# STALO_2.net
KiCad netlist of a schematic drawn in Altium Designer
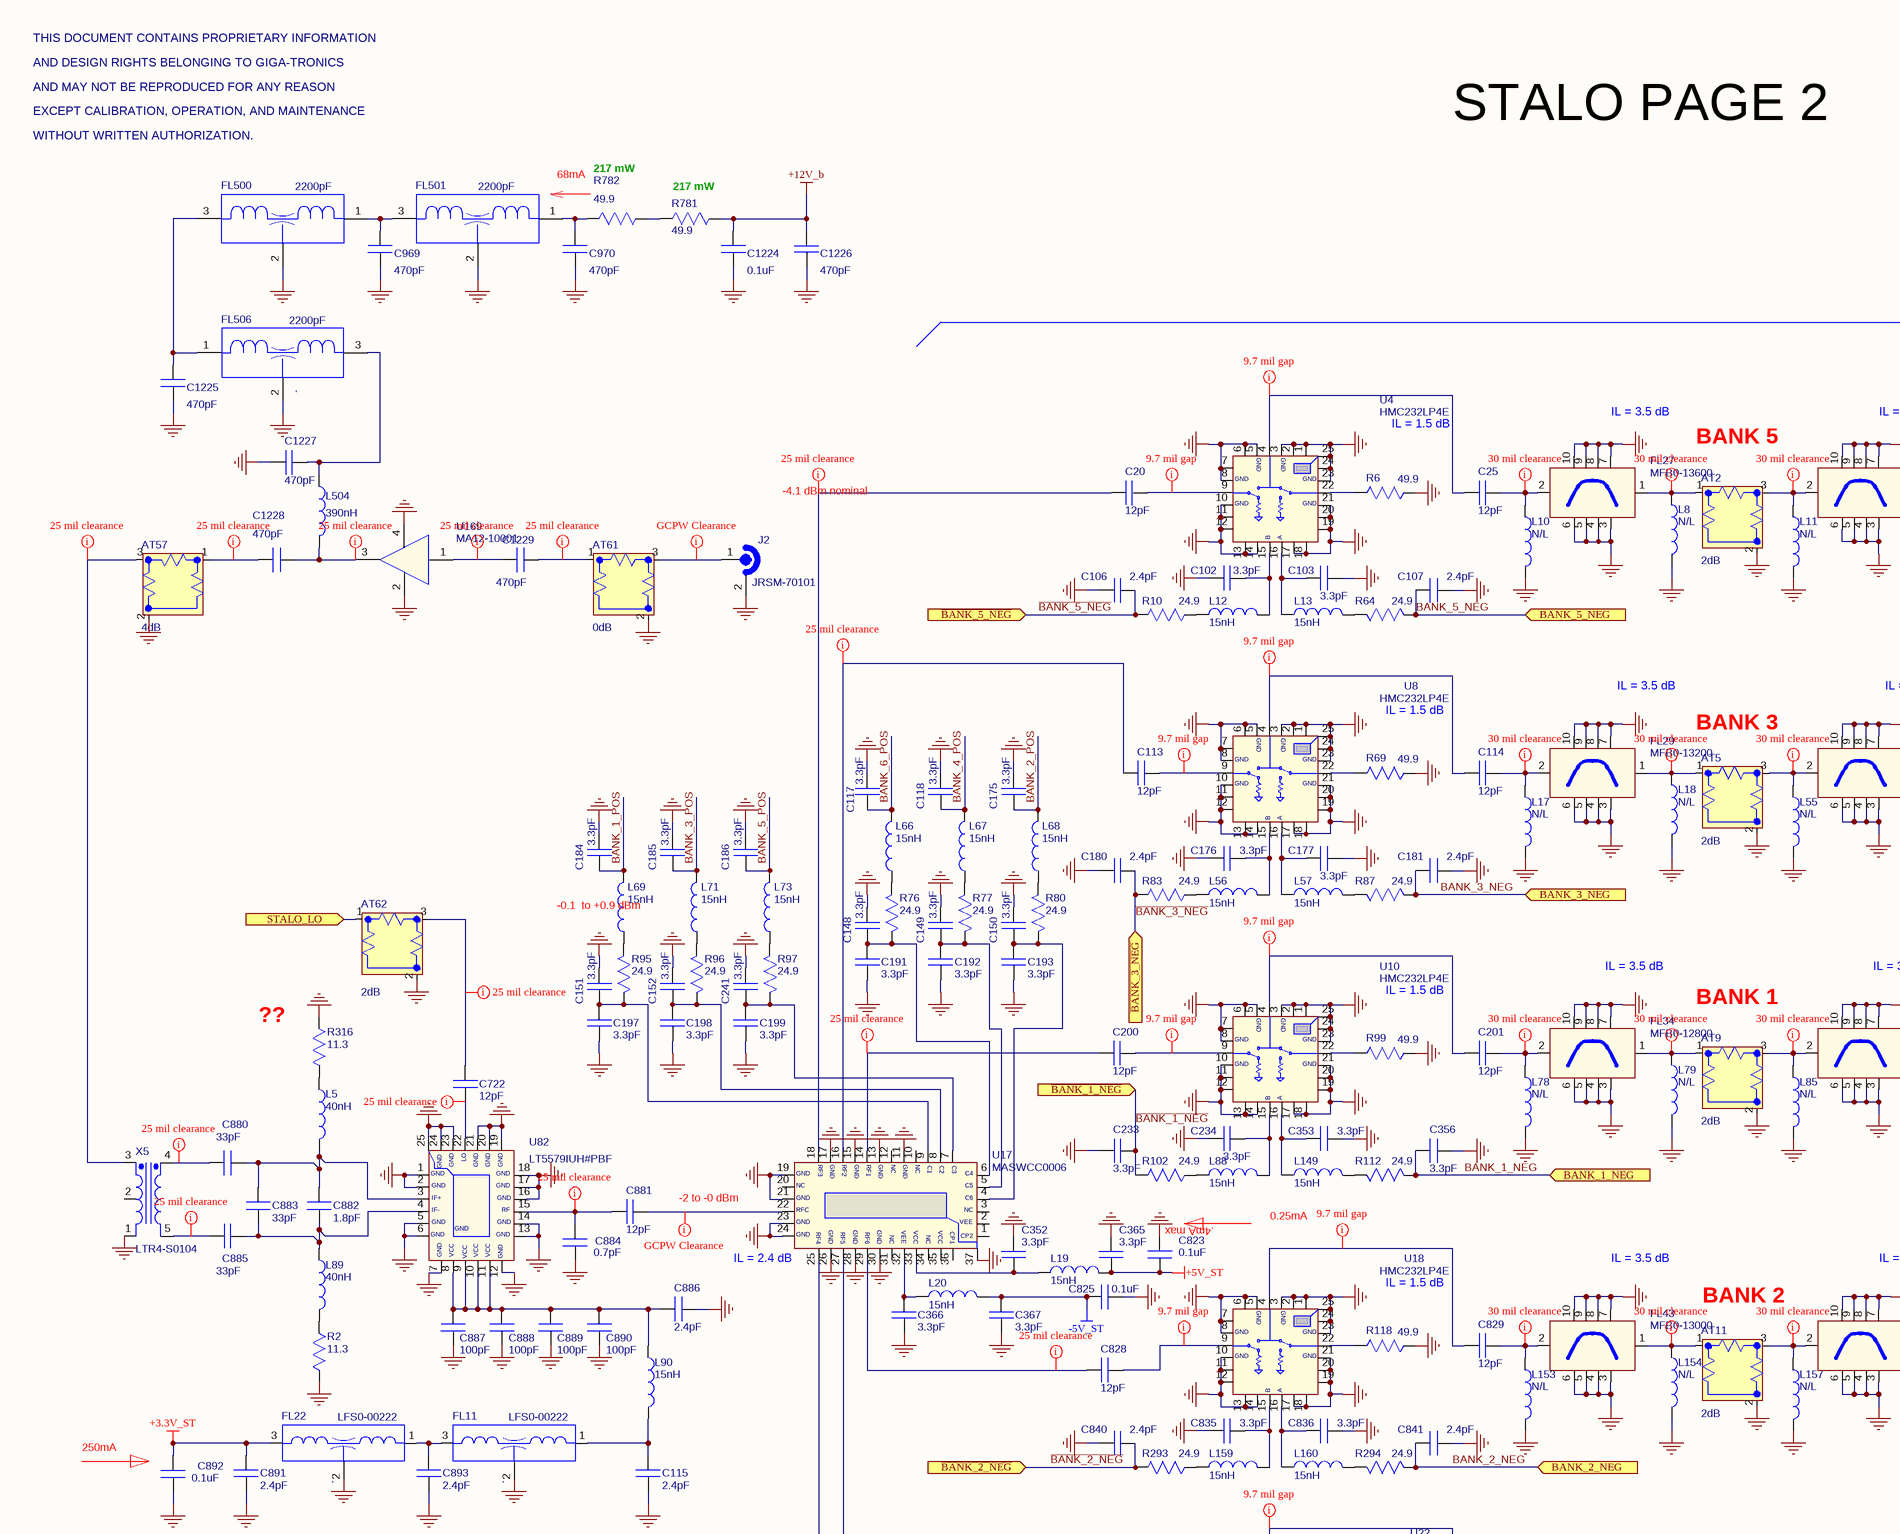
[diagram p0: STALO_2.SchDoc, top left]
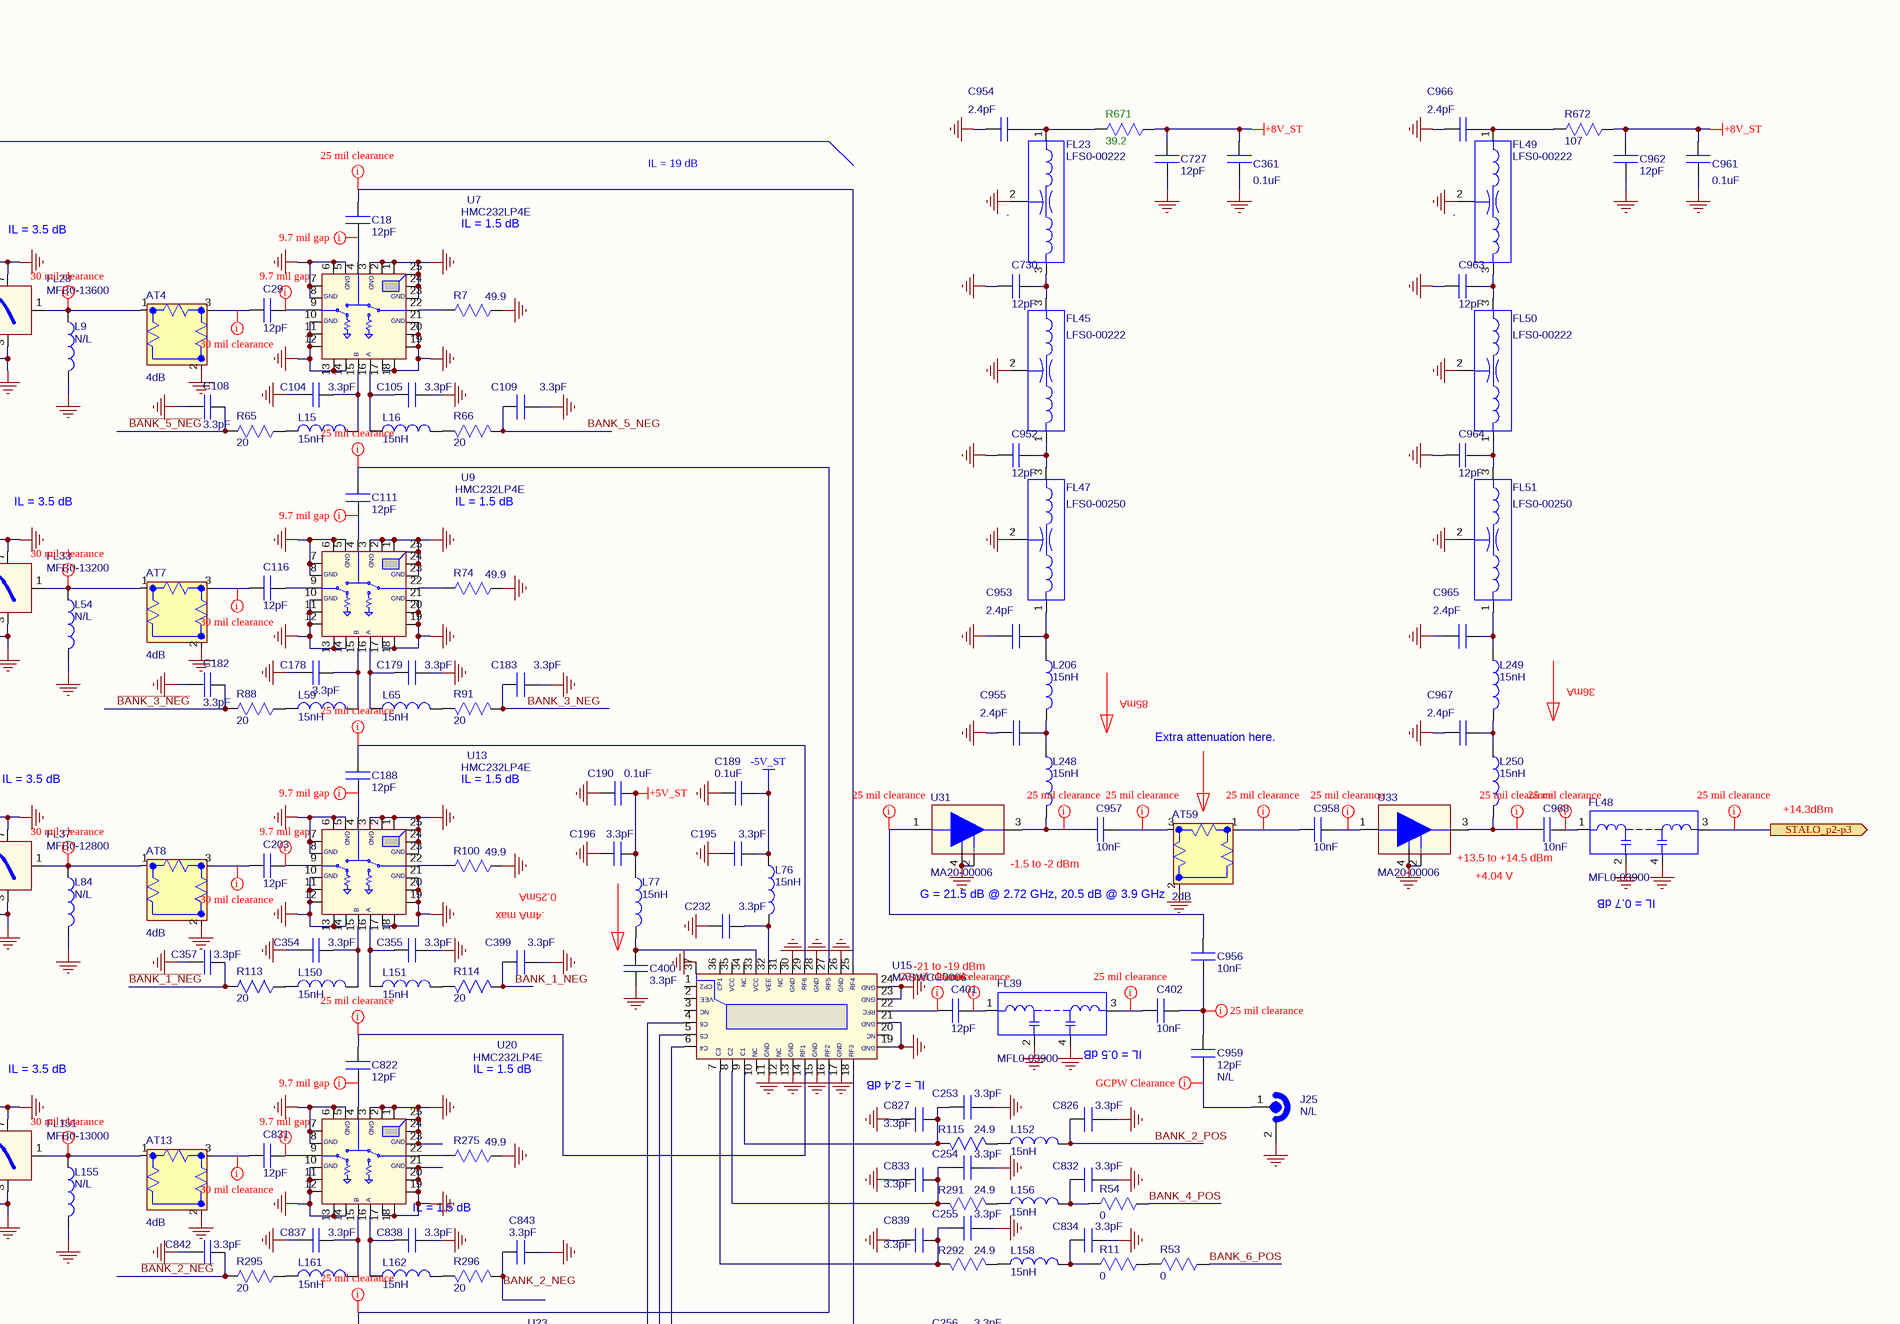
[diagram p1: STALO_2.SchDoc, top right]
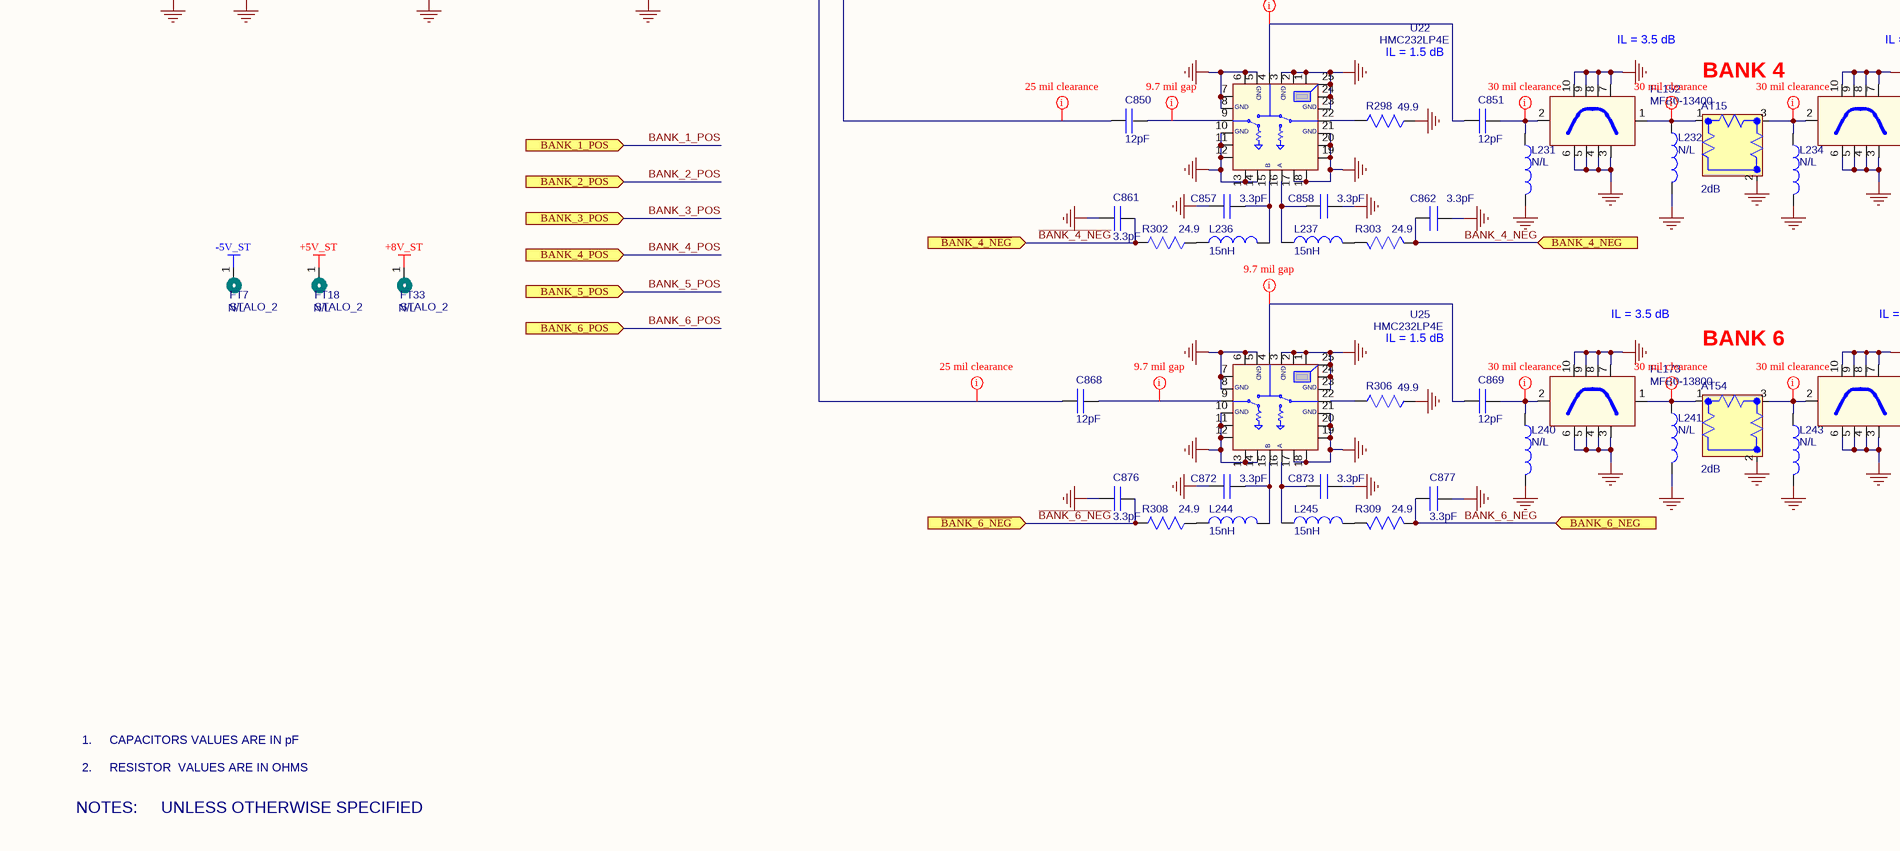
[diagram p2: STALO_2.SchDoc, bottom left]
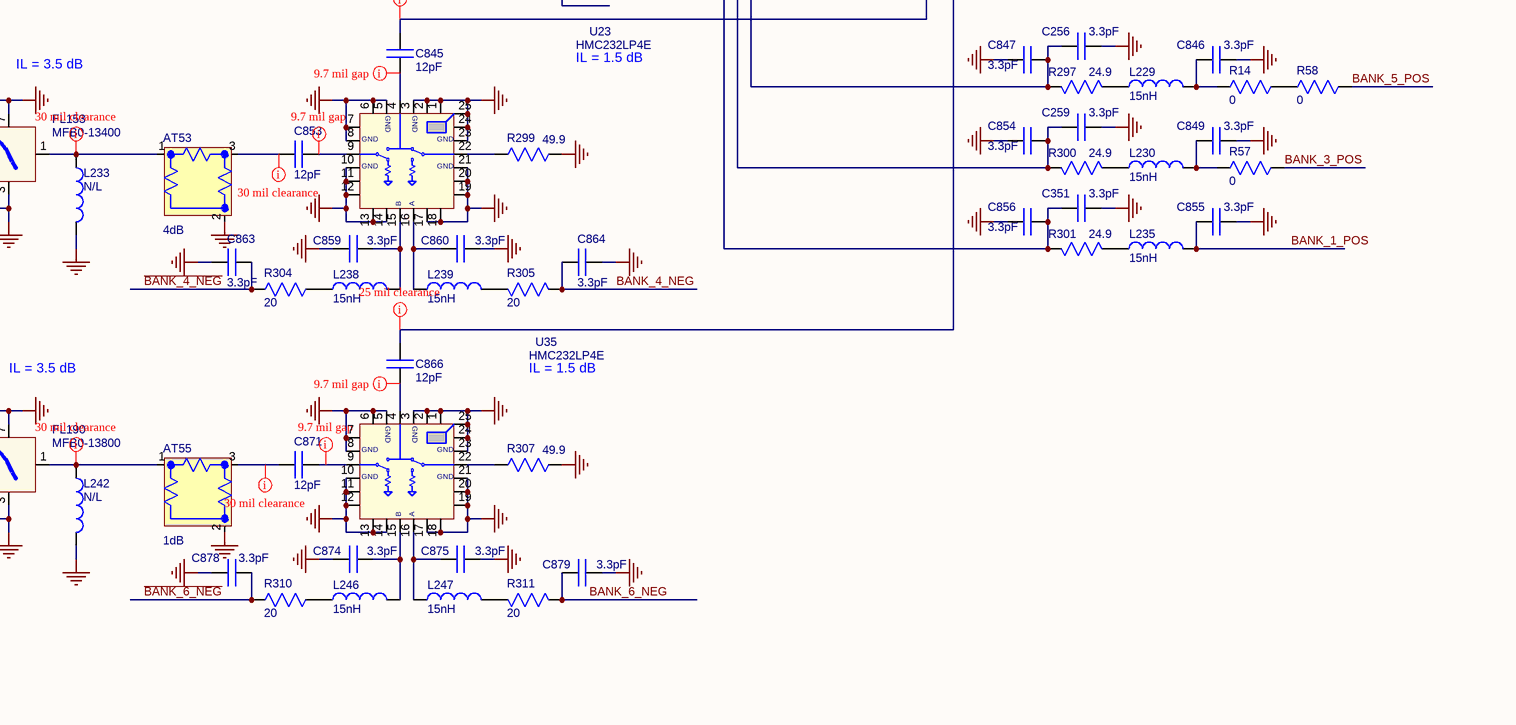
[diagram p3: STALO_2.SchDoc, bottom right]

(export (version "E")
  (design (tool "Eeschema 10.0.6"))
  (components
    (comp (ref "AT2")
      (value "2dB")
      (footprint "ATTN-IMS-0805")
      (description "PAD;CHIP;2dB;+/-.3dB;.08 x .05;50 OHM;FACE DOWN")
      (fields (field (name "APPROVED") "CL"))
      (libsource (lib "Giga-tronics") (part "MPFC-A1002"))
    )
    (comp (ref "AT4")
      (value "4dB")
      (footprint "ATTN-IMS-0805")
      (description "PAD;CHIP;4dB;+/-.3dB;.08 x .05;50 OHM;FACE DOWN")
      (fields (field (name "APPROVED") "CL"))
      (libsource (lib "Giga-tronics") (part "MPFC-A1004"))
    )
    (comp (ref "AT5")
      (value "2dB")
      (footprint "ATTN-IMS-0805")
      (description "PAD;CHIP;2dB;+/-.3dB;.08 x .05;50 OHM;FACE DOWN")
      (fields (field (name "APPROVED") "CL"))
      (libsource (lib "Giga-tronics") (part "MPFC-A1002"))
    )
    (comp (ref "AT7")
      (value "4dB")
      (footprint "ATTN-IMS-0805")
      (description "PAD;CHIP;4dB;+/-.3dB;.08 x .05;50 OHM;FACE DOWN")
      (fields (field (name "APPROVED") "CL"))
      (libsource (lib "Giga-tronics") (part "MPFC-A1004"))
    )
    (comp (ref "AT8")
      (value "4dB")
      (footprint "ATTN-IMS-0805")
      (description "PAD;CHIP;4dB;+/-.3dB;.08 x .05;50 OHM;FACE DOWN")
      (fields (field (name "APPROVED") "CL"))
      (libsource (lib "Giga-tronics") (part "MPFC-A1004"))
    )
    (comp (ref "AT9")
      (value "2dB")
      (footprint "ATTN-IMS-0805")
      (description "PAD;CHIP;2dB;+/-.3dB;.08 x .05;50 OHM;FACE DOWN")
      (fields (field (name "APPROVED") "CL"))
      (libsource (lib "Giga-tronics") (part "MPFC-A1002"))
    )
    (comp (ref "AT11")
      (value "2dB")
      (footprint "ATTN-IMS-0805")
      (description "PAD;CHIP;2dB;+/-.3dB;.08 x .05;50 OHM;FACE DOWN")
      (fields (field (name "APPROVED") "CL"))
      (libsource (lib "Giga-tronics") (part "MPFC-A1002"))
    )
    (comp (ref "AT13")
      (value "4dB")
      (footprint "ATTN-IMS-0805")
      (description "PAD;CHIP;4dB;+/-.3dB;.08 x .05;50 OHM;FACE DOWN")
      (fields (field (name "APPROVED") "CL"))
      (libsource (lib "Giga-tronics") (part "MPFC-A1004"))
    )
    (comp (ref "AT15")
      (value "2dB")
      (footprint "ATTN-IMS-0805")
      (description "PAD;CHIP;2dB;+/-.3dB;.08 x .05;50 OHM;FACE DOWN")
      (fields (field (name "APPROVED") "CL"))
      (libsource (lib "Giga-tronics") (part "MPFC-A1002"))
    )
    (comp (ref "AT53")
      (value "4dB")
      (footprint "ATTN-IMS-0805")
      (description "PAD;CHIP;4dB;+/-.3dB;.08 x .05;50 OHM;FACE DOWN")
      (fields (field (name "APPROVED") "CL"))
      (libsource (lib "Giga-tronics") (part "MPFC-A1004"))
    )
    (comp (ref "AT54")
      (value "2dB")
      (footprint "ATTN-IMS-0805")
      (description "PAD;CHIP;2dB;+/-.3dB;.08 x .05;50 OHM;FACE DOWN")
      (fields (field (name "APPROVED") "CL"))
      (libsource (lib "Giga-tronics") (part "MPFC-A1002"))
    )
    (comp (ref "AT55")
      (value "1dB")
      (footprint "ATTN-IMS-0805")
      (description "PAD;CHIP;1dB;+/-.3dB;.08 x .05;50 OHM;FACE DOWN")
      (fields (field (name "APPROVED") "CL"))
      (libsource (lib "Giga-tronics") (part "MPFC-A1001"))
    )
    (comp (ref "AT57")
      (value "4dB")
      (footprint "ATTN-IMS-0805")
      (description "PAD;CHIP;4dB;+/-.3dB;.08 x .05;50 OHM;FACE DOWN")
      (fields (field (name "APPROVED") "CL"))
      (libsource (lib "") (part "MPFC-A1004_1"))
    )
    (comp (ref "AT59")
      (value "2dB")
      (footprint "ATTN-IMS-0805")
      (description "PAD;CHIP;2dB;+/-.3dB;.08 x .05;50 OHM;FACE DOWN")
      (fields (field (name "APPROVED") "CL"))
      (libsource (lib "") (part "MPFC-A1002_1"))
    )
    (comp (ref "AT61")
      (value "0dB")
      (footprint "ATTN-IMS-0805")
      (description "PAD;CHIP;0dB;+/-.3dB;.08 x .05;50 OHM;FACE DOWN")
      (fields (field (name "APPROVED") "CL"))
      (libsource (lib "Giga-tronics") (part "MPFC-A1000"))
    )
    (comp (ref "AT62")
      (value "2dB")
      (footprint "ATTN-IMS-0805")
      (description "PAD;CHIP;2dB;+/-.3dB;.08 x .05;50 OHM;FACE DOWN")
      (fields (field (name "APPROVED") "CL"))
      (libsource (lib "Giga-tronics") (part "MPFC-A1002"))
    )
    (comp (ref "C18")
      (value "12pF")
      (footprint "CAP-0402-N")
      (description "12 PF;5%;COG;>50V;CHIP;0402")
      (fields (field (name "APPROVED") "CL"))
      (libsource (lib "Giga-tronics") (part "CK40-00120"))
    )
    (comp (ref "C20")
      (value "12pF")
      (footprint "CAP-0402-N")
      (description "12 PF;5%;COG;>50V;CHIP;0402")
      (fields (field (name "APPROVED") "CL"))
      (libsource (lib "Giga-tronics") (part "CK40-00120"))
    )
    (comp (ref "C25")
      (value "12pF")
      (footprint "CAP-0402-N")
      (description "12 PF;5%;COG;>50V;CHIP;0402")
      (fields (field (name "APPROVED") "CL"))
      (libsource (lib "Giga-tronics") (part "CK40-00120"))
    )
    (comp (ref "C29")
      (value "12pF")
      (footprint "CAP-0402-N")
      (description "12 PF;5%;COG;>50V;CHIP;0402")
      (fields (field (name "APPROVED") "CL"))
      (libsource (lib "Giga-tronics") (part "CK40-00120"))
    )
    (comp (ref "C102")
      (value "3.3pF")
      (footprint "CAP-0201-N")
      (description "3.3pF;5%;COG;50V;CHIP;0201")
      (fields (field (name "APPROVED") "CL"))
      (libsource (lib "Giga-tronics") (part "CK35-00033"))
    )
    (comp (ref "C103")
      (value "3.3pF")
      (footprint "CAP-0201-N")
      (description "3.3pF;5%;COG;50V;CHIP;0201")
      (fields (field (name "APPROVED") "CL"))
      (libsource (lib "Giga-tronics") (part "CK35-00033"))
    )
    (comp (ref "C104")
      (value "3.3pF")
      (footprint "CAP-0201-N")
      (description "3.3pF;5%;COG;50V;CHIP;0201")
      (fields (field (name "APPROVED") "CL"))
      (libsource (lib "Giga-tronics") (part "CK35-00033"))
    )
    (comp (ref "C105")
      (value "3.3pF")
      (footprint "CAP-0201-N")
      (description "3.3pF;5%;COG;50V;CHIP;0201")
      (fields (field (name "APPROVED") "CL"))
      (libsource (lib "Giga-tronics") (part "CK35-00033"))
    )
    (comp (ref "C106")
      (value "2.4pF")
      (footprint "CAP-0402-RF")
      (description "2.4 PF;200V;.05PF;HIGH Q;SMT;CERAMIC;0402")
      (fields (field (name "APPROVED") "CL"))
      (libsource (lib "Giga-tronics") (part "CK41-00024"))
    )
    (comp (ref "C107")
      (value "2.4pF")
      (footprint "CAP-0402-RF")
      (description "2.4 PF;200V;.05PF;HIGH Q;SMT;CERAMIC;0402")
      (fields (field (name "APPROVED") "CL"))
      (libsource (lib "Giga-tronics") (part "CK41-00024"))
    )
    (comp (ref "C108")
      (value "3.3pF")
      (footprint "CAP-0201-N")
      (description "3.3pF;5%;COG;50V;CHIP;0201")
      (fields (field (name "APPROVED") "CL"))
      (libsource (lib "Giga-tronics") (part "CK35-00033"))
    )
    (comp (ref "C109")
      (value "3.3pF")
      (footprint "CAP-0201-N")
      (description "3.3pF;5%;COG;50V;CHIP;0201")
      (fields (field (name "APPROVED") "CL"))
      (libsource (lib "Giga-tronics") (part "CK35-00033"))
    )
    (comp (ref "C111")
      (value "12pF")
      (footprint "CAP-0402-N")
      (description "12 PF;5%;COG;>50V;CHIP;0402")
      (fields (field (name "APPROVED") "CL"))
      (libsource (lib "Giga-tronics") (part "CK40-00120"))
    )
    (comp (ref "C113")
      (value "12pF")
      (footprint "CAP-0402-N")
      (description "12 PF;5%;COG;>50V;CHIP;0402")
      (fields (field (name "APPROVED") "CL"))
      (libsource (lib "Giga-tronics") (part "CK40-00120"))
    )
    (comp (ref "C114")
      (value "12pF")
      (footprint "CAP-0402-N")
      (description "12 PF;5%;COG;>50V;CHIP;0402")
      (fields (field (name "APPROVED") "CL"))
      (libsource (lib "Giga-tronics") (part "CK40-00120"))
    )
    (comp (ref "C115")
      (value "2.4pF")
      (footprint "CAP-0402-RF")
      (description "2.4 PF;200V;.05PF;HIGH Q;SMT;CERAMIC;0402")
      (fields (field (name "APPROVED") "CL"))
      (libsource (lib "Giga-tronics") (part "CK41-00024"))
    )
    (comp (ref "C116")
      (value "12pF")
      (footprint "CAP-0402-N")
      (description "12 PF;5%;COG;>50V;CHIP;0402")
      (fields (field (name "APPROVED") "CL"))
      (libsource (lib "Giga-tronics") (part "CK40-00120"))
    )
    (comp (ref "C117")
      (value "3.3pF")
      (footprint "CAP-0201-N")
      (description "3.3pF;5%;COG;50V;CHIP;0201")
      (fields (field (name "APPROVED") "CL"))
      (libsource (lib "Giga-tronics") (part "CK35-00033"))
    )
    (comp (ref "C118")
      (value "3.3pF")
      (footprint "CAP-0201-N")
      (description "3.3pF;5%;COG;50V;CHIP;0201")
      (fields (field (name "APPROVED") "CL"))
      (libsource (lib "Giga-tronics") (part "CK35-00033"))
    )
    (comp (ref "C148")
      (value "3.3pF")
      (footprint "CAP-0201-N")
      (description "3.3pF;5%;COG;50V;CHIP;0201")
      (fields (field (name "APPROVED") "CL"))
      (libsource (lib "Giga-tronics") (part "CK35-00033"))
    )
    (comp (ref "C149")
      (value "3.3pF")
      (footprint "CAP-0201-N")
      (description "3.3pF;5%;COG;50V;CHIP;0201")
      (fields (field (name "APPROVED") "CL"))
      (libsource (lib "Giga-tronics") (part "CK35-00033"))
    )
    (comp (ref "C150")
      (value "3.3pF")
      (footprint "CAP-0201-N")
      (description "3.3pF;5%;COG;50V;CHIP;0201")
      (fields (field (name "APPROVED") "CL"))
      (libsource (lib "Giga-tronics") (part "CK35-00033"))
    )
    (comp (ref "C151")
      (value "3.3pF")
      (footprint "CAP-0201-N")
      (description "3.3pF;5%;COG;50V;CHIP;0201")
      (fields (field (name "APPROVED") "CL"))
      (libsource (lib "Giga-tronics") (part "CK35-00033"))
    )
    (comp (ref "C152")
      (value "3.3pF")
      (footprint "CAP-0201-N")
      (description "3.3pF;5%;COG;50V;CHIP;0201")
      (fields (field (name "APPROVED") "CL"))
      (libsource (lib "Giga-tronics") (part "CK35-00033"))
    )
    (comp (ref "C175")
      (value "3.3pF")
      (footprint "CAP-0201-N")
      (description "3.3pF;5%;COG;50V;CHIP;0201")
      (fields (field (name "APPROVED") "CL"))
      (libsource (lib "Giga-tronics") (part "CK35-00033"))
    )
    (comp (ref "C176")
      (value "3.3pF")
      (footprint "CAP-0201-N")
      (description "3.3pF;5%;COG;50V;CHIP;0201")
      (fields (field (name "APPROVED") "CL"))
      (libsource (lib "Giga-tronics") (part "CK35-00033"))
    )
    (comp (ref "C177")
      (value "3.3pF")
      (footprint "CAP-0201-N")
      (description "3.3pF;5%;COG;50V;CHIP;0201")
      (fields (field (name "APPROVED") "CL"))
      (libsource (lib "Giga-tronics") (part "CK35-00033"))
    )
    (comp (ref "C178")
      (value "3.3pF")
      (footprint "CAP-0201-N")
      (description "3.3pF;5%;COG;50V;CHIP;0201")
      (fields (field (name "APPROVED") "CL"))
      (libsource (lib "Giga-tronics") (part "CK35-00033"))
    )
    (comp (ref "C179")
      (value "3.3pF")
      (footprint "CAP-0201-N")
      (description "3.3pF;5%;COG;50V;CHIP;0201")
      (fields (field (name "APPROVED") "CL"))
      (libsource (lib "Giga-tronics") (part "CK35-00033"))
    )
    (comp (ref "C180")
      (value "2.4pF")
      (footprint "CAP-0402-RF")
      (description "2.4 PF;200V;.05PF;HIGH Q;SMT;CERAMIC;0402")
      (fields (field (name "APPROVED") "CL"))
      (libsource (lib "Giga-tronics") (part "CK41-00024"))
    )
    (comp (ref "C181")
      (value "2.4pF")
      (footprint "CAP-0402-RF")
      (description "2.4 PF;200V;.05PF;HIGH Q;SMT;CERAMIC;0402")
      (fields (field (name "APPROVED") "CL"))
      (libsource (lib "Giga-tronics") (part "CK41-00024"))
    )
    (comp (ref "C182")
      (value "3.3pF")
      (footprint "CAP-0201-N")
      (description "3.3pF;5%;COG;50V;CHIP;0201")
      (fields (field (name "APPROVED") "CL"))
      (libsource (lib "Giga-tronics") (part "CK35-00033"))
    )
    (comp (ref "C183")
      (value "3.3pF")
      (footprint "CAP-0201-N")
      (description "3.3pF;5%;COG;50V;CHIP;0201")
      (fields (field (name "APPROVED") "CL"))
      (libsource (lib "Giga-tronics") (part "CK35-00033"))
    )
    (comp (ref "C184")
      (value "3.3pF")
      (footprint "CAP-0201-N")
      (description "3.3pF;5%;COG;50V;CHIP;0201")
      (fields (field (name "APPROVED") "CL"))
      (libsource (lib "Giga-tronics") (part "CK35-00033"))
    )
    (comp (ref "C185")
      (value "3.3pF")
      (footprint "CAP-0201-N")
      (description "3.3pF;5%;COG;50V;CHIP;0201")
      (fields (field (name "APPROVED") "CL"))
      (libsource (lib "Giga-tronics") (part "CK35-00033"))
    )
    (comp (ref "C186")
      (value "3.3pF")
      (footprint "CAP-0201-N")
      (description "3.3pF;5%;COG;50V;CHIP;0201")
      (fields (field (name "APPROVED") "CL"))
      (libsource (lib "Giga-tronics") (part "CK35-00033"))
    )
    (comp (ref "C188")
      (value "12pF")
      (footprint "CAP-0402-N")
      (description "12 PF;5%;COG;>50V;CHIP;0402")
      (fields (field (name "APPROVED") "CL"))
      (libsource (lib "Giga-tronics") (part "CK40-00120"))
    )
    (comp (ref "C189")
      (value "0.1uF")
      (footprint "CAP-0402-N")
      (description ".1 UF,10%;X7R;16V,CHIP;0402")
      (fields (field (name "APPROVED") "CL"))
      (libsource (lib "Giga-tronics") (part "CK40-04100"))
    )
    (comp (ref "C190")
      (value "0.1uF")
      (footprint "CAP-0402-N")
      (description ".1 UF,10%;X7R;16V,CHIP;0402")
      (fields (field (name "APPROVED") "CL"))
      (libsource (lib "Giga-tronics") (part "CK40-04100"))
    )
    (comp (ref "C191")
      (value "3.3pF")
      (footprint "CAP-0201-N")
      (description "3.3pF;5%;COG;50V;CHIP;0201")
      (fields (field (name "APPROVED") "CL"))
      (libsource (lib "Giga-tronics") (part "CK35-00033"))
    )
    (comp (ref "C192")
      (value "3.3pF")
      (footprint "CAP-0201-N")
      (description "3.3pF;5%;COG;50V;CHIP;0201")
      (fields (field (name "APPROVED") "CL"))
      (libsource (lib "Giga-tronics") (part "CK35-00033"))
    )
    (comp (ref "C193")
      (value "3.3pF")
      (footprint "CAP-0201-N")
      (description "3.3pF;5%;COG;50V;CHIP;0201")
      (fields (field (name "APPROVED") "CL"))
      (libsource (lib "Giga-tronics") (part "CK35-00033"))
    )
    (comp (ref "C195")
      (value "3.3pF")
      (footprint "CAP-0201-N")
      (description "3.3pF;5%;COG;50V;CHIP;0201")
      (fields (field (name "APPROVED") "CL"))
      (libsource (lib "Giga-tronics") (part "CK35-00033"))
    )
    (comp (ref "C196")
      (value "3.3pF")
      (footprint "CAP-0201-N")
      (description "3.3pF;5%;COG;50V;CHIP;0201")
      (fields (field (name "APPROVED") "CL"))
      (libsource (lib "Giga-tronics") (part "CK35-00033"))
    )
    (comp (ref "C197")
      (value "3.3pF")
      (footprint "CAP-0201-N")
      (description "3.3pF;5%;COG;50V;CHIP;0201")
      (fields (field (name "APPROVED") "CL"))
      (libsource (lib "Giga-tronics") (part "CK35-00033"))
    )
    (comp (ref "C198")
      (value "3.3pF")
      (footprint "CAP-0201-N")
      (description "3.3pF;5%;COG;50V;CHIP;0201")
      (fields (field (name "APPROVED") "CL"))
      (libsource (lib "Giga-tronics") (part "CK35-00033"))
    )
    (comp (ref "C199")
      (value "3.3pF")
      (footprint "CAP-0201-N")
      (description "3.3pF;5%;COG;50V;CHIP;0201")
      (fields (field (name "APPROVED") "CL"))
      (libsource (lib "Giga-tronics") (part "CK35-00033"))
    )
    (comp (ref "C200")
      (value "12pF")
      (footprint "CAP-0402-N")
      (description "12 PF;5%;COG;>50V;CHIP;0402")
      (fields (field (name "APPROVED") "CL"))
      (libsource (lib "Giga-tronics") (part "CK40-00120"))
    )
    (comp (ref "C201")
      (value "12pF")
      (footprint "CAP-0402-N")
      (description "12 PF;5%;COG;>50V;CHIP;0402")
      (fields (field (name "APPROVED") "CL"))
      (libsource (lib "Giga-tronics") (part "CK40-00120"))
    )
    (comp (ref "C203")
      (value "12pF")
      (footprint "CAP-0402-N")
      (description "12 PF;5%;COG;>50V;CHIP;0402")
      (fields (field (name "APPROVED") "CL"))
      (libsource (lib "Giga-tronics") (part "CK40-00120"))
    )
    (comp (ref "C232")
      (value "3.3pF")
      (footprint "CAP-0201-N")
      (description "3.3pF;5%;COG;50V;CHIP;0201")
      (fields (field (name "APPROVED") "CL"))
      (libsource (lib "Giga-tronics") (part "CK35-00033"))
    )
    (comp (ref "C233")
      (value "3.3pF")
      (footprint "CAP-0201-N")
      (description "3.3pF;5%;COG;50V;CHIP;0201")
      (fields (field (name "APPROVED") "CL"))
      (libsource (lib "Giga-tronics") (part "CK35-00033"))
    )
    (comp (ref "C234")
      (value "3.3pF")
      (footprint "CAP-0201-N")
      (description "3.3pF;5%;COG;50V;CHIP;0201")
      (fields (field (name "APPROVED") "CL"))
      (libsource (lib "Giga-tronics") (part "CK35-00033"))
    )
    (comp (ref "C241")
      (value "3.3pF")
      (footprint "CAP-0201-N")
      (description "3.3pF;5%;COG;50V;CHIP;0201")
      (fields (field (name "APPROVED") "CL"))
      (libsource (lib "Giga-tronics") (part "CK35-00033"))
    )
    (comp (ref "C253")
      (value "3.3pF")
      (footprint "CAP-0201-N")
      (description "3.3pF;5%;COG;50V;CHIP;0201")
      (fields (field (name "APPROVED") "CL"))
      (libsource (lib "Giga-tronics") (part "CK35-00033"))
    )
    (comp (ref "C254")
      (value "3.3pF")
      (footprint "CAP-0201-N")
      (description "3.3pF;5%;COG;50V;CHIP;0201")
      (fields (field (name "APPROVED") "CL"))
      (libsource (lib "Giga-tronics") (part "CK35-00033"))
    )
    (comp (ref "C255")
      (value "3.3pF")
      (footprint "CAP-0201-N")
      (description "3.3pF;5%;COG;50V;CHIP;0201")
      (fields (field (name "APPROVED") "CL"))
      (libsource (lib "Giga-tronics") (part "CK35-00033"))
    )
    (comp (ref "C256")
      (value "3.3pF")
      (footprint "CAP-0201-N")
      (description "3.3pF;5%;COG;50V;CHIP;0201")
      (fields (field (name "APPROVED") "CL"))
      (libsource (lib "Giga-tronics") (part "CK35-00033"))
    )
    (comp (ref "C259")
      (value "3.3pF")
      (footprint "CAP-0201-N")
      (description "3.3pF;5%;COG;50V;CHIP;0201")
      (fields (field (name "APPROVED") "CL"))
      (libsource (lib "Giga-tronics") (part "CK35-00033"))
    )
    (comp (ref "C351")
      (value "3.3pF")
      (footprint "CAP-0201-N")
      (description "3.3pF;5%;COG;50V;CHIP;0201")
      (fields (field (name "APPROVED") "CL"))
      (libsource (lib "Giga-tronics") (part "CK35-00033"))
    )
    (comp (ref "C352")
      (value "3.3pF")
      (footprint "CAP-0201-N")
      (description "3.3pF;5%;COG;50V;CHIP;0201")
      (fields (field (name "APPROVED") "CL"))
      (libsource (lib "Giga-tronics") (part "CK35-00033"))
    )
    (comp (ref "C353")
      (value "3.3pF")
      (footprint "CAP-0201-N")
      (description "3.3pF;5%;COG;50V;CHIP;0201")
      (fields (field (name "APPROVED") "CL"))
      (libsource (lib "Giga-tronics") (part "CK35-00033"))
    )
    (comp (ref "C354")
      (value "3.3pF")
      (footprint "CAP-0201-N")
      (description "3.3pF;5%;COG;50V;CHIP;0201")
      (fields (field (name "APPROVED") "CL"))
      (libsource (lib "Giga-tronics") (part "CK35-00033"))
    )
    (comp (ref "C355")
      (value "3.3pF")
      (footprint "CAP-0201-N")
      (description "3.3pF;5%;COG;50V;CHIP;0201")
      (fields (field (name "APPROVED") "CL"))
      (libsource (lib "Giga-tronics") (part "CK35-00033"))
    )
    (comp (ref "C356")
      (value "3.3pF")
      (footprint "CAP-0201-N")
      (description "3.3pF;5%;COG;50V;CHIP;0201")
      (fields (field (name "APPROVED") "CL"))
      (libsource (lib "Giga-tronics") (part "CK35-00033"))
    )
    (comp (ref "C357")
      (value "3.3pF")
      (footprint "CAP-0201-N")
      (description "3.3pF;5%;COG;50V;CHIP;0201")
      (fields (field (name "APPROVED") "CL"))
      (libsource (lib "Giga-tronics") (part "CK35-00033"))
    )
    (comp (ref "C361")
      (value "0.1uF")
      (footprint "CAP-0603-H035-N")
      (description ".1UF;10%;X7R;16V;CHIP;0603")
      (fields (field (name "APPROVED") "CL"))
      (libsource (lib "Giga-tronics") (part "CK45-04100"))
    )
    (comp (ref "C365")
      (value "3.3pF")
      (footprint "CAP-0201-N")
      (description "3.3pF;5%;COG;50V;CHIP;0201")
      (fields (field (name "APPROVED") "CL"))
      (libsource (lib "Giga-tronics") (part "CK35-00033"))
    )
    (comp (ref "C366")
      (value "3.3pF")
      (footprint "CAP-0201-N")
      (description "3.3pF;5%;COG;50V;CHIP;0201")
      (fields (field (name "APPROVED") "CL"))
      (libsource (lib "Giga-tronics") (part "CK35-00033"))
    )
    (comp (ref "C367")
      (value "3.3pF")
      (footprint "CAP-0201-N")
      (description "3.3pF;5%;COG;50V;CHIP;0201")
      (fields (field (name "APPROVED") "CL"))
      (libsource (lib "Giga-tronics") (part "CK35-00033"))
    )
    (comp (ref "C399")
      (value "3.3pF")
      (footprint "CAP-0201-N")
      (description "3.3pF;5%;COG;50V;CHIP;0201")
      (fields (field (name "APPROVED") "CL"))
      (libsource (lib "Giga-tronics") (part "CK35-00033"))
    )
    (comp (ref "C400")
      (value "3.3pF")
      (footprint "CAP-0201-N")
      (description "3.3pF;5%;COG;50V;CHIP;0201")
      (fields (field (name "APPROVED") "CL"))
      (libsource (lib "Giga-tronics") (part "CK35-00033"))
    )
    (comp (ref "C401")
      (value "12pF")
      (footprint "CAP-0402-N")
      (description "12 PF;5%;COG;>50V;CHIP;0402")
      (fields (field (name "APPROVED") "CL"))
      (libsource (lib "Giga-tronics") (part "CK40-00120"))
    )
    (comp (ref "C402")
      (value "10nF")
      (footprint "CAP-0402-N")
      (description "10nF;10%;X7R;16 WVDC;CHIP;0402")
      (fields (field (name "APPROVED") "CL"))
      (libsource (lib "Giga-tronics") (part "TCC3-03100"))
    )
    (comp (ref "C722")
      (value "12pF")
      (footprint "CAP-0402-N")
      (description "12 PF;5%;COG;>50V;CHIP;0402")
      (fields (field (name "APPROVED") "CL"))
      (libsource (lib "Giga-tronics") (part "CK40-00120"))
    )
    (comp (ref "C727")
      (value "12pF")
      (footprint "CAP-0402-N")
      (description "12 PF;5%;COG;>50V;CHIP;0402")
      (fields (field (name "APPROVED") "CL"))
      (libsource (lib "Giga-tronics") (part "CK40-00120"))
    )
    (comp (ref "C730")
      (value "12pF")
      (footprint "CAP-0402-N")
      (description "12 PF;5%;COG;>50V;CHIP;0402")
      (fields (field (name "APPROVED") "CL"))
      (libsource (lib "Giga-tronics") (part "CK40-00120"))
    )
    (comp (ref "C822")
      (value "12pF")
      (footprint "CAP-0402-N")
      (description "12 PF;5%;COG;>50V;CHIP;0402")
      (fields (field (name "APPROVED") "CL"))
      (libsource (lib "Giga-tronics") (part "CK40-00120"))
    )
    (comp (ref "C823")
      (value "0.1uF")
      (footprint "CAP-0402-N")
      (description ".1 UF,10%;X7R;16V,CHIP;0402")
      (fields (field (name "APPROVED") "CL"))
      (libsource (lib "Giga-tronics") (part "CK40-04100"))
    )
    (comp (ref "C825")
      (value "0.1uF")
      (footprint "CAP-0402-N")
      (description ".1 UF,10%;X7R;16V,CHIP;0402")
      (fields (field (name "APPROVED") "CL"))
      (libsource (lib "Giga-tronics") (part "CK40-04100"))
    )
    (comp (ref "C826")
      (value "3.3pF")
      (footprint "CAP-0201-N")
      (description "3.3pF;5%;COG;50V;CHIP;0201")
      (fields (field (name "APPROVED") "CL"))
      (libsource (lib "Giga-tronics") (part "CK35-00033"))
    )
    (comp (ref "C827")
      (value "3.3pF")
      (footprint "CAP-0201-N")
      (description "3.3pF;5%;COG;50V;CHIP;0201")
      (fields (field (name "APPROVED") "CL"))
      (libsource (lib "Giga-tronics") (part "CK35-00033"))
    )
    (comp (ref "C828")
      (value "12pF")
      (footprint "CAP-0402-N")
      (description "12 PF;5%;COG;>50V;CHIP;0402")
      (fields (field (name "APPROVED") "CL"))
      (libsource (lib "Giga-tronics") (part "CK40-00120"))
    )
    (comp (ref "C829")
      (value "12pF")
      (footprint "CAP-0402-N")
      (description "12 PF;5%;COG;>50V;CHIP;0402")
      (fields (field (name "APPROVED") "CL"))
      (libsource (lib "Giga-tronics") (part "CK40-00120"))
    )
    (comp (ref "C831")
      (value "12pF")
      (footprint "CAP-0402-N")
      (description "12 PF;5%;COG;>50V;CHIP;0402")
      (fields (field (name "APPROVED") "CL"))
      (libsource (lib "Giga-tronics") (part "CK40-00120"))
    )
    (comp (ref "C832")
      (value "3.3pF")
      (footprint "CAP-0201-N")
      (description "3.3pF;5%;COG;50V;CHIP;0201")
      (fields (field (name "APPROVED") "CL"))
      (libsource (lib "Giga-tronics") (part "CK35-00033"))
    )
    (comp (ref "C833")
      (value "3.3pF")
      (footprint "CAP-0201-N")
      (description "3.3pF;5%;COG;50V;CHIP;0201")
      (fields (field (name "APPROVED") "CL"))
      (libsource (lib "Giga-tronics") (part "CK35-00033"))
    )
    (comp (ref "C834")
      (value "3.3pF")
      (footprint "CAP-0201-N")
      (description "3.3pF;5%;COG;50V;CHIP;0201")
      (fields (field (name "APPROVED") "CL"))
      (libsource (lib "Giga-tronics") (part "CK35-00033"))
    )
    (comp (ref "C835")
      (value "3.3pF")
      (footprint "CAP-0201-N")
      (description "3.3pF;5%;COG;50V;CHIP;0201")
      (fields (field (name "APPROVED") "CL"))
      (libsource (lib "Giga-tronics") (part "CK35-00033"))
    )
    (comp (ref "C836")
      (value "3.3pF")
      (footprint "CAP-0201-N")
      (description "3.3pF;5%;COG;50V;CHIP;0201")
      (fields (field (name "APPROVED") "CL"))
      (libsource (lib "Giga-tronics") (part "CK35-00033"))
    )
    (comp (ref "C837")
      (value "3.3pF")
      (footprint "CAP-0201-N")
      (description "3.3pF;5%;COG;50V;CHIP;0201")
      (fields (field (name "APPROVED") "CL"))
      (libsource (lib "Giga-tronics") (part "CK35-00033"))
    )
    (comp (ref "C838")
      (value "3.3pF")
      (footprint "CAP-0201-N")
      (description "3.3pF;5%;COG;50V;CHIP;0201")
      (fields (field (name "APPROVED") "CL"))
      (libsource (lib "Giga-tronics") (part "CK35-00033"))
    )
    (comp (ref "C839")
      (value "3.3pF")
      (footprint "CAP-0201-N")
      (description "3.3pF;5%;COG;50V;CHIP;0201")
      (fields (field (name "APPROVED") "CL"))
      (libsource (lib "Giga-tronics") (part "CK35-00033"))
    )
    (comp (ref "C840")
      (value "2.4pF")
      (footprint "CAP-0402-RF")
      (description "2.4 PF;200V;.05PF;HIGH Q;SMT;CERAMIC;0402")
      (fields (field (name "APPROVED") "CL"))
      (libsource (lib "Giga-tronics") (part "CK41-00024"))
    )
    (comp (ref "C841")
      (value "2.4pF")
      (footprint "CAP-0402-RF")
      (description "2.4 PF;200V;.05PF;HIGH Q;SMT;CERAMIC;0402")
      (fields (field (name "APPROVED") "CL"))
      (libsource (lib "Giga-tronics") (part "CK41-00024"))
    )
    (comp (ref "C842")
      (value "3.3pF")
      (footprint "CAP-0201-N")
      (description "3.3pF;5%;COG;50V;CHIP;0201")
      (fields (field (name "APPROVED") "CL"))
      (libsource (lib "Giga-tronics") (part "CK35-00033"))
    )
    (comp (ref "C843")
      (value "3.3pF")
      (footprint "CAP-0201-N")
      (description "3.3pF;5%;COG;50V;CHIP;0201")
      (fields (field (name "APPROVED") "CL"))
      (libsource (lib "Giga-tronics") (part "CK35-00033"))
    )
    (comp (ref "C845")
      (value "12pF")
      (footprint "CAP-0402-N")
      (description "12 PF;5%;COG;>50V;CHIP;0402")
      (fields (field (name "APPROVED") "CL"))
      (libsource (lib "Giga-tronics") (part "CK40-00120"))
    )
    (comp (ref "C846")
      (value "3.3pF")
      (footprint "CAP-0201-N")
      (description "3.3pF;5%;COG;50V;CHIP;0201")
      (fields (field (name "APPROVED") "CL"))
      (libsource (lib "Giga-tronics") (part "CK35-00033"))
    )
    (comp (ref "C847")
      (value "3.3pF")
      (footprint "CAP-0201-N")
      (description "3.3pF;5%;COG;50V;CHIP;0201")
      (fields (field (name "APPROVED") "CL"))
      (libsource (lib "Giga-tronics") (part "CK35-00033"))
    )
    (comp (ref "C849")
      (value "3.3pF")
      (footprint "CAP-0201-N")
      (description "3.3pF;5%;COG;50V;CHIP;0201")
      (fields (field (name "APPROVED") "CL"))
      (libsource (lib "Giga-tronics") (part "CK35-00033"))
    )
    (comp (ref "C850")
      (value "12pF")
      (footprint "CAP-0402-N")
      (description "12 PF;5%;COG;>50V;CHIP;0402")
      (fields (field (name "APPROVED") "CL"))
      (libsource (lib "Giga-tronics") (part "CK40-00120"))
    )
    (comp (ref "C851")
      (value "12pF")
      (footprint "CAP-0402-N")
      (description "12 PF;5%;COG;>50V;CHIP;0402")
      (fields (field (name "APPROVED") "CL"))
      (libsource (lib "Giga-tronics") (part "CK40-00120"))
    )
    (comp (ref "C853")
      (value "12pF")
      (footprint "CAP-0402-N")
      (description "12 PF;5%;COG;>50V;CHIP;0402")
      (fields (field (name "APPROVED") "CL"))
      (libsource (lib "Giga-tronics") (part "CK40-00120"))
    )
    (comp (ref "C854")
      (value "3.3pF")
      (footprint "CAP-0201-N")
      (description "3.3pF;5%;COG;50V;CHIP;0201")
      (fields (field (name "APPROVED") "CL"))
      (libsource (lib "Giga-tronics") (part "CK35-00033"))
    )
    (comp (ref "C855")
      (value "3.3pF")
      (footprint "CAP-0201-N")
      (description "3.3pF;5%;COG;50V;CHIP;0201")
      (fields (field (name "APPROVED") "CL"))
      (libsource (lib "Giga-tronics") (part "CK35-00033"))
    )
    (comp (ref "C856")
      (value "3.3pF")
      (footprint "CAP-0201-N")
      (description "3.3pF;5%;COG;50V;CHIP;0201")
      (fields (field (name "APPROVED") "CL"))
      (libsource (lib "Giga-tronics") (part "CK35-00033"))
    )
    (comp (ref "C857")
      (value "3.3pF")
      (footprint "CAP-0201-N")
      (description "3.3pF;5%;COG;50V;CHIP;0201")
      (fields (field (name "APPROVED") "CL"))
      (libsource (lib "Giga-tronics") (part "CK35-00033"))
    )
    (comp (ref "C858")
      (value "3.3pF")
      (footprint "CAP-0201-N")
      (description "3.3pF;5%;COG;50V;CHIP;0201")
      (fields (field (name "APPROVED") "CL"))
      (libsource (lib "Giga-tronics") (part "CK35-00033"))
    )
    (comp (ref "C859")
      (value "3.3pF")
      (footprint "CAP-0201-N")
      (description "3.3pF;5%;COG;50V;CHIP;0201")
      (fields (field (name "APPROVED") "CL"))
      (libsource (lib "Giga-tronics") (part "CK35-00033"))
    )
    (comp (ref "C860")
      (value "3.3pF")
      (footprint "CAP-0201-N")
      (description "3.3pF;5%;COG;50V;CHIP;0201")
      (fields (field (name "APPROVED") "CL"))
      (libsource (lib "Giga-tronics") (part "CK35-00033"))
    )
    (comp (ref "C861")
      (value "3.3pF")
      (footprint "CAP-0201-N")
      (description "3.3pF;5%;COG;50V;CHIP;0201")
      (fields (field (name "APPROVED") "CL"))
      (libsource (lib "Giga-tronics") (part "CK35-00033"))
    )
    (comp (ref "C862")
      (value "3.3pF")
      (footprint "CAP-0201-N")
      (description "3.3pF;5%;COG;50V;CHIP;0201")
      (fields (field (name "APPROVED") "CL"))
      (libsource (lib "Giga-tronics") (part "CK35-00033"))
    )
    (comp (ref "C863")
      (value "3.3pF")
      (footprint "CAP-0201-N")
      (description "3.3pF;5%;COG;50V;CHIP;0201")
      (fields (field (name "APPROVED") "CL"))
      (libsource (lib "Giga-tronics") (part "CK35-00033"))
    )
    (comp (ref "C864")
      (value "3.3pF")
      (footprint "CAP-0201-N")
      (description "3.3pF;5%;COG;50V;CHIP;0201")
      (fields (field (name "APPROVED") "CL"))
      (libsource (lib "Giga-tronics") (part "CK35-00033"))
    )
    (comp (ref "C866")
      (value "12pF")
      (footprint "CAP-0402-N")
      (description "12 PF;5%;COG;>50V;CHIP;0402")
      (fields (field (name "APPROVED") "CL"))
      (libsource (lib "Giga-tronics") (part "CK40-00120"))
    )
    (comp (ref "C868")
      (value "12pF")
      (footprint "CAP-0402-N")
      (description "12 PF;5%;COG;>50V;CHIP;0402")
      (fields (field (name "APPROVED") "CL"))
      (libsource (lib "Giga-tronics") (part "CK40-00120"))
    )
    (comp (ref "C869")
      (value "12pF")
      (footprint "CAP-0402-N")
      (description "12 PF;5%;COG;>50V;CHIP;0402")
      (fields (field (name "APPROVED") "CL"))
      (libsource (lib "Giga-tronics") (part "CK40-00120"))
    )
    (comp (ref "C871")
      (value "12pF")
      (footprint "CAP-0402-N")
      (description "12 PF;5%;COG;>50V;CHIP;0402")
      (fields (field (name "APPROVED") "CL"))
      (libsource (lib "Giga-tronics") (part "CK40-00120"))
    )
    (comp (ref "C872")
      (value "3.3pF")
      (footprint "CAP-0201-N")
      (description "3.3pF;5%;COG;50V;CHIP;0201")
      (fields (field (name "APPROVED") "CL"))
      (libsource (lib "Giga-tronics") (part "CK35-00033"))
    )
    (comp (ref "C873")
      (value "3.3pF")
      (footprint "CAP-0201-N")
      (description "3.3pF;5%;COG;50V;CHIP;0201")
      (fields (field (name "APPROVED") "CL"))
      (libsource (lib "Giga-tronics") (part "CK35-00033"))
    )
    (comp (ref "C874")
      (value "3.3pF")
      (footprint "CAP-0201-N")
      (description "3.3pF;5%;COG;50V;CHIP;0201")
      (fields (field (name "APPROVED") "CL"))
      (libsource (lib "Giga-tronics") (part "CK35-00033"))
    )
    (comp (ref "C875")
      (value "3.3pF")
      (footprint "CAP-0201-N")
      (description "3.3pF;5%;COG;50V;CHIP;0201")
      (fields (field (name "APPROVED") "CL"))
      (libsource (lib "Giga-tronics") (part "CK35-00033"))
    )
    (comp (ref "C876")
      (value "3.3pF")
      (footprint "CAP-0201-N")
      (description "3.3pF;5%;COG;50V;CHIP;0201")
      (fields (field (name "APPROVED") "CL"))
      (libsource (lib "Giga-tronics") (part "CK35-00033"))
    )
    (comp (ref "C877")
      (value "3.3pF")
      (footprint "CAP-0201-N")
      (description "3.3pF;5%;COG;50V;CHIP;0201")
      (fields (field (name "APPROVED") "CL"))
      (libsource (lib "Giga-tronics") (part "CK35-00033"))
    )
    (comp (ref "C878")
      (value "3.3pF")
      (footprint "CAP-0201-N")
      (description "3.3pF;5%;COG;50V;CHIP;0201")
      (fields (field (name "APPROVED") "CL"))
      (libsource (lib "Giga-tronics") (part "CK35-00033"))
    )
    (comp (ref "C879")
      (value "3.3pF")
      (footprint "CAP-0201-N")
      (description "3.3pF;5%;COG;50V;CHIP;0201")
      (fields (field (name "APPROVED") "CL"))
      (libsource (lib "Giga-tronics") (part "CK35-00033"))
    )
    (comp (ref "C880")
      (value "33pF")
      (footprint "CAP-0402-N")
      (description "33 PF;5%;COG;>50V;CHIP;0402")
      (fields (field (name "APPROVED") "CL"))
      (libsource (lib "Giga-tronics") (part "CK40-00330"))
    )
    (comp (ref "C881")
      (value "12pF")
      (footprint "CAP-0402-N")
      (description "12 PF;5%;COG;>50V;CHIP;0402")
      (fields (field (name "APPROVED") "CL"))
      (libsource (lib "Giga-tronics") (part "CK40-00120"))
    )
    (comp (ref "C882")
      (value "1.8pF")
      (footprint "CAP-0402-RF")
      (description "1.8 PF;200V;.05PF;HIGH Q;SMT;CERAMIC;0402")
      (fields (field (name "APPROVED") "CL"))
      (libsource (lib "Giga-tronics") (part "CK41-00018"))
    )
    (comp (ref "C883")
      (value "33pF")
      (footprint "CAP-0402-N")
      (description "33 PF;5%;COG;>50V;CHIP;0402")
      (fields (field (name "APPROVED") "CL"))
      (libsource (lib "Giga-tronics") (part "CK40-00330"))
    )
    (comp (ref "C884")
      (value "0.7pF")
      (footprint "CAP-0402-RF")
      (description ".7 PF;200V;.05PF;HIGH Q;SMT;CERAMIC;0402")
      (fields (field (name "APPROVED") "CL"))
      (libsource (lib "Giga-tronics") (part "CK41-00007"))
    )
    (comp (ref "C885")
      (value "33pF")
      (footprint "CAP-0402-N")
      (description "33 PF;5%;COG;>50V;CHIP;0402")
      (fields (field (name "APPROVED") "CL"))
      (libsource (lib "Giga-tronics") (part "CK40-00330"))
    )
    (comp (ref "C886")
      (value "2.4pF")
      (footprint "CAP-0402-RF")
      (description "2.4 PF;200V;.05PF;HIGH Q;SMT;CERAMIC;0402")
      (fields (field (name "APPROVED") "CL"))
      (libsource (lib "Giga-tronics") (part "CK41-00024"))
    )
    (comp (ref "C887")
      (value "100pF")
      (footprint "CAP-0402-N")
      (description "100 PF;5%;COG;>50V;CHIP;0402")
      (fields (field (name "APPROVED") "CL"))
      (libsource (lib "Giga-tronics") (part "CK40-01100"))
    )
    (comp (ref "C888")
      (value "100pF")
      (footprint "CAP-0402-N")
      (description "100 PF;5%;COG;>50V;CHIP;0402")
      (fields (field (name "APPROVED") "CL"))
      (libsource (lib "Giga-tronics") (part "CK40-01100"))
    )
    (comp (ref "C889")
      (value "100pF")
      (footprint "CAP-0402-N")
      (description "100 PF;5%;COG;>50V;CHIP;0402")
      (fields (field (name "APPROVED") "CL"))
      (libsource (lib "Giga-tronics") (part "CK40-01100"))
    )
    (comp (ref "C890")
      (value "100pF")
      (footprint "CAP-0402-N")
      (description "100 PF;5%;COG;>50V;CHIP;0402")
      (fields (field (name "APPROVED") "CL"))
      (libsource (lib "Giga-tronics") (part "CK40-01100"))
    )
    (comp (ref "C891")
      (value "2.4pF")
      (footprint "CAP-0402-RF")
      (description "2.4 PF;200V;.05PF;HIGH Q;SMT;CERAMIC;0402")
      (fields (field (name "APPROVED") "CL"))
      (libsource (lib "Giga-tronics") (part "CK41-00024"))
    )
    (comp (ref "C892")
      (value "0.1uF")
      (footprint "CAP-0402-N")
      (description ".1 UF,10%;X7R;16V,CHIP;0402")
      (fields (field (name "APPROVED") "CL"))
      (libsource (lib "Giga-tronics") (part "CK40-04100"))
    )
    (comp (ref "C893")
      (value "2.4pF")
      (footprint "CAP-0402-RF")
      (description "2.4 PF;200V;.05PF;HIGH Q;SMT;CERAMIC;0402")
      (fields (field (name "APPROVED") "CL"))
      (libsource (lib "Giga-tronics") (part "CK41-00024"))
    )
    (comp (ref "C952")
      (value "12pF")
      (footprint "CAP-0402-N")
      (description "12 PF;5%;COG;>50V;CHIP;0402")
      (fields (field (name "APPROVED") "CL"))
      (libsource (lib "Giga-tronics") (part "CK40-00120"))
    )
    (comp (ref "C953")
      (value "2.4pF")
      (footprint "CAP-0402-RF")
      (description "2.4 PF;200V;.05PF;HIGH Q;SMT;CERAMIC;0402")
      (fields (field (name "APPROVED") "CL"))
      (libsource (lib "Giga-tronics") (part "CK41-00024"))
    )
    (comp (ref "C954")
      (value "2.4pF")
      (footprint "CAP-0402-RF")
      (description "2.4 PF;200V;.05PF;HIGH Q;SMT;CERAMIC;0402")
      (fields (field (name "APPROVED") "CL"))
      (libsource (lib "Giga-tronics") (part "CK41-00024"))
    )
    (comp (ref "C955")
      (value "2.4pF")
      (footprint "CAP-0402-RF")
      (description "2.4 PF;200V;.05PF;HIGH Q;SMT;CERAMIC;0402")
      (fields (field (name "APPROVED") "CL"))
      (libsource (lib "Giga-tronics") (part "CK41-00024"))
    )
    (comp (ref "C956")
      (value "10nF")
      (footprint "CAP-0402-N")
      (description "10nF;10%;X7R;16 WVDC;CHIP;0402")
      (fields (field (name "APPROVED") "CL"))
      (libsource (lib "Giga-tronics") (part "TCC3-03100"))
    )
    (comp (ref "C957")
      (value "10nF")
      (footprint "CAP-0402-N")
      (description "10nF;10%;X7R;16 WVDC;CHIP;0402")
      (fields (field (name "APPROVED") "CL"))
      (libsource (lib "Giga-tronics") (part "TCC3-03100"))
    )
    (comp (ref "C958")
      (value "10nF")
      (footprint "CAP-0402-N")
      (description "10nF;10%;X7R;16 WVDC;CHIP;0402")
      (fields (field (name "APPROVED") "CL"))
      (libsource (lib "Giga-tronics") (part "TCC3-03100"))
    )
    (comp (ref "C959")
      (value "12pF")
      (footprint "CAP-0402-N")
      (description "12 PF;5%;COG;>50V;CHIP;0402")
      (fields (field (name "NOLOAD") "N/L") (field (name "APPROVED") "CL"))
      (libsource (lib "Giga-tronics") (part "CK40-00120"))
    )
    (comp (ref "C961")
      (value "0.1uF")
      (footprint "CAP-0603-H035-N")
      (description ".1UF;10%;X7R;16V;CHIP;0603")
      (fields (field (name "APPROVED") "CL"))
      (libsource (lib "Giga-tronics") (part "CK45-04100"))
    )
    (comp (ref "C962")
      (value "12pF")
      (footprint "CAP-0402-N")
      (description "12 PF;5%;COG;>50V;CHIP;0402")
      (fields (field (name "APPROVED") "CL"))
      (libsource (lib "Giga-tronics") (part "CK40-00120"))
    )
    (comp (ref "C963")
      (value "12pF")
      (footprint "CAP-0402-N")
      (description "12 PF;5%;COG;>50V;CHIP;0402")
      (fields (field (name "APPROVED") "CL"))
      (libsource (lib "Giga-tronics") (part "CK40-00120"))
    )
    (comp (ref "C964")
      (value "12pF")
      (footprint "CAP-0402-N")
      (description "12 PF;5%;COG;>50V;CHIP;0402")
      (fields (field (name "APPROVED") "CL"))
      (libsource (lib "Giga-tronics") (part "CK40-00120"))
    )
    (comp (ref "C965")
      (value "2.4pF")
      (footprint "CAP-0402-RF")
      (description "2.4 PF;200V;.05PF;HIGH Q;SMT;CERAMIC;0402")
      (fields (field (name "APPROVED") "CL"))
      (libsource (lib "Giga-tronics") (part "CK41-00024"))
    )
    (comp (ref "C966")
      (value "2.4pF")
      (footprint "CAP-0402-RF")
      (description "2.4 PF;200V;.05PF;HIGH Q;SMT;CERAMIC;0402")
      (fields (field (name "APPROVED") "CL"))
      (libsource (lib "Giga-tronics") (part "CK41-00024"))
    )
    (comp (ref "C967")
      (value "2.4pF")
      (footprint "CAP-0402-RF")
      (description "2.4 PF;200V;.05PF;HIGH Q;SMT;CERAMIC;0402")
      (fields (field (name "APPROVED") "CL"))
      (libsource (lib "Giga-tronics") (part "CK41-00024"))
    )
    (comp (ref "C968")
      (value "10nF")
      (footprint "CAP-0402-N")
      (description "10nF;10%;X7R;16 WVDC;CHIP;0402")
      (fields (field (name "APPROVED") "CL"))
      (libsource (lib "Giga-tronics") (part "TCC3-03100"))
    )
    (comp (ref "C969")
      (value "470pF")
      (footprint "CAP-0402-N")
      (description "470 PF;5%;COG;>50V;CHIP;0402")
      (fields (field (name "APPROVED") "CL"))
      (libsource (lib "Giga-tronics") (part "CK40-01470"))
    )
    (comp (ref "C970")
      (value "470pF")
      (footprint "CAP-0402-N")
      (description "470 PF;5%;COG;>50V;CHIP;0402")
      (fields (field (name "APPROVED") "CL"))
      (libsource (lib "Giga-tronics") (part "CK40-01470"))
    )
    (comp (ref "C1224")
      (value "0.1uF")
      (footprint "CAP-0603-H035-N")
      (description ".1UF;10%;X7R;16V;CHIP;0603")
      (fields (field (name "APPROVED") "CL"))
      (libsource (lib "Giga-tronics") (part "CK45-04100"))
    )
    (comp (ref "C1225")
      (value "470pF")
      (footprint "CAP-0402-N")
      (description "470 PF;5%;COG;>50V;CHIP;0402")
      (fields (field (name "APPROVED") "CL"))
      (libsource (lib "Giga-tronics") (part "CK40-01470"))
    )
    (comp (ref "C1226")
      (value "470pF")
      (footprint "CAP-0402-N")
      (description "470 PF;5%;COG;>50V;CHIP;0402")
      (fields (field (name "APPROVED") "CL"))
      (libsource (lib "Giga-tronics") (part "CK40-01470"))
    )
    (comp (ref "C1227")
      (value "470pF")
      (footprint "CAP-0402-N")
      (description "470 PF;5%;COG;>50V;CHIP;0402")
      (fields (field (name "APPROVED") "CL"))
      (libsource (lib "Giga-tronics") (part "CK40-01470"))
    )
    (comp (ref "C1228")
      (value "470pF")
      (footprint "CAP-0402-N")
      (description "470 PF;5%;COG;>50V;CHIP;0402")
      (fields (field (name "APPROVED") "CL"))
      (libsource (lib "Giga-tronics") (part "CK40-01470"))
    )
    (comp (ref "C1229")
      (value "470pF")
      (footprint "CAP-0402-N")
      (description "470 PF;5%;COG;>50V;CHIP;0402")
      (fields (field (name "APPROVED") "CL"))
      (libsource (lib "Giga-tronics") (part "CK40-01470"))
    )
    (comp (ref "FL11")
      (value "Filter EMI 2200PF,1206")
      (footprint "FIL-NFE31P-1206-4P")
      (fields (field (name "G_PN") "LFS0-00222") (field (name "APPROVED") "CL"))
      (libsource (lib "Giga-tronics") (part "LFS0-00222"))
    )
    (comp (ref "FL22")
      (value "Filter EMI 2200PF,1206")
      (footprint "FIL-NFE31P-1206-4P")
      (fields (field (name "G_PN") "LFS0-00222") (field (name "APPROVED") "CL"))
      (libsource (lib "Giga-tronics") (part "LFS0-00222"))
    )
    (comp (ref "FL23")
      (value "Filter EMI 2200PF,1206")
      (footprint "FIL-NFE31P-1206-4P")
      (fields (field (name "G_PN") "LFS0-00222") (field (name "APPROVED") "CL"))
      (libsource (lib "") (part "LFS0-00222_3"))
    )
    (comp (ref "FL27")
      (value "FILTER;CER;BANDPASS;3600MHZ;200MHZ BW;6-SEC;SMT")
      (footprint "S11H_IMC")
      (fields (field (name "G_PN") "MFB0-13600") (field (name "APPROVED") "CL"))
      (libsource (lib "Giga-tronics") (part "MFB0-13600"))
    )
    (comp (ref "FL28")
      (value "FILTER;CER;BANDPASS;3600MHZ;200MHZ BW;6-SEC;SMT")
      (footprint "S11H_IMC")
      (fields (field (name "G_PN") "MFB0-13600") (field (name "APPROVED") "CL"))
      (libsource (lib "Giga-tronics") (part "MFB0-13600"))
    )
    (comp (ref "FL29")
      (value "FILTER;CER;BANDPASS;3200MHZ;200MHZ BW;6-SEC;SMT")
      (footprint "S11H_IMC")
      (fields (field (name "G_PN") "MFB0-13200") (field (name "APPROVED") "CL"))
      (libsource (lib "Giga-tronics") (part "MFB0-13200"))
    )
    (comp (ref "FL33")
      (value "FILTER;CER;BANDPASS;3200MHZ;200MHZ BW;6-SEC;SMT")
      (footprint "S11H_IMC")
      (fields (field (name "G_PN") "MFB0-13200") (field (name "APPROVED") "CL"))
      (libsource (lib "Giga-tronics") (part "MFB0-13200"))
    )
    (comp (ref "FL34")
      (value "FILTER;CER;BANDPASS;2800MHZ;200MHZ BW;6-SEC;SMT")
      (footprint "S11H_IMC")
      (fields (field (name "G_PN") "MFB0-12800") (field (name "APPROVED") "CL"))
      (libsource (lib "Giga-tronics") (part "MFB0-12800"))
    )
    (comp (ref "FL37")
      (value "FILTER;CER;BANDPASS;2800MHZ;200MHZ BW;6-SEC;SMT")
      (footprint "S11H_IMC")
      (fields (field (name "G_PN") "MFB0-12800") (field (name "APPROVED") "CL"))
      (libsource (lib "Giga-tronics") (part "MFB0-12800"))
    )
    (comp (ref "FL39")
      (value "FILTER;LOW PASS;3900MHz;7SEC;FV1206")
      (footprint "FV1206")
      (fields (field (name "G_PN") "MFL0-03900") (field (name "APPROVED") "NM"))
      (libsource (lib "Giga-tronics") (part "MFL0-03900"))
    )
    (comp (ref "FL43")
      (value "FILTER;CER;BANDPASS;2800MHZ;200MHZ BW;6-SEC;SMT")
      (footprint "S11H_IMC")
      (fields (field (name "G_PN") "MFB0-13000") (field (name "APPROVED") "CL"))
      (libsource (lib "Giga-tronics") (part "MFB0-13000"))
    )
    (comp (ref "FL45")
      (value "Filter EMI 2200PF,1206")
      (footprint "FIL-NFE31P-1206-4P")
      (fields (field (name "G_PN") "LFS0-00222") (field (name "APPROVED") "CL"))
      (libsource (lib "Giga-tronics") (part "LFS0-00222"))
    )
    (comp (ref "FL47")
      (value "F/T FILTER;CHIP;2.5 DCR150MA;16V;T LC;25PF;200MHz;0603")
      (footprint "FIL-NFL18ST")
      (fields (field (name "G_PN") "LFS0-00250") (field (name "APPROVED") "NM"))
      (libsource (lib "Giga-tronics") (part "LFS0-00250"))
    )
    (comp (ref "FL48")
      (value "FILTER;LOW PASS;3900MHz;7SEC;FV1206")
      (footprint "FV1206")
      (fields (field (name "G_PN") "MFL0-03900") (field (name "APPROVED") "NM"))
      (libsource (lib "Giga-tronics") (part "MFL0-03900"))
    )
    (comp (ref "FL49")
      (value "Filter EMI 2200PF,1206")
      (footprint "FIL-NFE31P-1206-4P")
      (fields (field (name "G_PN") "LFS0-00222") (field (name "APPROVED") "CL"))
      (libsource (lib "") (part "LFS0-00222_3"))
    )
    (comp (ref "FL50")
      (value "Filter EMI 2200PF,1206")
      (footprint "FIL-NFE31P-1206-4P")
      (fields (field (name "G_PN") "LFS0-00222") (field (name "APPROVED") "CL"))
      (libsource (lib "Giga-tronics") (part "LFS0-00222"))
    )
    (comp (ref "FL51")
      (value "F/T FILTER;CHIP;2.5 DCR150MA;16V;T LC;25PF;200MHz;0603")
      (footprint "FIL-NFL18ST")
      (fields (field (name "G_PN") "LFS0-00250") (field (name "APPROVED") "NM"))
      (libsource (lib "Giga-tronics") (part "LFS0-00250"))
    )
    (comp (ref "FL151")
      (value "FILTER;CER;BANDPASS;2800MHZ;200MHZ BW;6-SEC;SMT")
      (footprint "S11H_IMC")
      (fields (field (name "G_PN") "MFB0-13000") (field (name "APPROVED") "CL"))
      (libsource (lib "Giga-tronics") (part "MFB0-13000"))
    )
    (comp (ref "FL152")
      (value "FILTER;CER;BANDPASS;3400MHZ;200MHZ BW;6-SEC;SMT")
      (footprint "S11H_IMC")
      (fields (field (name "G_PN") "MFB0-13400") (field (name "APPROVED") "CL"))
      (libsource (lib "Giga-tronics") (part "MFB0-13400"))
    )
    (comp (ref "FL153")
      (value "FILTER;CER;BANDPASS;3400MHZ;200MHZ BW;6-SEC;SMT")
      (footprint "S11H_IMC")
      (fields (field (name "G_PN") "MFB0-13400") (field (name "APPROVED") "CL"))
      (libsource (lib "Giga-tronics") (part "MFB0-13400"))
    )
    (comp (ref "FL173")
      (value "FILTER;CER;BANDPASS;3800MHZ;200MHZ BW;6-SEC;SMT")
      (footprint "S11H_IMC")
      (fields (field (name "G_PN") "MFB0-13800") (field (name "APPROVED") "CL"))
      (libsource (lib "Giga-tronics") (part "MFB0-13800"))
    )
    (comp (ref "FL190")
      (value "FILTER;CER;BANDPASS;3800MHZ;200MHZ BW;6-SEC;SMT")
      (footprint "S11H_IMC")
      (fields (field (name "G_PN") "MFB0-13800") (field (name "APPROVED") "CL"))
      (libsource (lib "Giga-tronics") (part "MFB0-13800"))
    )
    (comp (ref "FL500")
      (value "2200pF")
      (footprint "FIL-NFE31P-1206-4P")
      (description "Filter EMI 2200PF,1206")
      (fields (field (name "APPROVED") "CL"))
      (libsource (lib "") (part "LFS0-00222_1"))
    )
    (comp (ref "FL501")
      (value "2200pF")
      (footprint "FIL-NFE31P-1206-4P")
      (description "Filter EMI 2200PF,1206")
      (fields (field (name "APPROVED") "CL"))
      (libsource (lib "") (part "LFS0-00222_1"))
    )
    (comp (ref "FL506")
      (value "2200pF")
      (footprint "FIL-NFE31P-1206-4P")
      (description "Filter EMI 2200PF,1206")
      (fields (field (name "APPROVED") "CL"))
      (libsource (lib "") (part "LFS0-00222_2"))
    )
    (comp (ref "FT7")
      (value "STALO_2")
      (footprint "FromToNode_ML2")
      (fields (field (name "NOLOAD") "N/L") (field (name "APPROVED") "*"))
      (libsource (lib "Giga-tronics") (part "FromToNode"))
    )
    (comp (ref "FT18")
      (value "STALO_2")
      (footprint "FromToNode_ML2")
      (fields (field (name "NOLOAD") "N/L") (field (name "APPROVED") "*"))
      (libsource (lib "Giga-tronics") (part "FromToNode"))
    )
    (comp (ref "FT33")
      (value "STALO_2")
      (footprint "FromToNode_ML2")
      (fields (field (name "NOLOAD") "N/L") (field (name "APPROVED") "*"))
      (libsource (lib "Giga-tronics") (part "FromToNode"))
    )
    (comp (ref "J2")
      (value ".")
      (footprint "JRSM-70101")
      (description "SMPM FD MALE,STRAIGHT SMT, R/A COPLANAR, 4 PIN THRU-HOLE")
      (fields (field (name "G_PN") "JRSM-70101") (field (name "APPROVED") "CL"))
      (libsource (lib "Giga-tronics") (part "JRSM-70101"))
    )
    (comp (ref "J25")
      (value "SMPM;SB;MALE;STRAIGHT;SMT;.152X.152X.150;PCB;R/A CONTACT")
      (footprint "JRSM-40101")
      (fields (field (name "NOLOAD") "N/L") (field (name "APPROVED") "CL"))
      (libsource (lib "Giga-tronics") (part "JRSM-40101"))
    )
    (comp (ref "L5")
      (value "40nH")
      (footprint "IND-0402CS")
      (description "INDUCTOR,40 NH SM 0402 PKG")
      (fields (field (name "APPROVED") "CL"))
      (libsource (lib "Giga-tronics") (part "13000220-400"))
    )
    (comp (ref "L8")
      (value "INDUCTOR;3.9NH;2%;9.5GHZ SRF;98Q @1.7GHZ;.045 DCR;1.7A;0402")
      (footprint "IND-0402HP")
      (fields (field (name "NOLOAD") "N/L") (field (name "APPROVED") "CL"))
      (libsource (lib "Giga-tronics") (part "LSA6-02390"))
    )
    (comp (ref "L9")
      (value "INDUCTOR;3.9NH;2%;9.5GHZ SRF;98Q @1.7GHZ;.045 DCR;1.7A;0402")
      (footprint "IND-0402HP")
      (fields (field (name "NOLOAD") "N/L") (field (name "APPROVED") "CL"))
      (libsource (lib "Giga-tronics") (part "LSA6-02390"))
    )
    (comp (ref "L10")
      (value "INDUCTOR;3.9NH;2%;9.5GHZ SRF;98Q @1.7GHZ;.045 DCR;1.7A;0402")
      (footprint "IND-0402HP")
      (fields (field (name "NOLOAD") "N/L") (field (name "APPROVED") "CL"))
      (libsource (lib "Giga-tronics") (part "LSA6-02390"))
    )
    (comp (ref "L11")
      (value "INDUCTOR;3.9NH;2%;9.5GHZ SRF;98Q @1.7GHZ;.045 DCR;1.7A;0402")
      (footprint "IND-0402HP")
      (fields (field (name "NOLOAD") "N/L") (field (name "APPROVED") "CL"))
      (libsource (lib "Giga-tronics") (part "LSA6-02390"))
    )
    (comp (ref "L12")
      (value "15nH")
      (footprint "IND-0402HP")
      (description "INDUCTOR;15NH;2%;3.9GHZ SRF;85Q @1.7GHZ;.078 DCR;1.1A;0402")
      (fields (field (name "APPROVED") "CL"))
      (libsource (lib "") (part "LSA6-03150_1"))
    )
    (comp (ref "L13")
      (value "15nH")
      (footprint "IND-0402HP")
      (description "INDUCTOR;15NH;2%;3.9GHZ SRF;85Q @1.7GHZ;.078 DCR;1.1A;0402")
      (fields (field (name "APPROVED") "CL"))
      (libsource (lib "Giga-tronics") (part "LSA6-03150"))
    )
    (comp (ref "L15")
      (value "15nH")
      (footprint "IND-0402HP")
      (description "INDUCTOR;15NH;2%;3.9GHZ SRF;85Q @1.7GHZ;.078 DCR;1.1A;0402")
      (fields (field (name "APPROVED") "CL"))
      (libsource (lib "") (part "LSA6-03150_1"))
    )
    (comp (ref "L16")
      (value "15nH")
      (footprint "IND-0402HP")
      (description "INDUCTOR;15NH;2%;3.9GHZ SRF;85Q @1.7GHZ;.078 DCR;1.1A;0402")
      (fields (field (name "APPROVED") "CL"))
      (libsource (lib "Giga-tronics") (part "LSA6-03150"))
    )
    (comp (ref "L17")
      (value "INDUCTOR;3.9NH;2%;9.5GHZ SRF;98Q @1.7GHZ;.045 DCR;1.7A;0402")
      (footprint "IND-0402HP")
      (fields (field (name "NOLOAD") "N/L") (field (name "APPROVED") "CL"))
      (libsource (lib "Giga-tronics") (part "LSA6-02390"))
    )
    (comp (ref "L18")
      (value "INDUCTOR;3.9NH;2%;9.5GHZ SRF;98Q @1.7GHZ;.045 DCR;1.7A;0402")
      (footprint "IND-0402HP")
      (fields (field (name "NOLOAD") "N/L") (field (name "APPROVED") "CL"))
      (libsource (lib "Giga-tronics") (part "LSA6-02390"))
    )
    (comp (ref "L19")
      (value "15nH")
      (footprint "IND-0402HP")
      (description "INDUCTOR;15NH;2%;3.9GHZ SRF;85Q @1.7GHZ;.078 DCR;1.1A;0402")
      (fields (field (name "APPROVED") "CL"))
      (libsource (lib "Giga-tronics") (part "LSA6-03150"))
    )
    (comp (ref "L20")
      (value "15nH")
      (footprint "IND-0402HP")
      (description "INDUCTOR;15NH;2%;3.9GHZ SRF;85Q @1.7GHZ;.078 DCR;1.1A;0402")
      (fields (field (name "APPROVED") "CL"))
      (libsource (lib "Giga-tronics") (part "LSA6-03150"))
    )
    (comp (ref "L54")
      (value "INDUCTOR;3.9NH;2%;9.5GHZ SRF;98Q @1.7GHZ;.045 DCR;1.7A;0402")
      (footprint "IND-0402HP")
      (fields (field (name "NOLOAD") "N/L") (field (name "APPROVED") "CL"))
      (libsource (lib "Giga-tronics") (part "LSA6-02390"))
    )
    (comp (ref "L55")
      (value "INDUCTOR;3.9NH;2%;9.5GHZ SRF;98Q @1.7GHZ;.045 DCR;1.7A;0402")
      (footprint "IND-0402HP")
      (fields (field (name "NOLOAD") "N/L") (field (name "APPROVED") "CL"))
      (libsource (lib "Giga-tronics") (part "LSA6-02390"))
    )
    (comp (ref "L56")
      (value "15nH")
      (footprint "IND-0402HP")
      (description "INDUCTOR;15NH;2%;3.9GHZ SRF;85Q @1.7GHZ;.078 DCR;1.1A;0402")
      (fields (field (name "APPROVED") "CL"))
      (libsource (lib "") (part "LSA6-03150_1"))
    )
    (comp (ref "L57")
      (value "15nH")
      (footprint "IND-0402HP")
      (description "INDUCTOR;15NH;2%;3.9GHZ SRF;85Q @1.7GHZ;.078 DCR;1.1A;0402")
      (fields (field (name "APPROVED") "CL"))
      (libsource (lib "Giga-tronics") (part "LSA6-03150"))
    )
    (comp (ref "L59")
      (value "15nH")
      (footprint "IND-0402HP")
      (description "INDUCTOR;15NH;2%;3.9GHZ SRF;85Q @1.7GHZ;.078 DCR;1.1A;0402")
      (fields (field (name "APPROVED") "CL"))
      (libsource (lib "") (part "LSA6-03150_1"))
    )
    (comp (ref "L65")
      (value "15nH")
      (footprint "IND-0402HP")
      (description "INDUCTOR;15NH;2%;3.9GHZ SRF;85Q @1.7GHZ;.078 DCR;1.1A;0402")
      (fields (field (name "APPROVED") "CL"))
      (libsource (lib "Giga-tronics") (part "LSA6-03150"))
    )
    (comp (ref "L66")
      (value "15nH")
      (footprint "IND-0402HP")
      (description "INDUCTOR;15NH;2%;3.9GHZ SRF;85Q @1.7GHZ;.078 DCR;1.1A;0402")
      (fields (field (name "APPROVED") "CL"))
      (libsource (lib "Giga-tronics") (part "LSA6-03150"))
    )
    (comp (ref "L67")
      (value "15nH")
      (footprint "IND-0402HP")
      (description "INDUCTOR;15NH;2%;3.9GHZ SRF;85Q @1.7GHZ;.078 DCR;1.1A;0402")
      (fields (field (name "APPROVED") "CL"))
      (libsource (lib "Giga-tronics") (part "LSA6-03150"))
    )
    (comp (ref "L68")
      (value "15nH")
      (footprint "IND-0402HP")
      (description "INDUCTOR;15NH;2%;3.9GHZ SRF;85Q @1.7GHZ;.078 DCR;1.1A;0402")
      (fields (field (name "APPROVED") "CL"))
      (libsource (lib "Giga-tronics") (part "LSA6-03150"))
    )
    (comp (ref "L69")
      (value "15nH")
      (footprint "IND-0402HP")
      (description "INDUCTOR;15NH;2%;3.9GHZ SRF;85Q @1.7GHZ;.078 DCR;1.1A;0402")
      (fields (field (name "APPROVED") "CL"))
      (libsource (lib "Giga-tronics") (part "LSA6-03150"))
    )
    (comp (ref "L71")
      (value "15nH")
      (footprint "IND-0402HP")
      (description "INDUCTOR;15NH;2%;3.9GHZ SRF;85Q @1.7GHZ;.078 DCR;1.1A;0402")
      (fields (field (name "APPROVED") "CL"))
      (libsource (lib "Giga-tronics") (part "LSA6-03150"))
    )
    (comp (ref "L73")
      (value "15nH")
      (footprint "IND-0402HP")
      (description "INDUCTOR;15NH;2%;3.9GHZ SRF;85Q @1.7GHZ;.078 DCR;1.1A;0402")
      (fields (field (name "APPROVED") "CL"))
      (libsource (lib "Giga-tronics") (part "LSA6-03150"))
    )
    (comp (ref "L76")
      (value "15nH")
      (footprint "IND-0402HP")
      (description "INDUCTOR;15NH;2%;3.9GHZ SRF;85Q @1.7GHZ;.078 DCR;1.1A;0402")
      (fields (field (name "APPROVED") "CL"))
      (libsource (lib "Giga-tronics") (part "LSA6-03150"))
    )
    (comp (ref "L77")
      (value "15nH")
      (footprint "IND-0402HP")
      (description "INDUCTOR;15NH;2%;3.9GHZ SRF;85Q @1.7GHZ;.078 DCR;1.1A;0402")
      (fields (field (name "APPROVED") "CL"))
      (libsource (lib "Giga-tronics") (part "LSA6-03150"))
    )
    (comp (ref "L78")
      (value "INDUCTOR;3.9NH;2%;9.5GHZ SRF;98Q @1.7GHZ;.045 DCR;1.7A;0402")
      (footprint "IND-0402HP")
      (fields (field (name "NOLOAD") "N/L") (field (name "APPROVED") "CL"))
      (libsource (lib "Giga-tronics") (part "LSA6-02390"))
    )
    (comp (ref "L79")
      (value "INDUCTOR;3.9NH;2%;9.5GHZ SRF;98Q @1.7GHZ;.045 DCR;1.7A;0402")
      (footprint "IND-0402HP")
      (fields (field (name "NOLOAD") "N/L") (field (name "APPROVED") "CL"))
      (libsource (lib "Giga-tronics") (part "LSA6-02390"))
    )
    (comp (ref "L84")
      (value "INDUCTOR;3.9NH;2%;9.5GHZ SRF;98Q @1.7GHZ;.045 DCR;1.7A;0402")
      (footprint "IND-0402HP")
      (fields (field (name "NOLOAD") "N/L") (field (name "APPROVED") "CL"))
      (libsource (lib "Giga-tronics") (part "LSA6-02390"))
    )
    (comp (ref "L85")
      (value "INDUCTOR;3.9NH;2%;9.5GHZ SRF;98Q @1.7GHZ;.045 DCR;1.7A;0402")
      (footprint "IND-0402HP")
      (fields (field (name "NOLOAD") "N/L") (field (name "APPROVED") "CL"))
      (libsource (lib "Giga-tronics") (part "LSA6-02390"))
    )
    (comp (ref "L88")
      (value "15nH")
      (footprint "IND-0402HP")
      (description "INDUCTOR;15NH;2%;3.9GHZ SRF;85Q @1.7GHZ;.078 DCR;1.1A;0402")
      (fields (field (name "APPROVED") "CL"))
      (libsource (lib "") (part "LSA6-03150_1"))
    )
    (comp (ref "L89")
      (value "40nH")
      (footprint "IND-0402CS")
      (description "INDUCTOR,40 NH SM 0402 PKG")
      (fields (field (name "APPROVED") "CL"))
      (libsource (lib "Giga-tronics") (part "13000220-400"))
    )
    (comp (ref "L90")
      (value "15nH")
      (footprint "IND-0402HP")
      (description "INDUCTOR;15NH;2%;3.9GHZ SRF;85Q @1.7GHZ;.078 DCR;1.1A;0402")
      (fields (field (name "APPROVED") "CL"))
      (libsource (lib "") (part "LSA6-03150_1"))
    )
    (comp (ref "L149")
      (value "15nH")
      (footprint "IND-0402HP")
      (description "INDUCTOR;15NH;2%;3.9GHZ SRF;85Q @1.7GHZ;.078 DCR;1.1A;0402")
      (fields (field (name "APPROVED") "CL"))
      (libsource (lib "Giga-tronics") (part "LSA6-03150"))
    )
    (comp (ref "L150")
      (value "15nH")
      (footprint "IND-0402HP")
      (description "INDUCTOR;15NH;2%;3.9GHZ SRF;85Q @1.7GHZ;.078 DCR;1.1A;0402")
      (fields (field (name "APPROVED") "CL"))
      (libsource (lib "") (part "LSA6-03150_1"))
    )
    (comp (ref "L151")
      (value "15nH")
      (footprint "IND-0402HP")
      (description "INDUCTOR;15NH;2%;3.9GHZ SRF;85Q @1.7GHZ;.078 DCR;1.1A;0402")
      (fields (field (name "APPROVED") "CL"))
      (libsource (lib "Giga-tronics") (part "LSA6-03150"))
    )
    (comp (ref "L152")
      (value "15nH")
      (footprint "IND-0402HP")
      (description "INDUCTOR;15NH;2%;3.9GHZ SRF;85Q @1.7GHZ;.078 DCR;1.1A;0402")
      (fields (field (name "APPROVED") "CL"))
      (libsource (lib "Giga-tronics") (part "LSA6-03150"))
    )
    (comp (ref "L153")
      (value "INDUCTOR;3.9NH;2%;9.5GHZ SRF;98Q @1.7GHZ;.045 DCR;1.7A;0402")
      (footprint "IND-0402HP")
      (fields (field (name "NOLOAD") "N/L") (field (name "APPROVED") "CL"))
      (libsource (lib "Giga-tronics") (part "LSA6-02390"))
    )
    (comp (ref "L154")
      (value "INDUCTOR;3.9NH;2%;9.5GHZ SRF;98Q @1.7GHZ;.045 DCR;1.7A;0402")
      (footprint "IND-0402HP")
      (fields (field (name "NOLOAD") "N/L") (field (name "APPROVED") "CL"))
      (libsource (lib "Giga-tronics") (part "LSA6-02390"))
    )
    (comp (ref "L155")
      (value "INDUCTOR;3.9NH;2%;9.5GHZ SRF;98Q @1.7GHZ;.045 DCR;1.7A;0402")
      (footprint "IND-0402HP")
      (fields (field (name "NOLOAD") "N/L") (field (name "APPROVED") "CL"))
      (libsource (lib "Giga-tronics") (part "LSA6-02390"))
    )
    (comp (ref "L156")
      (value "15nH")
      (footprint "IND-0402HP")
      (description "INDUCTOR;15NH;2%;3.9GHZ SRF;85Q @1.7GHZ;.078 DCR;1.1A;0402")
      (fields (field (name "APPROVED") "CL"))
      (libsource (lib "Giga-tronics") (part "LSA6-03150"))
    )
    (comp (ref "L157")
      (value "INDUCTOR;3.9NH;2%;9.5GHZ SRF;98Q @1.7GHZ;.045 DCR;1.7A;0402")
      (footprint "IND-0402HP")
      (fields (field (name "NOLOAD") "N/L") (field (name "APPROVED") "CL"))
      (libsource (lib "Giga-tronics") (part "LSA6-02390"))
    )
    (comp (ref "L158")
      (value "15nH")
      (footprint "IND-0402HP")
      (description "INDUCTOR;15NH;2%;3.9GHZ SRF;85Q @1.7GHZ;.078 DCR;1.1A;0402")
      (fields (field (name "APPROVED") "CL"))
      (libsource (lib "Giga-tronics") (part "LSA6-03150"))
    )
    (comp (ref "L159")
      (value "15nH")
      (footprint "IND-0402HP")
      (description "INDUCTOR;15NH;2%;3.9GHZ SRF;85Q @1.7GHZ;.078 DCR;1.1A;0402")
      (fields (field (name "APPROVED") "CL"))
      (libsource (lib "") (part "LSA6-03150_1"))
    )
    (comp (ref "L160")
      (value "15nH")
      (footprint "IND-0402HP")
      (description "INDUCTOR;15NH;2%;3.9GHZ SRF;85Q @1.7GHZ;.078 DCR;1.1A;0402")
      (fields (field (name "APPROVED") "CL"))
      (libsource (lib "Giga-tronics") (part "LSA6-03150"))
    )
    (comp (ref "L161")
      (value "15nH")
      (footprint "IND-0402HP")
      (description "INDUCTOR;15NH;2%;3.9GHZ SRF;85Q @1.7GHZ;.078 DCR;1.1A;0402")
      (fields (field (name "APPROVED") "CL"))
      (libsource (lib "") (part "LSA6-03150_1"))
    )
    (comp (ref "L162")
      (value "15nH")
      (footprint "IND-0402HP")
      (description "INDUCTOR;15NH;2%;3.9GHZ SRF;85Q @1.7GHZ;.078 DCR;1.1A;0402")
      (fields (field (name "APPROVED") "CL"))
      (libsource (lib "Giga-tronics") (part "LSA6-03150"))
    )
    (comp (ref "L206")
      (value "15nH")
      (footprint "IND-0402HP")
      (description "INDUCTOR;15NH;2%;3.9GHZ SRF;85Q @1.7GHZ;.078 DCR;1.1A;0402")
      (fields (field (name "APPROVED") "CL"))
      (libsource (lib "") (part "LSA6-03150_1"))
    )
    (comp (ref "L229")
      (value "15nH")
      (footprint "IND-0402HP")
      (description "INDUCTOR;15NH;2%;3.9GHZ SRF;85Q @1.7GHZ;.078 DCR;1.1A;0402")
      (fields (field (name "APPROVED") "CL"))
      (libsource (lib "Giga-tronics") (part "LSA6-03150"))
    )
    (comp (ref "L230")
      (value "15nH")
      (footprint "IND-0402HP")
      (description "INDUCTOR;15NH;2%;3.9GHZ SRF;85Q @1.7GHZ;.078 DCR;1.1A;0402")
      (fields (field (name "APPROVED") "CL"))
      (libsource (lib "Giga-tronics") (part "LSA6-03150"))
    )
    (comp (ref "L231")
      (value "INDUCTOR;3.9NH;2%;9.5GHZ SRF;98Q @1.7GHZ;.045 DCR;1.7A;0402")
      (footprint "IND-0402HP")
      (fields (field (name "NOLOAD") "N/L") (field (name "APPROVED") "CL"))
      (libsource (lib "Giga-tronics") (part "LSA6-02390"))
    )
    (comp (ref "L232")
      (value "INDUCTOR;3.9NH;2%;9.5GHZ SRF;98Q @1.7GHZ;.045 DCR;1.7A;0402")
      (footprint "IND-0402HP")
      (fields (field (name "NOLOAD") "N/L") (field (name "APPROVED") "CL"))
      (libsource (lib "Giga-tronics") (part "LSA6-02390"))
    )
    (comp (ref "L233")
      (value "INDUCTOR;3.9NH;2%;9.5GHZ SRF;98Q @1.7GHZ;.045 DCR;1.7A;0402")
      (footprint "IND-0402HP")
      (fields (field (name "NOLOAD") "N/L") (field (name "APPROVED") "CL"))
      (libsource (lib "Giga-tronics") (part "LSA6-02390"))
    )
    (comp (ref "L234")
      (value "INDUCTOR;3.9NH;2%;9.5GHZ SRF;98Q @1.7GHZ;.045 DCR;1.7A;0402")
      (footprint "IND-0402HP")
      (fields (field (name "NOLOAD") "N/L") (field (name "APPROVED") "CL"))
      (libsource (lib "Giga-tronics") (part "LSA6-02390"))
    )
    (comp (ref "L235")
      (value "15nH")
      (footprint "IND-0402HP")
      (description "INDUCTOR;15NH;2%;3.9GHZ SRF;85Q @1.7GHZ;.078 DCR;1.1A;0402")
      (fields (field (name "APPROVED") "CL"))
      (libsource (lib "Giga-tronics") (part "LSA6-03150"))
    )
    (comp (ref "L236")
      (value "15nH")
      (footprint "IND-0402HP")
      (description "INDUCTOR;15NH;2%;3.9GHZ SRF;85Q @1.7GHZ;.078 DCR;1.1A;0402")
      (fields (field (name "APPROVED") "CL"))
      (libsource (lib "") (part "LSA6-03150_1"))
    )
    (comp (ref "L237")
      (value "15nH")
      (footprint "IND-0402HP")
      (description "INDUCTOR;15NH;2%;3.9GHZ SRF;85Q @1.7GHZ;.078 DCR;1.1A;0402")
      (fields (field (name "APPROVED") "CL"))
      (libsource (lib "Giga-tronics") (part "LSA6-03150"))
    )
    (comp (ref "L238")
      (value "15nH")
      (footprint "IND-0402HP")
      (description "INDUCTOR;15NH;2%;3.9GHZ SRF;85Q @1.7GHZ;.078 DCR;1.1A;0402")
      (fields (field (name "APPROVED") "CL"))
      (libsource (lib "") (part "LSA6-03150_1"))
    )
    (comp (ref "L239")
      (value "15nH")
      (footprint "IND-0402HP")
      (description "INDUCTOR;15NH;2%;3.9GHZ SRF;85Q @1.7GHZ;.078 DCR;1.1A;0402")
      (fields (field (name "APPROVED") "CL"))
      (libsource (lib "Giga-tronics") (part "LSA6-03150"))
    )
    (comp (ref "L240")
      (value "INDUCTOR;3.9NH;2%;9.5GHZ SRF;98Q @1.7GHZ;.045 DCR;1.7A;0402")
      (footprint "IND-0402HP")
      (fields (field (name "NOLOAD") "N/L") (field (name "APPROVED") "CL"))
      (libsource (lib "Giga-tronics") (part "LSA6-02390"))
    )
    (comp (ref "L241")
      (value "INDUCTOR;3.9NH;2%;9.5GHZ SRF;98Q @1.7GHZ;.045 DCR;1.7A;0402")
      (footprint "IND-0402HP")
      (fields (field (name "NOLOAD") "N/L") (field (name "APPROVED") "CL"))
      (libsource (lib "Giga-tronics") (part "LSA6-02390"))
    )
    (comp (ref "L242")
      (value "INDUCTOR;3.9NH;2%;9.5GHZ SRF;98Q @1.7GHZ;.045 DCR;1.7A;0402")
      (footprint "IND-0402HP")
      (fields (field (name "NOLOAD") "N/L") (field (name "APPROVED") "CL"))
      (libsource (lib "Giga-tronics") (part "LSA6-02390"))
    )
    (comp (ref "L243")
      (value "INDUCTOR;3.9NH;2%;9.5GHZ SRF;98Q @1.7GHZ;.045 DCR;1.7A;0402")
      (footprint "IND-0402HP")
      (fields (field (name "NOLOAD") "N/L") (field (name "APPROVED") "CL"))
      (libsource (lib "Giga-tronics") (part "LSA6-02390"))
    )
    (comp (ref "L244")
      (value "15nH")
      (footprint "IND-0402HP")
      (description "INDUCTOR;15NH;2%;3.9GHZ SRF;85Q @1.7GHZ;.078 DCR;1.1A;0402")
      (fields (field (name "APPROVED") "CL"))
      (libsource (lib "") (part "LSA6-03150_1"))
    )
    (comp (ref "L245")
      (value "15nH")
      (footprint "IND-0402HP")
      (description "INDUCTOR;15NH;2%;3.9GHZ SRF;85Q @1.7GHZ;.078 DCR;1.1A;0402")
      (fields (field (name "APPROVED") "CL"))
      (libsource (lib "Giga-tronics") (part "LSA6-03150"))
    )
    (comp (ref "L246")
      (value "15nH")
      (footprint "IND-0402HP")
      (description "INDUCTOR;15NH;2%;3.9GHZ SRF;85Q @1.7GHZ;.078 DCR;1.1A;0402")
      (fields (field (name "APPROVED") "CL"))
      (libsource (lib "") (part "LSA6-03150_1"))
    )
    (comp (ref "L247")
      (value "15nH")
      (footprint "IND-0402HP")
      (description "INDUCTOR;15NH;2%;3.9GHZ SRF;85Q @1.7GHZ;.078 DCR;1.1A;0402")
      (fields (field (name "APPROVED") "CL"))
      (libsource (lib "Giga-tronics") (part "LSA6-03150"))
    )
    (comp (ref "L248")
      (value "15nH")
      (footprint "IND-0402HP")
      (description "INDUCTOR;15NH;2%;3.9GHZ SRF;85Q @1.7GHZ;.078 DCR;1.1A;0402")
      (fields (field (name "APPROVED") "CL"))
      (libsource (lib "") (part "LSA6-03150_1"))
    )
    (comp (ref "L249")
      (value "15nH")
      (footprint "IND-0402HP")
      (description "INDUCTOR;15NH;2%;3.9GHZ SRF;85Q @1.7GHZ;.078 DCR;1.1A;0402")
      (fields (field (name "APPROVED") "CL"))
      (libsource (lib "") (part "LSA6-03150_1"))
    )
    (comp (ref "L250")
      (value "15nH")
      (footprint "IND-0402HP")
      (description "INDUCTOR;15NH;2%;3.9GHZ SRF;85Q @1.7GHZ;.078 DCR;1.1A;0402")
      (fields (field (name "APPROVED") "CL"))
      (libsource (lib "") (part "LSA6-03150_1"))
    )
    (comp (ref "L504")
      (value "390nH")
      (footprint "IND-0603CS")
      (description "INDUCTOR;390NH;5%;.78GHZ SRF;25Q;4.35 DCR;100MA;WIREWOUND;0603")
      (fields (field (name "APPROVED") "CL"))
      (libsource (lib "Giga-tronics") (part "LSA3-04390"))
    )
    (comp (ref "R2")
      (value "11.3")
      (footprint "RES-0603-N")
      (description "11.3 OHM 1% FILM SMT")
      (fields (field (name "APPROVED") "CL"))
      (libsource (lib "Giga-tronics") (part "RK40-00113"))
    )
    (comp (ref "R6")
      (value "49.9")
      (footprint "RES-0402-N")
      (description "49.9 OHMS;.06W;1%;200PPM;FILM;CHIP;0402")
      (fields (field (name "APPROVED") "CL"))
      (libsource (lib "Giga-tronics") (part "RK35-00499"))
    )
    (comp (ref "R7")
      (value "49.9")
      (footprint "RES-0402-N")
      (description "49.9 OHMS;.06W;1%;200PPM;FILM;CHIP;0402")
      (fields (field (name "APPROVED") "CL"))
      (libsource (lib "Giga-tronics") (part "RK35-00499"))
    )
    (comp (ref "R10")
      (value "24.9")
      (footprint "RES-0402-N")
      (description "24.9 OHMS;.06W;1%;200PPM;FILM;CHIP;0402")
      (fields (field (name "APPROVED") "CL"))
      (libsource (lib "Giga-tronics") (part "RK35-00249"))
    )
    (comp (ref "R11")
      (value "0")
      (footprint "RES-0603-N")
      (description "JUMPER;.05 OHMS MAX;1A MAX;0603")
      (fields (field (name "APPROVED") "CL"))
      (libsource (lib "Giga-tronics") (part "RK40-00000"))
    )
    (comp (ref "R14")
      (value "0")
      (footprint "RES-0603-N")
      (description "JUMPER;.05 OHMS MAX;1A MAX;0603")
      (fields (field (name "APPROVED") "CL"))
      (libsource (lib "Giga-tronics") (part "RK40-00000"))
    )
    (comp (ref "R53")
      (value "0")
      (footprint "RES-0603-N")
      (description "JUMPER;.05 OHMS MAX;1A MAX;0603")
      (fields (field (name "APPROVED") "CL"))
      (libsource (lib "Giga-tronics") (part "RK40-00000"))
    )
    (comp (ref "R54")
      (value "0")
      (footprint "RES-0603-N")
      (description "JUMPER;.05 OHMS MAX;1A MAX;0603")
      (fields (field (name "APPROVED") "CL"))
      (libsource (lib "Giga-tronics") (part "RK40-00000"))
    )
    (comp (ref "R57")
      (value "0")
      (footprint "RES-0603-N")
      (description "JUMPER;.05 OHMS MAX;1A MAX;0603")
      (fields (field (name "APPROVED") "CL"))
      (libsource (lib "Giga-tronics") (part "RK40-00000"))
    )
    (comp (ref "R58")
      (value "0")
      (footprint "RES-0603-N")
      (description "JUMPER;.05 OHMS MAX;1A MAX;0603")
      (fields (field (name "APPROVED") "CL"))
      (libsource (lib "Giga-tronics") (part "RK40-00000"))
    )
    (comp (ref "R64")
      (value "24.9")
      (footprint "RES-0402-N")
      (description "24.9 OHMS;.06W;1%;200PPM;FILM;CHIP;0402")
      (fields (field (name "APPROVED") "CL"))
      (libsource (lib "Giga-tronics") (part "RK35-00249"))
    )
    (comp (ref "R65")
      (value "20")
      (footprint "RES-0201-N")
      (description "20 OHMS;.05W;1%;200PPM;FILM CHIP;0201")
      (fields (field (name "APPROVED") "CL"))
      (libsource (lib "Giga-tronics") (part "RK30-00200"))
    )
    (comp (ref "R66")
      (value "20")
      (footprint "RES-0201-N")
      (description "20 OHMS;.05W;1%;200PPM;FILM CHIP;0201")
      (fields (field (name "APPROVED") "CL"))
      (libsource (lib "Giga-tronics") (part "RK30-00200"))
    )
    (comp (ref "R69")
      (value "49.9")
      (footprint "RES-0402-N")
      (description "49.9 OHMS;.06W;1%;200PPM;FILM;CHIP;0402")
      (fields (field (name "APPROVED") "CL"))
      (libsource (lib "Giga-tronics") (part "RK35-00499"))
    )
    (comp (ref "R74")
      (value "49.9")
      (footprint "RES-0402-N")
      (description "49.9 OHMS;.06W;1%;200PPM;FILM;CHIP;0402")
      (fields (field (name "APPROVED") "CL"))
      (libsource (lib "Giga-tronics") (part "RK35-00499"))
    )
    (comp (ref "R76")
      (value "24.9")
      (footprint "RES-0402-N")
      (description "24.9 OHMS;.06W;1%;200PPM;FILM;CHIP;0402")
      (fields (field (name "APPROVED") "CL"))
      (libsource (lib "Giga-tronics") (part "RK35-00249"))
    )
    (comp (ref "R77")
      (value "24.9")
      (footprint "RES-0402-N")
      (description "24.9 OHMS;.06W;1%;200PPM;FILM;CHIP;0402")
      (fields (field (name "APPROVED") "CL"))
      (libsource (lib "Giga-tronics") (part "RK35-00249"))
    )
    (comp (ref "R80")
      (value "24.9")
      (footprint "RES-0402-N")
      (description "24.9 OHMS;.06W;1%;200PPM;FILM;CHIP;0402")
      (fields (field (name "APPROVED") "CL"))
      (libsource (lib "Giga-tronics") (part "RK35-00249"))
    )
    (comp (ref "R83")
      (value "24.9")
      (footprint "RES-0402-N")
      (description "24.9 OHMS;.06W;1%;200PPM;FILM;CHIP;0402")
      (fields (field (name "APPROVED") "CL"))
      (libsource (lib "Giga-tronics") (part "RK35-00249"))
    )
    (comp (ref "R87")
      (value "24.9")
      (footprint "RES-0402-N")
      (description "24.9 OHMS;.06W;1%;200PPM;FILM;CHIP;0402")
      (fields (field (name "APPROVED") "CL"))
      (libsource (lib "Giga-tronics") (part "RK35-00249"))
    )
    (comp (ref "R88")
      (value "20")
      (footprint "RES-0201-N")
      (description "20 OHMS;.05W;1%;200PPM;FILM CHIP;0201")
      (fields (field (name "APPROVED") "CL"))
      (libsource (lib "Giga-tronics") (part "RK30-00200"))
    )
    (comp (ref "R91")
      (value "20")
      (footprint "RES-0201-N")
      (description "20 OHMS;.05W;1%;200PPM;FILM CHIP;0201")
      (fields (field (name "APPROVED") "CL"))
      (libsource (lib "Giga-tronics") (part "RK30-00200"))
    )
    (comp (ref "R95")
      (value "24.9")
      (footprint "RES-0402-N")
      (description "24.9 OHMS;.06W;1%;200PPM;FILM;CHIP;0402")
      (fields (field (name "APPROVED") "CL"))
      (libsource (lib "Giga-tronics") (part "RK35-00249"))
    )
    (comp (ref "R96")
      (value "24.9")
      (footprint "RES-0402-N")
      (description "24.9 OHMS;.06W;1%;200PPM;FILM;CHIP;0402")
      (fields (field (name "APPROVED") "CL"))
      (libsource (lib "Giga-tronics") (part "RK35-00249"))
    )
    (comp (ref "R97")
      (value "24.9")
      (footprint "RES-0402-N")
      (description "24.9 OHMS;.06W;1%;200PPM;FILM;CHIP;0402")
      (fields (field (name "APPROVED") "CL"))
      (libsource (lib "Giga-tronics") (part "RK35-00249"))
    )
    (comp (ref "R99")
      (value "49.9")
      (footprint "RES-0402-N")
      (description "49.9 OHMS;.06W;1%;200PPM;FILM;CHIP;0402")
      (fields (field (name "APPROVED") "CL"))
      (libsource (lib "Giga-tronics") (part "RK35-00499"))
    )
    (comp (ref "R100")
      (value "49.9")
      (footprint "RES-0402-N")
      (description "49.9 OHMS;.06W;1%;200PPM;FILM;CHIP;0402")
      (fields (field (name "APPROVED") "CL"))
      (libsource (lib "Giga-tronics") (part "RK35-00499"))
    )
    (comp (ref "R102")
      (value "24.9")
      (footprint "RES-0402-N")
      (description "24.9 OHMS;.06W;1%;200PPM;FILM;CHIP;0402")
      (fields (field (name "APPROVED") "CL"))
      (libsource (lib "Giga-tronics") (part "RK35-00249"))
    )
    (comp (ref "R112")
      (value "24.9")
      (footprint "RES-0402-N")
      (description "24.9 OHMS;.06W;1%;200PPM;FILM;CHIP;0402")
      (fields (field (name "APPROVED") "CL"))
      (libsource (lib "Giga-tronics") (part "RK35-00249"))
    )
    (comp (ref "R113")
      (value "20")
      (footprint "RES-0201-N")
      (description "20 OHMS;.05W;1%;200PPM;FILM CHIP;0201")
      (fields (field (name "APPROVED") "CL"))
      (libsource (lib "Giga-tronics") (part "RK30-00200"))
    )
    (comp (ref "R114")
      (value "20")
      (footprint "RES-0201-N")
      (description "20 OHMS;.05W;1%;200PPM;FILM CHIP;0201")
      (fields (field (name "APPROVED") "CL"))
      (libsource (lib "Giga-tronics") (part "RK30-00200"))
    )
    (comp (ref "R115")
      (value "24.9")
      (footprint "RES-0402-N")
      (description "24.9 OHMS;.06W;1%;200PPM;FILM;CHIP;0402")
      (fields (field (name "APPROVED") "CL"))
      (libsource (lib "Giga-tronics") (part "RK35-00249"))
    )
    (comp (ref "R118")
      (value "49.9")
      (footprint "RES-0402-N")
      (description "49.9 OHMS;.06W;1%;200PPM;FILM;CHIP;0402")
      (fields (field (name "APPROVED") "CL"))
      (libsource (lib "Giga-tronics") (part "RK35-00499"))
    )
    (comp (ref "R275")
      (value "49.9")
      (footprint "RES-0402-N")
      (description "49.9 OHMS;.06W;1%;200PPM;FILM;CHIP;0402")
      (fields (field (name "APPROVED") "CL"))
      (libsource (lib "Giga-tronics") (part "RK35-00499"))
    )
    (comp (ref "R291")
      (value "24.9")
      (footprint "RES-0402-N")
      (description "24.9 OHMS;.06W;1%;200PPM;FILM;CHIP;0402")
      (fields (field (name "APPROVED") "CL"))
      (libsource (lib "Giga-tronics") (part "RK35-00249"))
    )
    (comp (ref "R292")
      (value "24.9")
      (footprint "RES-0402-N")
      (description "24.9 OHMS;.06W;1%;200PPM;FILM;CHIP;0402")
      (fields (field (name "APPROVED") "CL"))
      (libsource (lib "Giga-tronics") (part "RK35-00249"))
    )
    (comp (ref "R293")
      (value "24.9")
      (footprint "RES-0402-N")
      (description "24.9 OHMS;.06W;1%;200PPM;FILM;CHIP;0402")
      (fields (field (name "APPROVED") "CL"))
      (libsource (lib "Giga-tronics") (part "RK35-00249"))
    )
    (comp (ref "R294")
      (value "24.9")
      (footprint "RES-0402-N")
      (description "24.9 OHMS;.06W;1%;200PPM;FILM;CHIP;0402")
      (fields (field (name "APPROVED") "CL"))
      (libsource (lib "Giga-tronics") (part "RK35-00249"))
    )
    (comp (ref "R295")
      (value "20")
      (footprint "RES-0201-N")
      (description "20 OHMS;.05W;1%;200PPM;FILM CHIP;0201")
      (fields (field (name "APPROVED") "CL"))
      (libsource (lib "Giga-tronics") (part "RK30-00200"))
    )
    (comp (ref "R296")
      (value "20")
      (footprint "RES-0201-N")
      (description "20 OHMS;.05W;1%;200PPM;FILM CHIP;0201")
      (fields (field (name "APPROVED") "CL"))
      (libsource (lib "Giga-tronics") (part "RK30-00200"))
    )
    (comp (ref "R297")
      (value "24.9")
      (footprint "RES-0402-N")
      (description "24.9 OHMS;.06W;1%;200PPM;FILM;CHIP;0402")
      (fields (field (name "APPROVED") "CL"))
      (libsource (lib "Giga-tronics") (part "RK35-00249"))
    )
    (comp (ref "R298")
      (value "49.9")
      (footprint "RES-0402-N")
      (description "49.9 OHMS;.06W;1%;200PPM;FILM;CHIP;0402")
      (fields (field (name "APPROVED") "CL"))
      (libsource (lib "Giga-tronics") (part "RK35-00499"))
    )
    (comp (ref "R299")
      (value "49.9")
      (footprint "RES-0402-N")
      (description "49.9 OHMS;.06W;1%;200PPM;FILM;CHIP;0402")
      (fields (field (name "APPROVED") "CL"))
      (libsource (lib "Giga-tronics") (part "RK35-00499"))
    )
    (comp (ref "R300")
      (value "24.9")
      (footprint "RES-0402-N")
      (description "24.9 OHMS;.06W;1%;200PPM;FILM;CHIP;0402")
      (fields (field (name "APPROVED") "CL"))
      (libsource (lib "Giga-tronics") (part "RK35-00249"))
    )
    (comp (ref "R301")
      (value "24.9")
      (footprint "RES-0402-N")
      (description "24.9 OHMS;.06W;1%;200PPM;FILM;CHIP;0402")
      (fields (field (name "APPROVED") "CL"))
      (libsource (lib "Giga-tronics") (part "RK35-00249"))
    )
    (comp (ref "R302")
      (value "24.9")
      (footprint "RES-0402-N")
      (description "24.9 OHMS;.06W;1%;200PPM;FILM;CHIP;0402")
      (fields (field (name "APPROVED") "CL"))
      (libsource (lib "Giga-tronics") (part "RK35-00249"))
    )
    (comp (ref "R303")
      (value "24.9")
      (footprint "RES-0402-N")
      (description "24.9 OHMS;.06W;1%;200PPM;FILM;CHIP;0402")
      (fields (field (name "APPROVED") "CL"))
      (libsource (lib "Giga-tronics") (part "RK35-00249"))
    )
    (comp (ref "R304")
      (value "20")
      (footprint "RES-0201-N")
      (description "20 OHMS;.05W;1%;200PPM;FILM CHIP;0201")
      (fields (field (name "APPROVED") "CL"))
      (libsource (lib "Giga-tronics") (part "RK30-00200"))
    )
    (comp (ref "R305")
      (value "20")
      (footprint "RES-0201-N")
      (description "20 OHMS;.05W;1%;200PPM;FILM CHIP;0201")
      (fields (field (name "APPROVED") "CL"))
      (libsource (lib "Giga-tronics") (part "RK30-00200"))
    )
    (comp (ref "R306")
      (value "49.9")
      (footprint "RES-0402-N")
      (description "49.9 OHMS;.06W;1%;200PPM;FILM;CHIP;0402")
      (fields (field (name "APPROVED") "CL"))
      (libsource (lib "Giga-tronics") (part "RK35-00499"))
    )
    (comp (ref "R307")
      (value "49.9")
      (footprint "RES-0402-N")
      (description "49.9 OHMS;.06W;1%;200PPM;FILM;CHIP;0402")
      (fields (field (name "APPROVED") "CL"))
      (libsource (lib "Giga-tronics") (part "RK35-00499"))
    )
    (comp (ref "R308")
      (value "24.9")
      (footprint "RES-0402-N")
      (description "24.9 OHMS;.06W;1%;200PPM;FILM;CHIP;0402")
      (fields (field (name "APPROVED") "CL"))
      (libsource (lib "Giga-tronics") (part "RK35-00249"))
    )
    (comp (ref "R309")
      (value "24.9")
      (footprint "RES-0402-N")
      (description "24.9 OHMS;.06W;1%;200PPM;FILM;CHIP;0402")
      (fields (field (name "APPROVED") "CL"))
      (libsource (lib "Giga-tronics") (part "RK35-00249"))
    )
    (comp (ref "R310")
      (value "20")
      (footprint "RES-0201-N")
      (description "20 OHMS;.05W;1%;200PPM;FILM CHIP;0201")
      (fields (field (name "APPROVED") "CL"))
      (libsource (lib "Giga-tronics") (part "RK30-00200"))
    )
    (comp (ref "R311")
      (value "20")
      (footprint "RES-0201-N")
      (description "20 OHMS;.05W;1%;200PPM;FILM CHIP;0201")
      (fields (field (name "APPROVED") "CL"))
      (libsource (lib "Giga-tronics") (part "RK30-00200"))
    )
    (comp (ref "R316")
      (value "11.3")
      (footprint "RES-0603-N")
      (description "11.3 OHM 1% FILM SMT")
      (fields (field (name "APPROVED") "CL"))
      (libsource (lib "Giga-tronics") (part "RK40-00113"))
    )
    (comp (ref "R671")
      (value "39.2")
      (footprint "RES-2010-N")
      (description "39.2 OHM;.75W;1%;100PPM;FILM CHIP;2010")
      (fields (field (name "APPROVED") "CL"))
      (libsource (lib "Giga-tronics") (part "RK65-00392"))
    )
    (comp (ref "R672")
      (value "107")
      (footprint "RES-2010-N")
      (description "107 OHMS;0.75W;1%;100PPM;THICK FILM;CHIP;2010;RoHS")
      (fields (field (name "APPROVED") "CL"))
      (libsource (lib "Giga-tronics") (part "RK65-01107"))
    )
    (comp (ref "R781")
      (value "49.9")
      (footprint "RES-2010-N")
      (description "49.9 OHMS;.5W;1%;100PPM;THICK FILM;CHIP;2010;RoHS")
      (fields (field (name "APPROVED") "CL"))
      (libsource (lib "Giga-tronics") (part "RK65-00499"))
    )
    (comp (ref "R782")
      (value "49.9")
      (footprint "RES-2010-N")
      (description "49.9 OHMS;.5W;1%;100PPM;THICK FILM;CHIP;2010;RoHS")
      (fields (field (name "APPROVED") "CL"))
      (libsource (lib "Giga-tronics") (part "RK65-00499"))
    )
    (comp (ref "U4")
      (value "MMIC SPDT;NON-REFLECTIVE;SWITCH;DC -12 GHz;RoHS")
      (footprint "QFN-24_HITTITE")
      (fields (field (name "M_PN") "HMC232LP4E") (field (name "APPROVED") "CL"))
      (libsource (lib "Giga-tronics") (part "MRSS-12012"))
    )
    (comp (ref "U7")
      (value "MMIC SPDT;NON-REFLECTIVE;SWITCH;DC -12 GHz;RoHS")
      (footprint "QFN-24_HITTITE")
      (fields (field (name "M_PN") "HMC232LP4E") (field (name "APPROVED") "CL"))
      (libsource (lib "Giga-tronics") (part "MRSS-12012"))
    )
    (comp (ref "U8")
      (value "MMIC SPDT;NON-REFLECTIVE;SWITCH;DC -12 GHz;RoHS")
      (footprint "QFN-24_HITTITE")
      (fields (field (name "M_PN") "HMC232LP4E") (field (name "APPROVED") "CL"))
      (libsource (lib "Giga-tronics") (part "MRSS-12012"))
    )
    (comp (ref "U9")
      (value "MMIC SPDT;NON-REFLECTIVE;SWITCH;DC -12 GHz;RoHS")
      (footprint "QFN-24_HITTITE")
      (fields (field (name "M_PN") "HMC232LP4E") (field (name "APPROVED") "CL"))
      (libsource (lib "Giga-tronics") (part "MRSS-12012"))
    )
    (comp (ref "U10")
      (value "MMIC SPDT;NON-REFLECTIVE;SWITCH;DC -12 GHz;RoHS")
      (footprint "QFN-24_HITTITE")
      (fields (field (name "M_PN") "HMC232LP4E") (field (name "APPROVED") "CL"))
      (libsource (lib "Giga-tronics") (part "MRSS-12012"))
    )
    (comp (ref "U13")
      (value "MMIC SPDT;NON-REFLECTIVE;SWITCH;DC -12 GHz;RoHS")
      (footprint "QFN-24_HITTITE")
      (fields (field (name "M_PN") "HMC232LP4E") (field (name "APPROVED") "CL"))
      (libsource (lib "Giga-tronics") (part "MRSS-12012"))
    )
    (comp (ref "U15")
      (value "SWITCH;SP6T;DC-4GHZ;25DB ISO;20NS;27DBM P1;PQFN-36")
      (footprint "QFN36_MACOM")
      (fields (field (name "M_PN") "MASWCC0006") (field (name "APPROVED") "CL"))
      (libsource (lib "Giga-tronics") (part "MRSS-16004"))
    )
    (comp (ref "U17")
      (value "SWITCH;SP6T;DC-4GHZ;25DB ISO;20NS;27DBM P1;PQFN-36")
      (footprint "QFN36_MACOM")
      (fields (field (name "M_PN") "MASWCC0006") (field (name "APPROVED") "CL"))
      (libsource (lib "") (part "MRSS-16004_1"))
    )
    (comp (ref "U18")
      (value "MMIC SPDT;NON-REFLECTIVE;SWITCH;DC -12 GHz;RoHS")
      (footprint "QFN-24_HITTITE")
      (fields (field (name "M_PN") "HMC232LP4E") (field (name "APPROVED") "CL"))
      (libsource (lib "Giga-tronics") (part "MRSS-12012"))
    )
    (comp (ref "U20")
      (value "MMIC SPDT;NON-REFLECTIVE;SWITCH;DC -12 GHz;RoHS")
      (footprint "QFN-24_HITTITE")
      (fields (field (name "M_PN") "HMC232LP4E") (field (name "APPROVED") "CL"))
      (libsource (lib "Giga-tronics") (part "MRSS-12012"))
    )
    (comp (ref "U22")
      (value "MMIC SPDT;NON-REFLECTIVE;SWITCH;DC -12 GHz;RoHS")
      (footprint "QFN-24_HITTITE")
      (fields (field (name "M_PN") "HMC232LP4E") (field (name "APPROVED") "CL"))
      (libsource (lib "Giga-tronics") (part "MRSS-12012"))
    )
    (comp (ref "U23")
      (value "MMIC SPDT;NON-REFLECTIVE;SWITCH;DC -12 GHz;RoHS")
      (footprint "QFN-24_HITTITE")
      (fields (field (name "M_PN") "HMC232LP4E") (field (name "APPROVED") "CL"))
      (libsource (lib "Giga-tronics") (part "MRSS-12012"))
    )
    (comp (ref "U25")
      (value "MMIC SPDT;NON-REFLECTIVE;SWITCH;DC -12 GHz;RoHS")
      (footprint "QFN-24_HITTITE")
      (fields (field (name "M_PN") "HMC232LP4E") (field (name "APPROVED") "CL"))
      (libsource (lib "Giga-tronics") (part "MRSS-12012"))
    )
    (comp (ref "U31")
      (value "AMP;0-6GHZ;20DB;+20DBM;5V;100MA;SOT-89")
      (footprint "SOT-89")
      (fields (field (name "G_PN") "MA20-00006") (field (name "APPROVED") "CL"))
      (libsource (lib "Giga-tronics") (part "MA20-00006"))
    )
    (comp (ref "U33")
      (value "AMP;0-6GHZ;20DB;+20DBM;5V;100MA;SOT-89")
      (footprint "SOT-89")
      (fields (field (name "G_PN") "MA20-00006") (field (name "APPROVED") "CL"))
      (libsource (lib "Giga-tronics") (part "MA20-00006"))
    )
    (comp (ref "U35")
      (value "MMIC SPDT;NON-REFLECTIVE;SWITCH;DC -12 GHz;RoHS")
      (footprint "QFN-24_HITTITE")
      (fields (field (name "M_PN") "HMC232LP4E") (field (name "APPROVED") "CL"))
      (libsource (lib "Giga-tronics") (part "MRSS-12012"))
    )
    (comp (ref "U82")
      (value "MIXER;1.5-3.8GHZ;+2DBM;0-1GHZ IF;QFN-24")
      (footprint "QFN-24_LT")
      (fields (field (name "M_PN") "LT5579IUH#PBF") (field (name "APPROVED") "CL"))
      (libsource (lib "Giga-tronics") (part "MMDC-00204"))
    )
    (comp (ref "U169")
      (value "AMP;50-1000MHZ;12DB;+18DBM;5.5V;60MA;4.4DB NF;RRR137 PKG")
      (footprint "RRR137")
      (fields (field (name "G_PN") "MA12-10001") (field (name "APPROVED") "CL"))
      (libsource (lib "Giga-tronics") (part "MA12-10001"))
    )
    (comp (ref "X5")
      (value "XFORMER;1:4Z CT;2-800MHZ; .25W;240MA;.15\"x.15\"")
      (footprint "SM-22_Macomtech")
      (fields (field (name "G_PN") "LTR4-S0104") (field (name "APPROVED") "CL"))
      (libsource (lib "Giga-tronics") (part "LTR4-S0104"))
    )
  )
  (nets
    (net (code "1") (name "+3.3V_ST") (class "Default")
      (node (ref "C891") (pin "1") (pintype "passive"))
      (node (ref "C892") (pin "2") (pintype "passive"))
      (node (ref "FL22") (pin "3") (pinfunction "OUT_3") (pintype "passive"))
    )
    (net (code "2") (name "+5V_ST") (class "Default")
      (node (ref "C190") (pin "1") (pintype "passive"))
      (node (ref "C196") (pin "2") (pintype "passive"))
      (node (ref "C365") (pin "1") (pintype "passive"))
      (node (ref "C823") (pin "1") (pintype "passive"))
      (node (ref "FT18") (pin "1") (pinfunction "1_1") (pintype "passive"))
      (node (ref "L19") (pin "1") (pinfunction "1_1") (pintype "passive"))
      (node (ref "L77") (pin "2") (pinfunction "2_2") (pintype "passive"))
    )
    (net (code "3") (name "+8V_ST") (class "Default")
      (node (ref "C361") (pin "1") (pintype "passive"))
      (node (ref "C727") (pin "1") (pintype "passive"))
      (node (ref "C961") (pin "1") (pintype "passive"))
      (node (ref "C962") (pin "1") (pintype "passive"))
      (node (ref "FT33") (pin "1") (pinfunction "1_1") (pintype "passive"))
      (node (ref "R671") (pin "2") (pintype "passive"))
      (node (ref "R672") (pin "2") (pintype "passive"))
    )
    (net (code "4") (name "+12V_b") (class "Default")
      (node (ref "C1224") (pin "1") (pintype "passive"))
      (node (ref "C1226") (pin "1") (pintype "passive"))
      (node (ref "R781") (pin "1") (pintype "passive"))
    )
    (net (code "5") (name "-5V_ST") (class "Default")
      (node (ref "C189") (pin "1") (pintype "passive"))
      (node (ref "C195") (pin "2") (pintype "passive"))
      (node (ref "C367") (pin "1") (pintype "passive"))
      (node (ref "C825") (pin "1") (pintype "passive"))
      (node (ref "FT7") (pin "1") (pinfunction "1_1") (pintype "passive"))
      (node (ref "L20") (pin "1") (pinfunction "1_1") (pintype "passive"))
      (node (ref "L76") (pin "2") (pinfunction "2_2") (pintype "passive"))
    )
    (net (code "6") (name "/BANK_1_NEG") (class "Default")
      (node (ref "C356") (pin "1") (pintype "passive"))
      (node (ref "C399") (pin "1") (pintype "passive"))
      (node (ref "R112") (pin "1") (pintype "passive"))
      (node (ref "R114") (pin "1") (pintype "passive"))
    )
    (net (code "7") (name "/BANK_1_POS") (class "Default")
      (node (ref "C184") (pin "1") (pintype "passive"))
      (node (ref "C855") (pin "1") (pintype "passive"))
      (node (ref "L235") (pin "1") (pinfunction "1_1") (pintype "passive"))
      (node (ref "L69") (pin "1") (pinfunction "1_1") (pintype "passive"))
    )
    (net (code "8") (name "/BANK_2_NEG") (class "Default")
      (node (ref "C841") (pin "1") (pintype "passive"))
      (node (ref "C843") (pin "1") (pintype "passive"))
      (node (ref "R294") (pin "1") (pintype "passive"))
      (node (ref "R296") (pin "1") (pintype "passive"))
    )
    (net (code "9") (name "/BANK_2_POS") (class "Default")
      (node (ref "C175") (pin "1") (pintype "passive"))
      (node (ref "C826") (pin "1") (pintype "passive"))
      (node (ref "L152") (pin "1") (pinfunction "1_1") (pintype "passive"))
      (node (ref "L68") (pin "1") (pinfunction "1_1") (pintype "passive"))
    )
    (net (code "10") (name "/BANK_3_NEG") (class "Default")
      (node (ref "C181") (pin "1") (pintype "passive"))
      (node (ref "C183") (pin "1") (pintype "passive"))
      (node (ref "R87") (pin "1") (pintype "passive"))
      (node (ref "R91") (pin "1") (pintype "passive"))
    )
    (net (code "11") (name "/BANK_3_POS") (class "Default")
      (node (ref "C185") (pin "1") (pintype "passive"))
      (node (ref "L71") (pin "1") (pinfunction "1_1") (pintype "passive"))
      (node (ref "R57") (pin "1") (pintype "passive"))
    )
    (net (code "12") (name "/BANK_4_NEG") (class "Default")
      (node (ref "C862") (pin "1") (pintype "passive"))
      (node (ref "C864") (pin "1") (pintype "passive"))
      (node (ref "R303") (pin "1") (pintype "passive"))
      (node (ref "R305") (pin "1") (pintype "passive"))
    )
    (net (code "13") (name "/BANK_4_POS") (class "Default")
      (node (ref "C118") (pin "1") (pintype "passive"))
      (node (ref "L67") (pin "1") (pinfunction "1_1") (pintype "passive"))
      (node (ref "R54") (pin "1") (pintype "passive"))
    )
    (net (code "14") (name "/BANK_5_NEG") (class "Default")
      (node (ref "C107") (pin "1") (pintype "passive"))
      (node (ref "C109") (pin "1") (pintype "passive"))
      (node (ref "R64") (pin "1") (pintype "passive"))
      (node (ref "R66") (pin "1") (pintype "passive"))
    )
    (net (code "15") (name "/BANK_5_POS") (class "Default")
      (node (ref "C186") (pin "1") (pintype "passive"))
      (node (ref "L73") (pin "1") (pinfunction "1_1") (pintype "passive"))
      (node (ref "R58") (pin "1") (pintype "passive"))
    )
    (net (code "16") (name "/BANK_6_NEG") (class "Default")
      (node (ref "C877") (pin "1") (pintype "passive"))
      (node (ref "C879") (pin "1") (pintype "passive"))
      (node (ref "R309") (pin "1") (pintype "passive"))
      (node (ref "R311") (pin "1") (pintype "passive"))
    )
    (net (code "17") (name "/BANK_6_POS") (class "Default")
      (node (ref "C117") (pin "1") (pintype "passive"))
      (node (ref "L66") (pin "1") (pinfunction "1_1") (pintype "passive"))
      (node (ref "R53") (pin "1") (pintype "passive"))
    )
    (net (code "18") (name "/STALO_LO") (class "Default")
      (node (ref "AT62") (pin "1") (pinfunction "IN/OUT_1") (pintype "passive"))
    )
    (net (code "19") (name "/STALO_p2-p3") (class "Default")
      (node (ref "FL48") (pin "3") (pinfunction "GND_3") (pintype "passive"))
    )
    (net (code "20") (name "/~{BANK_1_NEG}") (class "Default")
      (node (ref "C233") (pin "1") (pintype "passive"))
      (node (ref "C357") (pin "1") (pintype "passive"))
      (node (ref "R102") (pin "1") (pintype "passive"))
      (node (ref "R113") (pin "1") (pintype "passive"))
    )
    (net (code "21") (name "/~{BANK_2_NEG}") (class "Default")
      (node (ref "C840") (pin "1") (pintype "passive"))
      (node (ref "C842") (pin "1") (pintype "passive"))
      (node (ref "R293") (pin "1") (pintype "passive"))
      (node (ref "R295") (pin "1") (pintype "passive"))
    )
    (net (code "22") (name "/~{BANK_3_NEG}") (class "Default")
      (node (ref "C180") (pin "1") (pintype "passive"))
      (node (ref "C182") (pin "1") (pintype "passive"))
      (node (ref "R83") (pin "1") (pintype "passive"))
      (node (ref "R88") (pin "1") (pintype "passive"))
    )
    (net (code "23") (name "/~{BANK_4_NEG}") (class "Default")
      (node (ref "C861") (pin "1") (pintype "passive"))
      (node (ref "C863") (pin "1") (pintype "passive"))
      (node (ref "R302") (pin "1") (pintype "passive"))
      (node (ref "R304") (pin "1") (pintype "passive"))
    )
    (net (code "24") (name "/~{BANK_5_NEG}") (class "Default")
      (node (ref "C106") (pin "1") (pintype "passive"))
      (node (ref "C108") (pin "1") (pintype "passive"))
      (node (ref "R10") (pin "1") (pintype "passive"))
      (node (ref "R65") (pin "1") (pintype "passive"))
    )
    (net (code "25") (name "/~{BANK_6_NEG}") (class "Default")
      (node (ref "C876") (pin "1") (pintype "passive"))
      (node (ref "C878") (pin "1") (pintype "passive"))
      (node (ref "R308") (pin "1") (pintype "passive"))
      (node (ref "R310") (pin "1") (pintype "passive"))
    )
    (net (code "26") (name "GND") (class "Default")
      (node (ref "AT11") (pin "2") (pinfunction "GND_2") (pintype "power_in"))
      (node (ref "AT13") (pin "2") (pinfunction "GND_2") (pintype "power_in"))
      (node (ref "AT15") (pin "2") (pinfunction "GND_2") (pintype "power_in"))
      (node (ref "AT2") (pin "2") (pinfunction "GND_2") (pintype "power_in"))
      (node (ref "AT4") (pin "2") (pinfunction "GND_2") (pintype "power_in"))
      (node (ref "AT5") (pin "2") (pinfunction "GND_2") (pintype "power_in"))
      (node (ref "AT53") (pin "2") (pinfunction "GND_2") (pintype "power_in"))
      (node (ref "AT54") (pin "2") (pinfunction "GND_2") (pintype "power_in"))
      (node (ref "AT55") (pin "2") (pinfunction "GND_2") (pintype "power_in"))
      (node (ref "AT57") (pin "2") (pinfunction "GND_2") (pintype "power_in"))
      (node (ref "AT59") (pin "2") (pinfunction "GND_2") (pintype "power_in"))
      (node (ref "AT61") (pin "2") (pinfunction "GND_2") (pintype "power_in"))
      (node (ref "AT62") (pin "2") (pinfunction "GND_2") (pintype "power_in"))
      (node (ref "AT7") (pin "2") (pinfunction "GND_2") (pintype "power_in"))
      (node (ref "AT8") (pin "2") (pinfunction "GND_2") (pintype "power_in"))
      (node (ref "AT9") (pin "2") (pinfunction "GND_2") (pintype "power_in"))
      (node (ref "C102") (pin "2") (pintype "passive"))
      (node (ref "C103") (pin "2") (pintype "passive"))
      (node (ref "C104") (pin "2") (pintype "passive"))
      (node (ref "C105") (pin "2") (pintype "passive"))
      (node (ref "C106") (pin "2") (pintype "passive"))
      (node (ref "C107") (pin "2") (pintype "passive"))
      (node (ref "C108") (pin "2") (pintype "passive"))
      (node (ref "C109") (pin "2") (pintype "passive"))
      (node (ref "C115") (pin "2") (pintype "passive"))
      (node (ref "C117") (pin "2") (pintype "passive"))
      (node (ref "C118") (pin "2") (pintype "passive"))
      (node (ref "C1224") (pin "2") (pintype "passive"))
      (node (ref "C1225") (pin "2") (pintype "passive"))
      (node (ref "C1226") (pin "2") (pintype "passive"))
      (node (ref "C1227") (pin "2") (pintype "passive"))
      (node (ref "C148") (pin "2") (pintype "passive"))
      (node (ref "C149") (pin "2") (pintype "passive"))
      (node (ref "C150") (pin "2") (pintype "passive"))
      (node (ref "C151") (pin "2") (pintype "passive"))
      (node (ref "C152") (pin "2") (pintype "passive"))
      (node (ref "C175") (pin "2") (pintype "passive"))
      (node (ref "C176") (pin "2") (pintype "passive"))
      (node (ref "C177") (pin "2") (pintype "passive"))
      (node (ref "C178") (pin "2") (pintype "passive"))
      (node (ref "C179") (pin "2") (pintype "passive"))
      (node (ref "C180") (pin "2") (pintype "passive"))
      (node (ref "C181") (pin "2") (pintype "passive"))
      (node (ref "C182") (pin "2") (pintype "passive"))
      (node (ref "C183") (pin "2") (pintype "passive"))
      (node (ref "C184") (pin "2") (pintype "passive"))
      (node (ref "C185") (pin "2") (pintype "passive"))
      (node (ref "C186") (pin "2") (pintype "passive"))
      (node (ref "C189") (pin "2") (pintype "passive"))
      (node (ref "C190") (pin "2") (pintype "passive"))
      (node (ref "C191") (pin "1") (pintype "passive"))
      (node (ref "C192") (pin "1") (pintype "passive"))
      (node (ref "C193") (pin "1") (pintype "passive"))
      (node (ref "C195") (pin "1") (pintype "passive"))
      (node (ref "C196") (pin "1") (pintype "passive"))
      (node (ref "C197") (pin "1") (pintype "passive"))
      (node (ref "C198") (pin "1") (pintype "passive"))
      (node (ref "C199") (pin "1") (pintype "passive"))
      (node (ref "C232") (pin "1") (pintype "passive"))
      (node (ref "C233") (pin "2") (pintype "passive"))
      (node (ref "C234") (pin "2") (pintype "passive"))
      (node (ref "C241") (pin "2") (pintype "passive"))
      (node (ref "C253") (pin "2") (pintype "passive"))
      (node (ref "C254") (pin "2") (pintype "passive"))
      (node (ref "C255") (pin "2") (pintype "passive"))
      (node (ref "C256") (pin "2") (pintype "passive"))
      (node (ref "C259") (pin "2") (pintype "passive"))
      (node (ref "C351") (pin "2") (pintype "passive"))
      (node (ref "C352") (pin "2") (pintype "passive"))
      (node (ref "C353") (pin "2") (pintype "passive"))
      (node (ref "C354") (pin "2") (pintype "passive"))
      (node (ref "C355") (pin "2") (pintype "passive"))
      (node (ref "C356") (pin "2") (pintype "passive"))
      (node (ref "C357") (pin "2") (pintype "passive"))
      (node (ref "C361") (pin "2") (pintype "passive"))
      (node (ref "C365") (pin "2") (pintype "passive"))
      (node (ref "C366") (pin "2") (pintype "passive"))
      (node (ref "C367") (pin "2") (pintype "passive"))
      (node (ref "C399") (pin "2") (pintype "passive"))
      (node (ref "C400") (pin "1") (pintype "passive"))
      (node (ref "C727") (pin "2") (pintype "passive"))
      (node (ref "C730") (pin "1") (pintype "passive"))
      (node (ref "C823") (pin "2") (pintype "passive"))
      (node (ref "C825") (pin "2") (pintype "passive"))
      (node (ref "C826") (pin "2") (pintype "passive"))
      (node (ref "C827") (pin "1") (pintype "passive"))
      (node (ref "C832") (pin "2") (pintype "passive"))
      (node (ref "C833") (pin "1") (pintype "passive"))
      (node (ref "C834") (pin "2") (pintype "passive"))
      (node (ref "C835") (pin "2") (pintype "passive"))
      (node (ref "C836") (pin "2") (pintype "passive"))
      (node (ref "C837") (pin "2") (pintype "passive"))
      (node (ref "C838") (pin "2") (pintype "passive"))
      (node (ref "C839") (pin "1") (pintype "passive"))
      (node (ref "C840") (pin "2") (pintype "passive"))
      (node (ref "C841") (pin "2") (pintype "passive"))
      (node (ref "C842") (pin "2") (pintype "passive"))
      (node (ref "C843") (pin "2") (pintype "passive"))
      (node (ref "C846") (pin "2") (pintype "passive"))
      (node (ref "C847") (pin "1") (pintype "passive"))
      (node (ref "C849") (pin "2") (pintype "passive"))
      (node (ref "C854") (pin "1") (pintype "passive"))
      (node (ref "C855") (pin "2") (pintype "passive"))
      (node (ref "C856") (pin "1") (pintype "passive"))
      (node (ref "C857") (pin "2") (pintype "passive"))
      (node (ref "C858") (pin "2") (pintype "passive"))
      (node (ref "C859") (pin "2") (pintype "passive"))
      (node (ref "C860") (pin "2") (pintype "passive"))
      (node (ref "C861") (pin "2") (pintype "passive"))
      (node (ref "C862") (pin "2") (pintype "passive"))
      (node (ref "C863") (pin "2") (pintype "passive"))
      (node (ref "C864") (pin "2") (pintype "passive"))
      (node (ref "C872") (pin "2") (pintype "passive"))
      (node (ref "C873") (pin "2") (pintype "passive"))
      (node (ref "C874") (pin "2") (pintype "passive"))
      (node (ref "C875") (pin "2") (pintype "passive"))
      (node (ref "C876") (pin "2") (pintype "passive"))
      (node (ref "C877") (pin "2") (pintype "passive"))
      (node (ref "C878") (pin "2") (pintype "passive"))
      (node (ref "C879") (pin "2") (pintype "passive"))
      (node (ref "C884") (pin "1") (pintype "passive"))
      (node (ref "C886") (pin "2") (pintype "passive"))
      (node (ref "C887") (pin "1") (pintype "passive"))
      (node (ref "C888") (pin "1") (pintype "passive"))
      (node (ref "C889") (pin "1") (pintype "passive"))
      (node (ref "C890") (pin "1") (pintype "passive"))
      (node (ref "C891") (pin "2") (pintype "passive"))
      (node (ref "C892") (pin "1") (pintype "passive"))
      (node (ref "C893") (pin "2") (pintype "passive"))
      (node (ref "C952") (pin "1") (pintype "passive"))
      (node (ref "C953") (pin "1") (pintype "passive"))
      (node (ref "C954") (pin "2") (pintype "passive"))
      (node (ref "C955") (pin "2") (pintype "passive"))
      (node (ref "C961") (pin "2") (pintype "passive"))
      (node (ref "C962") (pin "2") (pintype "passive"))
      (node (ref "C963") (pin "1") (pintype "passive"))
      (node (ref "C964") (pin "1") (pintype "passive"))
      (node (ref "C965") (pin "1") (pintype "passive"))
      (node (ref "C966") (pin "2") (pintype "passive"))
      (node (ref "C967") (pin "2") (pintype "passive"))
      (node (ref "C969") (pin "2") (pintype "passive"))
      (node (ref "C970") (pin "2") (pintype "passive"))
      (node (ref "FL11") (pin "2") (pinfunction "GND_2") (pintype "passive"))
      (node (ref "FL151") (pin "10") (pinfunction "GND_10") (pintype "passive"))
      (node (ref "FL151") (pin "3") (pinfunction "GND_3") (pintype "passive"))
      (node (ref "FL151") (pin "4") (pinfunction "GND_4") (pintype "passive"))
      (node (ref "FL151") (pin "5") (pinfunction "GND_5") (pintype "passive"))
      (node (ref "FL151") (pin "6") (pinfunction "GND_6") (pintype "passive"))
      (node (ref "FL151") (pin "7") (pinfunction "GND_7") (pintype "passive"))
      (node (ref "FL151") (pin "8") (pinfunction "GND_8") (pintype "passive"))
      (node (ref "FL151") (pin "9") (pinfunction "GND_9") (pintype "passive"))
      (node (ref "FL152") (pin "10") (pinfunction "GND_10") (pintype "passive"))
      (node (ref "FL152") (pin "3") (pinfunction "GND_3") (pintype "passive"))
      (node (ref "FL152") (pin "4") (pinfunction "GND_4") (pintype "passive"))
      (node (ref "FL152") (pin "5") (pinfunction "GND_5") (pintype "passive"))
      (node (ref "FL152") (pin "6") (pinfunction "GND_6") (pintype "passive"))
      (node (ref "FL152") (pin "7") (pinfunction "GND_7") (pintype "passive"))
      (node (ref "FL152") (pin "8") (pinfunction "GND_8") (pintype "passive"))
      (node (ref "FL152") (pin "9") (pinfunction "GND_9") (pintype "passive"))
      (node (ref "FL153") (pin "10") (pinfunction "GND_10") (pintype "passive"))
      (node (ref "FL153") (pin "3") (pinfunction "GND_3") (pintype "passive"))
      (node (ref "FL153") (pin "4") (pinfunction "GND_4") (pintype "passive"))
      (node (ref "FL153") (pin "5") (pinfunction "GND_5") (pintype "passive"))
      (node (ref "FL153") (pin "6") (pinfunction "GND_6") (pintype "passive"))
      (node (ref "FL153") (pin "7") (pinfunction "GND_7") (pintype "passive"))
      (node (ref "FL153") (pin "8") (pinfunction "GND_8") (pintype "passive"))
      (node (ref "FL153") (pin "9") (pinfunction "GND_9") (pintype "passive"))
      (node (ref "FL173") (pin "10") (pinfunction "GND_10") (pintype "passive"))
      (node (ref "FL173") (pin "3") (pinfunction "GND_3") (pintype "passive"))
      (node (ref "FL173") (pin "4") (pinfunction "GND_4") (pintype "passive"))
      (node (ref "FL173") (pin "5") (pinfunction "GND_5") (pintype "passive"))
      (node (ref "FL173") (pin "6") (pinfunction "GND_6") (pintype "passive"))
      (node (ref "FL173") (pin "7") (pinfunction "GND_7") (pintype "passive"))
      (node (ref "FL173") (pin "8") (pinfunction "GND_8") (pintype "passive"))
      (node (ref "FL173") (pin "9") (pinfunction "GND_9") (pintype "passive"))
      (node (ref "FL190") (pin "10") (pinfunction "GND_10") (pintype "passive"))
      (node (ref "FL190") (pin "3") (pinfunction "GND_3") (pintype "passive"))
      (node (ref "FL190") (pin "4") (pinfunction "GND_4") (pintype "passive"))
      (node (ref "FL190") (pin "5") (pinfunction "GND_5") (pintype "passive"))
      (node (ref "FL190") (pin "6") (pinfunction "GND_6") (pintype "passive"))
      (node (ref "FL190") (pin "7") (pinfunction "GND_7") (pintype "passive"))
      (node (ref "FL190") (pin "8") (pinfunction "GND_8") (pintype "passive"))
      (node (ref "FL190") (pin "9") (pinfunction "GND_9") (pintype "passive"))
      (node (ref "FL22") (pin "2") (pinfunction "GND_2") (pintype "passive"))
      (node (ref "FL23") (pin "2") (pinfunction "GND_2") (pintype "passive"))
      (node (ref "FL27") (pin "10") (pinfunction "GND_10") (pintype "passive"))
      (node (ref "FL27") (pin "3") (pinfunction "GND_3") (pintype "passive"))
      (node (ref "FL27") (pin "4") (pinfunction "GND_4") (pintype "passive"))
      (node (ref "FL27") (pin "5") (pinfunction "GND_5") (pintype "passive"))
      (node (ref "FL27") (pin "6") (pinfunction "GND_6") (pintype "passive"))
      (node (ref "FL27") (pin "7") (pinfunction "GND_7") (pintype "passive"))
      (node (ref "FL27") (pin "8") (pinfunction "GND_8") (pintype "passive"))
      (node (ref "FL27") (pin "9") (pinfunction "GND_9") (pintype "passive"))
      (node (ref "FL28") (pin "10") (pinfunction "GND_10") (pintype "passive"))
      (node (ref "FL28") (pin "3") (pinfunction "GND_3") (pintype "passive"))
      (node (ref "FL28") (pin "4") (pinfunction "GND_4") (pintype "passive"))
      (node (ref "FL28") (pin "5") (pinfunction "GND_5") (pintype "passive"))
      (node (ref "FL28") (pin "6") (pinfunction "GND_6") (pintype "passive"))
      (node (ref "FL28") (pin "7") (pinfunction "GND_7") (pintype "passive"))
      (node (ref "FL28") (pin "8") (pinfunction "GND_8") (pintype "passive"))
      (node (ref "FL28") (pin "9") (pinfunction "GND_9") (pintype "passive"))
      (node (ref "FL29") (pin "10") (pinfunction "GND_10") (pintype "passive"))
      (node (ref "FL29") (pin "3") (pinfunction "GND_3") (pintype "passive"))
      (node (ref "FL29") (pin "4") (pinfunction "GND_4") (pintype "passive"))
      (node (ref "FL29") (pin "5") (pinfunction "GND_5") (pintype "passive"))
      (node (ref "FL29") (pin "6") (pinfunction "GND_6") (pintype "passive"))
      (node (ref "FL29") (pin "7") (pinfunction "GND_7") (pintype "passive"))
      (node (ref "FL29") (pin "8") (pinfunction "GND_8") (pintype "passive"))
      (node (ref "FL29") (pin "9") (pinfunction "GND_9") (pintype "passive"))
      (node (ref "FL33") (pin "10") (pinfunction "GND_10") (pintype "passive"))
      (node (ref "FL33") (pin "3") (pinfunction "GND_3") (pintype "passive"))
      (node (ref "FL33") (pin "4") (pinfunction "GND_4") (pintype "passive"))
      (node (ref "FL33") (pin "5") (pinfunction "GND_5") (pintype "passive"))
      (node (ref "FL33") (pin "6") (pinfunction "GND_6") (pintype "passive"))
      (node (ref "FL33") (pin "7") (pinfunction "GND_7") (pintype "passive"))
      (node (ref "FL33") (pin "8") (pinfunction "GND_8") (pintype "passive"))
      (node (ref "FL33") (pin "9") (pinfunction "GND_9") (pintype "passive"))
      (node (ref "FL34") (pin "10") (pinfunction "GND_10") (pintype "passive"))
      (node (ref "FL34") (pin "3") (pinfunction "GND_3") (pintype "passive"))
      (node (ref "FL34") (pin "4") (pinfunction "GND_4") (pintype "passive"))
      (node (ref "FL34") (pin "5") (pinfunction "GND_5") (pintype "passive"))
      (node (ref "FL34") (pin "6") (pinfunction "GND_6") (pintype "passive"))
      (node (ref "FL34") (pin "7") (pinfunction "GND_7") (pintype "passive"))
      (node (ref "FL34") (pin "8") (pinfunction "GND_8") (pintype "passive"))
      (node (ref "FL34") (pin "9") (pinfunction "GND_9") (pintype "passive"))
      (node (ref "FL37") (pin "10") (pinfunction "GND_10") (pintype "passive"))
      (node (ref "FL37") (pin "3") (pinfunction "GND_3") (pintype "passive"))
      (node (ref "FL37") (pin "4") (pinfunction "GND_4") (pintype "passive"))
      (node (ref "FL37") (pin "5") (pinfunction "GND_5") (pintype "passive"))
      (node (ref "FL37") (pin "6") (pinfunction "GND_6") (pintype "passive"))
      (node (ref "FL37") (pin "7") (pinfunction "GND_7") (pintype "passive"))
      (node (ref "FL37") (pin "8") (pinfunction "GND_8") (pintype "passive"))
      (node (ref "FL37") (pin "9") (pinfunction "GND_9") (pintype "passive"))
      (node (ref "FL39") (pin "2") (pinfunction "OUT_2") (pintype "passive"))
      (node (ref "FL39") (pin "4") (pinfunction "GND_4") (pintype "passive"))
      (node (ref "FL43") (pin "10") (pinfunction "GND_10") (pintype "passive"))
      (node (ref "FL43") (pin "3") (pinfunction "GND_3") (pintype "passive"))
      (node (ref "FL43") (pin "4") (pinfunction "GND_4") (pintype "passive"))
      (node (ref "FL43") (pin "5") (pinfunction "GND_5") (pintype "passive"))
      (node (ref "FL43") (pin "6") (pinfunction "GND_6") (pintype "passive"))
      (node (ref "FL43") (pin "7") (pinfunction "GND_7") (pintype "passive"))
      (node (ref "FL43") (pin "8") (pinfunction "GND_8") (pintype "passive"))
      (node (ref "FL43") (pin "9") (pinfunction "GND_9") (pintype "passive"))
      (node (ref "FL45") (pin "2") (pinfunction "GND_2") (pintype "passive"))
      (node (ref "FL47") (pin "2") (pinfunction "GND_2") (pintype "passive"))
      (node (ref "FL48") (pin "2") (pinfunction "OUT_2") (pintype "passive"))
      (node (ref "FL48") (pin "4") (pinfunction "GND_4") (pintype "passive"))
      (node (ref "FL49") (pin "2") (pinfunction "GND_2") (pintype "passive"))
      (node (ref "FL50") (pin "2") (pinfunction "GND_2") (pintype "passive"))
      (node (ref "FL500") (pin "2") (pinfunction "GND_2") (pintype "passive"))
      (node (ref "FL501") (pin "2") (pinfunction "GND_2") (pintype "passive"))
      (node (ref "FL506") (pin "2") (pinfunction "GND_2") (pintype "passive"))
      (node (ref "FL51") (pin "2") (pinfunction "GND_2") (pintype "passive"))
      (node (ref "J2") (pin "2") (pinfunction "GND_2") (pintype "passive"))
      (node (ref "J25") (pin "2") (pinfunction "GND_2") (pintype "passive"))
      (node (ref "L10") (pin "1") (pinfunction "1_1") (pintype "passive"))
      (node (ref "L11") (pin "1") (pinfunction "1_1") (pintype "passive"))
      (node (ref "L153") (pin "1") (pinfunction "1_1") (pintype "passive"))
      (node (ref "L154") (pin "1") (pinfunction "1_1") (pintype "passive"))
      (node (ref "L155") (pin "1") (pinfunction "1_1") (pintype "passive"))
      (node (ref "L157") (pin "1") (pinfunction "1_1") (pintype "passive"))
      (node (ref "L17") (pin "1") (pinfunction "1_1") (pintype "passive"))
      (node (ref "L18") (pin "1") (pinfunction "1_1") (pintype "passive"))
      (node (ref "L231") (pin "1") (pinfunction "1_1") (pintype "passive"))
      (node (ref "L232") (pin "1") (pinfunction "1_1") (pintype "passive"))
      (node (ref "L233") (pin "1") (pinfunction "1_1") (pintype "passive"))
      (node (ref "L234") (pin "1") (pinfunction "1_1") (pintype "passive"))
      (node (ref "L240") (pin "1") (pinfunction "1_1") (pintype "passive"))
      (node (ref "L241") (pin "1") (pinfunction "1_1") (pintype "passive"))
      (node (ref "L242") (pin "1") (pinfunction "1_1") (pintype "passive"))
      (node (ref "L243") (pin "1") (pinfunction "1_1") (pintype "passive"))
      (node (ref "L54") (pin "1") (pinfunction "1_1") (pintype "passive"))
      (node (ref "L55") (pin "1") (pinfunction "1_1") (pintype "passive"))
      (node (ref "L78") (pin "1") (pinfunction "1_1") (pintype "passive"))
      (node (ref "L79") (pin "1") (pinfunction "1_1") (pintype "passive"))
      (node (ref "L8") (pin "1") (pinfunction "1_1") (pintype "passive"))
      (node (ref "L84") (pin "1") (pinfunction "1_1") (pintype "passive"))
      (node (ref "L85") (pin "1") (pinfunction "1_1") (pintype "passive"))
      (node (ref "L9") (pin "1") (pinfunction "1_1") (pintype "passive"))
      (node (ref "R100") (pin "2") (pintype "passive"))
      (node (ref "R118") (pin "2") (pintype "passive"))
      (node (ref "R2") (pin "1") (pintype "passive"))
      (node (ref "R275") (pin "2") (pintype "passive"))
      (node (ref "R298") (pin "2") (pintype "passive"))
      (node (ref "R299") (pin "2") (pintype "passive"))
      (node (ref "R306") (pin "2") (pintype "passive"))
      (node (ref "R307") (pin "2") (pintype "passive"))
      (node (ref "R316") (pin "2") (pintype "passive"))
      (node (ref "R6") (pin "2") (pintype "passive"))
      (node (ref "R69") (pin "2") (pintype "passive"))
      (node (ref "R7") (pin "2") (pintype "passive"))
      (node (ref "R74") (pin "2") (pintype "passive"))
      (node (ref "R99") (pin "2") (pintype "passive"))
      (node (ref "U10") (pin "1") (pinfunction "Vdd_1") (pintype "passive"))
      (node (ref "U10") (pin "10") (pinfunction "G_10") (pintype "passive"))
      (node (ref "U10") (pin "11") (pinfunction "NC_11") (pintype "passive"))
      (node (ref "U10") (pin "12") (pinfunction "RF2_12") (pintype "passive"))
      (node (ref "U10") (pin "13") (pinfunction "NC_13") (pintype "passive"))
      (node (ref "U10") (pin "14") (pinfunction "NC_14") (pintype "passive"))
      (node (ref "U10") (pin "17") (pinfunction "NC_17") (pintype "passive"))
      (node (ref "U10") (pin "18") (pinfunction "NC_18") (pintype "passive"))
      (node (ref "U10") (pin "19") (pinfunction "NC_19") (pintype "passive"))
      (node (ref "U10") (pin "2") (pinfunction "Vctl_2") (pintype "passive"))
      (node (ref "U10") (pin "20") (pinfunction "NC_20") (pintype "passive"))
      (node (ref "U10") (pin "21") (pinfunction "G_21") (pintype "passive"))
      (node (ref "U10") (pin "23") (pinfunction "G_23") (pintype "passive"))
      (node (ref "U10") (pin "24") (pinfunction "NC_24") (pintype "passive"))
      (node (ref "U10") (pin "25") (pinfunction "G_25") (pintype "passive"))
      (node (ref "U10") (pin "3") (pinfunction "G_3") (pintype "passive"))
      (node (ref "U10") (pin "5") (pinfunction "G_5") (pintype "passive"))
      (node (ref "U10") (pin "6") (pinfunction "NC_6") (pintype "passive"))
      (node (ref "U10") (pin "7") (pinfunction "NC_7") (pintype "passive"))
      (node (ref "U10") (pin "8") (pinfunction "G_8") (pintype "passive"))
      (node (ref "U13") (pin "1") (pinfunction "Vdd_1") (pintype "passive"))
      (node (ref "U13") (pin "10") (pinfunction "G_10") (pintype "passive"))
      (node (ref "U13") (pin "11") (pinfunction "NC_11") (pintype "passive"))
      (node (ref "U13") (pin "12") (pinfunction "RF2_12") (pintype "passive"))
      (node (ref "U13") (pin "13") (pinfunction "NC_13") (pintype "passive"))
      (node (ref "U13") (pin "14") (pinfunction "NC_14") (pintype "passive"))
      (node (ref "U13") (pin "17") (pinfunction "NC_17") (pintype "passive"))
      (node (ref "U13") (pin "18") (pinfunction "NC_18") (pintype "passive"))
      (node (ref "U13") (pin "19") (pinfunction "NC_19") (pintype "passive"))
      (node (ref "U13") (pin "2") (pinfunction "Vctl_2") (pintype "passive"))
      (node (ref "U13") (pin "20") (pinfunction "NC_20") (pintype "passive"))
      (node (ref "U13") (pin "21") (pinfunction "G_21") (pintype "passive"))
      (node (ref "U13") (pin "23") (pinfunction "G_23") (pintype "passive"))
      (node (ref "U13") (pin "24") (pinfunction "NC_24") (pintype "passive"))
      (node (ref "U13") (pin "25") (pinfunction "G_25") (pintype "passive"))
      (node (ref "U13") (pin "3") (pinfunction "G_3") (pintype "passive"))
      (node (ref "U13") (pin "5") (pinfunction "G_5") (pintype "passive"))
      (node (ref "U13") (pin "6") (pinfunction "NC_6") (pintype "passive"))
      (node (ref "U13") (pin "7") (pinfunction "NC_7") (pintype "passive"))
      (node (ref "U13") (pin "8") (pinfunction "G_8") (pintype "passive"))
      (node (ref "U15") (pin "11") (pinfunction "GND_11") (pintype "passive"))
      (node (ref "U15") (pin "13") (pinfunction "GND_13") (pintype "passive"))
      (node (ref "U15") (pin "15") (pinfunction "GND_15") (pintype "passive"))
      (node (ref "U15") (pin "17") (pinfunction "GND_17") (pintype "passive"))
      (node (ref "U15") (pin "19") (pinfunction "GND_19") (pintype "passive"))
      (node (ref "U15") (pin "21") (pinfunction "GND_21") (pintype "passive"))
      (node (ref "U15") (pin "23") (pinfunction "GND_23") (pintype "passive"))
      (node (ref "U15") (pin "24") (pinfunction "GND_24") (pintype "passive"))
      (node (ref "U15") (pin "26") (pinfunction "GND_26") (pintype "passive"))
      (node (ref "U15") (pin "28") (pinfunction "GND_28") (pintype "passive"))
      (node (ref "U15") (pin "30") (pinfunction "GND_30") (pintype "passive"))
      (node (ref "U15") (pin "37") (pinfunction "GND_37") (pintype "passive"))
      (node (ref "U169") (pin "2") (pinfunction "GND_2") (pintype "passive"))
      (node (ref "U169") (pin "4") (pinfunction "GND_4") (pintype "passive"))
      (node (ref "U17") (pin "11") (pinfunction "GND_11") (pintype "passive"))
      (node (ref "U17") (pin "13") (pinfunction "GND_13") (pintype "passive"))
      (node (ref "U17") (pin "15") (pinfunction "GND_15") (pintype "passive"))
      (node (ref "U17") (pin "17") (pinfunction "GND_17") (pintype "passive"))
      (node (ref "U17") (pin "19") (pinfunction "GND_19") (pintype "passive"))
      (node (ref "U17") (pin "21") (pinfunction "GND_21") (pintype "passive"))
      (node (ref "U17") (pin "23") (pinfunction "GND_23") (pintype "passive"))
      (node (ref "U17") (pin "24") (pinfunction "GND_24") (pintype "passive"))
      (node (ref "U17") (pin "26") (pinfunction "GND_26") (pintype "passive"))
      (node (ref "U17") (pin "28") (pinfunction "GND_28") (pintype "passive"))
      (node (ref "U17") (pin "30") (pinfunction "GND_30") (pintype "passive"))
      (node (ref "U17") (pin "37") (pinfunction "GND_37") (pintype "passive"))
      (node (ref "U18") (pin "1") (pinfunction "Vdd_1") (pintype "passive"))
      (node (ref "U18") (pin "10") (pinfunction "G_10") (pintype "passive"))
      (node (ref "U18") (pin "11") (pinfunction "NC_11") (pintype "passive"))
      (node (ref "U18") (pin "12") (pinfunction "RF2_12") (pintype "passive"))
      (node (ref "U18") (pin "13") (pinfunction "NC_13") (pintype "passive"))
      (node (ref "U18") (pin "14") (pinfunction "NC_14") (pintype "passive"))
      (node (ref "U18") (pin "17") (pinfunction "NC_17") (pintype "passive"))
      (node (ref "U18") (pin "18") (pinfunction "NC_18") (pintype "passive"))
      (node (ref "U18") (pin "19") (pinfunction "NC_19") (pintype "passive"))
      (node (ref "U18") (pin "2") (pinfunction "Vctl_2") (pintype "passive"))
      (node (ref "U18") (pin "20") (pinfunction "NC_20") (pintype "passive"))
      (node (ref "U18") (pin "21") (pinfunction "G_21") (pintype "passive"))
      (node (ref "U18") (pin "23") (pinfunction "G_23") (pintype "passive"))
      (node (ref "U18") (pin "24") (pinfunction "NC_24") (pintype "passive"))
      (node (ref "U18") (pin "25") (pinfunction "G_25") (pintype "passive"))
      (node (ref "U18") (pin "3") (pinfunction "G_3") (pintype "passive"))
      (node (ref "U18") (pin "5") (pinfunction "G_5") (pintype "passive"))
      (node (ref "U18") (pin "6") (pinfunction "NC_6") (pintype "passive"))
      (node (ref "U18") (pin "7") (pinfunction "NC_7") (pintype "passive"))
      (node (ref "U18") (pin "8") (pinfunction "G_8") (pintype "passive"))
      (node (ref "U20") (pin "1") (pinfunction "Vdd_1") (pintype "passive"))
      (node (ref "U20") (pin "10") (pinfunction "G_10") (pintype "passive"))
      (node (ref "U20") (pin "11") (pinfunction "NC_11") (pintype "passive"))
      (node (ref "U20") (pin "12") (pinfunction "RF2_12") (pintype "passive"))
      (node (ref "U20") (pin "13") (pinfunction "NC_13") (pintype "passive"))
      (node (ref "U20") (pin "14") (pinfunction "NC_14") (pintype "passive"))
      (node (ref "U20") (pin "17") (pinfunction "NC_17") (pintype "passive"))
      (node (ref "U20") (pin "18") (pinfunction "NC_18") (pintype "passive"))
      (node (ref "U20") (pin "19") (pinfunction "NC_19") (pintype "passive"))
      (node (ref "U20") (pin "2") (pinfunction "Vctl_2") (pintype "passive"))
      (node (ref "U20") (pin "20") (pinfunction "NC_20") (pintype "passive"))
      (node (ref "U20") (pin "21") (pinfunction "G_21") (pintype "passive"))
      (node (ref "U20") (pin "23") (pinfunction "G_23") (pintype "passive"))
      (node (ref "U20") (pin "24") (pinfunction "NC_24") (pintype "passive"))
      (node (ref "U20") (pin "25") (pinfunction "G_25") (pintype "passive"))
      (node (ref "U20") (pin "3") (pinfunction "G_3") (pintype "passive"))
      (node (ref "U20") (pin "5") (pinfunction "G_5") (pintype "passive"))
      (node (ref "U20") (pin "6") (pinfunction "NC_6") (pintype "passive"))
      (node (ref "U20") (pin "7") (pinfunction "NC_7") (pintype "passive"))
      (node (ref "U20") (pin "8") (pinfunction "G_8") (pintype "passive"))
      (node (ref "U22") (pin "1") (pinfunction "Vdd_1") (pintype "passive"))
      (node (ref "U22") (pin "10") (pinfunction "G_10") (pintype "passive"))
      (node (ref "U22") (pin "11") (pinfunction "NC_11") (pintype "passive"))
      (node (ref "U22") (pin "12") (pinfunction "RF2_12") (pintype "passive"))
      (node (ref "U22") (pin "13") (pinfunction "NC_13") (pintype "passive"))
      (node (ref "U22") (pin "14") (pinfunction "NC_14") (pintype "passive"))
      (node (ref "U22") (pin "17") (pinfunction "NC_17") (pintype "passive"))
      (node (ref "U22") (pin "18") (pinfunction "NC_18") (pintype "passive"))
      (node (ref "U22") (pin "19") (pinfunction "NC_19") (pintype "passive"))
      (node (ref "U22") (pin "2") (pinfunction "Vctl_2") (pintype "passive"))
      (node (ref "U22") (pin "20") (pinfunction "NC_20") (pintype "passive"))
      (node (ref "U22") (pin "21") (pinfunction "G_21") (pintype "passive"))
      (node (ref "U22") (pin "23") (pinfunction "G_23") (pintype "passive"))
      (node (ref "U22") (pin "24") (pinfunction "NC_24") (pintype "passive"))
      (node (ref "U22") (pin "25") (pinfunction "G_25") (pintype "passive"))
      (node (ref "U22") (pin "3") (pinfunction "G_3") (pintype "passive"))
      (node (ref "U22") (pin "5") (pinfunction "G_5") (pintype "passive"))
      (node (ref "U22") (pin "6") (pinfunction "NC_6") (pintype "passive"))
      (node (ref "U22") (pin "7") (pinfunction "NC_7") (pintype "passive"))
      (node (ref "U22") (pin "8") (pinfunction "G_8") (pintype "passive"))
      (node (ref "U23") (pin "1") (pinfunction "Vdd_1") (pintype "passive"))
      (node (ref "U23") (pin "10") (pinfunction "G_10") (pintype "passive"))
      (node (ref "U23") (pin "11") (pinfunction "NC_11") (pintype "passive"))
      (node (ref "U23") (pin "12") (pinfunction "RF2_12") (pintype "passive"))
      (node (ref "U23") (pin "13") (pinfunction "NC_13") (pintype "passive"))
      (node (ref "U23") (pin "14") (pinfunction "NC_14") (pintype "passive"))
      (node (ref "U23") (pin "17") (pinfunction "NC_17") (pintype "passive"))
      (node (ref "U23") (pin "18") (pinfunction "NC_18") (pintype "passive"))
      (node (ref "U23") (pin "19") (pinfunction "NC_19") (pintype "passive"))
      (node (ref "U23") (pin "2") (pinfunction "Vctl_2") (pintype "passive"))
      (node (ref "U23") (pin "20") (pinfunction "NC_20") (pintype "passive"))
      (node (ref "U23") (pin "21") (pinfunction "G_21") (pintype "passive"))
      (node (ref "U23") (pin "23") (pinfunction "G_23") (pintype "passive"))
      (node (ref "U23") (pin "24") (pinfunction "NC_24") (pintype "passive"))
      (node (ref "U23") (pin "25") (pinfunction "G_25") (pintype "passive"))
      (node (ref "U23") (pin "3") (pinfunction "G_3") (pintype "passive"))
      (node (ref "U23") (pin "5") (pinfunction "G_5") (pintype "passive"))
      (node (ref "U23") (pin "6") (pinfunction "NC_6") (pintype "passive"))
      (node (ref "U23") (pin "7") (pinfunction "NC_7") (pintype "passive"))
      (node (ref "U23") (pin "8") (pinfunction "G_8") (pintype "passive"))
      (node (ref "U25") (pin "1") (pinfunction "Vdd_1") (pintype "passive"))
      (node (ref "U25") (pin "10") (pinfunction "G_10") (pintype "passive"))
      (node (ref "U25") (pin "11") (pinfunction "NC_11") (pintype "passive"))
      (node (ref "U25") (pin "12") (pinfunction "RF2_12") (pintype "passive"))
      (node (ref "U25") (pin "13") (pinfunction "NC_13") (pintype "passive"))
      (node (ref "U25") (pin "14") (pinfunction "NC_14") (pintype "passive"))
      (node (ref "U25") (pin "17") (pinfunction "NC_17") (pintype "passive"))
      (node (ref "U25") (pin "18") (pinfunction "NC_18") (pintype "passive"))
      (node (ref "U25") (pin "19") (pinfunction "NC_19") (pintype "passive"))
      (node (ref "U25") (pin "2") (pinfunction "Vctl_2") (pintype "passive"))
      (node (ref "U25") (pin "20") (pinfunction "NC_20") (pintype "passive"))
      (node (ref "U25") (pin "21") (pinfunction "G_21") (pintype "passive"))
      (node (ref "U25") (pin "23") (pinfunction "G_23") (pintype "passive"))
      (node (ref "U25") (pin "24") (pinfunction "NC_24") (pintype "passive"))
      (node (ref "U25") (pin "25") (pinfunction "G_25") (pintype "passive"))
      (node (ref "U25") (pin "3") (pinfunction "G_3") (pintype "passive"))
      (node (ref "U25") (pin "5") (pinfunction "G_5") (pintype "passive"))
      (node (ref "U25") (pin "6") (pinfunction "NC_6") (pintype "passive"))
      (node (ref "U25") (pin "7") (pinfunction "NC_7") (pintype "passive"))
      (node (ref "U25") (pin "8") (pinfunction "G_8") (pintype "passive"))
      (node (ref "U31") (pin "2") (pinfunction "GND_2") (pintype "passive"))
      (node (ref "U31") (pin "4") (pinfunction "4_4") (pintype "passive"))
      (node (ref "U33") (pin "2") (pinfunction "GND_2") (pintype "passive"))
      (node (ref "U33") (pin "4") (pinfunction "4_4") (pintype "passive"))
      (node (ref "U35") (pin "1") (pinfunction "Vdd_1") (pintype "passive"))
      (node (ref "U35") (pin "10") (pinfunction "G_10") (pintype "passive"))
      (node (ref "U35") (pin "11") (pinfunction "NC_11") (pintype "passive"))
      (node (ref "U35") (pin "12") (pinfunction "RF2_12") (pintype "passive"))
      (node (ref "U35") (pin "13") (pinfunction "NC_13") (pintype "passive"))
      (node (ref "U35") (pin "14") (pinfunction "NC_14") (pintype "passive"))
      (node (ref "U35") (pin "17") (pinfunction "NC_17") (pintype "passive"))
      (node (ref "U35") (pin "18") (pinfunction "NC_18") (pintype "passive"))
      (node (ref "U35") (pin "19") (pinfunction "NC_19") (pintype "passive"))
      (node (ref "U35") (pin "2") (pinfunction "Vctl_2") (pintype "passive"))
      (node (ref "U35") (pin "20") (pinfunction "NC_20") (pintype "passive"))
      (node (ref "U35") (pin "21") (pinfunction "G_21") (pintype "passive"))
      (node (ref "U35") (pin "23") (pinfunction "G_23") (pintype "passive"))
      (node (ref "U35") (pin "24") (pinfunction "NC_24") (pintype "passive"))
      (node (ref "U35") (pin "25") (pinfunction "G_25") (pintype "passive"))
      (node (ref "U35") (pin "3") (pinfunction "G_3") (pintype "passive"))
      (node (ref "U35") (pin "5") (pinfunction "G_5") (pintype "passive"))
      (node (ref "U35") (pin "6") (pinfunction "NC_6") (pintype "passive"))
      (node (ref "U35") (pin "7") (pinfunction "NC_7") (pintype "passive"))
      (node (ref "U35") (pin "8") (pinfunction "G_8") (pintype "passive"))
      (node (ref "U4") (pin "1") (pinfunction "Vdd_1") (pintype "passive"))
      (node (ref "U4") (pin "10") (pinfunction "G_10") (pintype "passive"))
      (node (ref "U4") (pin "11") (pinfunction "NC_11") (pintype "passive"))
      (node (ref "U4") (pin "12") (pinfunction "RF2_12") (pintype "passive"))
      (node (ref "U4") (pin "13") (pinfunction "NC_13") (pintype "passive"))
      (node (ref "U4") (pin "14") (pinfunction "NC_14") (pintype "passive"))
      (node (ref "U4") (pin "17") (pinfunction "NC_17") (pintype "passive"))
      (node (ref "U4") (pin "18") (pinfunction "NC_18") (pintype "passive"))
      (node (ref "U4") (pin "19") (pinfunction "NC_19") (pintype "passive"))
      (node (ref "U4") (pin "2") (pinfunction "Vctl_2") (pintype "passive"))
      (node (ref "U4") (pin "20") (pinfunction "NC_20") (pintype "passive"))
      (node (ref "U4") (pin "21") (pinfunction "G_21") (pintype "passive"))
      (node (ref "U4") (pin "23") (pinfunction "G_23") (pintype "passive"))
      (node (ref "U4") (pin "24") (pinfunction "NC_24") (pintype "passive"))
      (node (ref "U4") (pin "25") (pinfunction "G_25") (pintype "passive"))
      (node (ref "U4") (pin "3") (pinfunction "G_3") (pintype "passive"))
      (node (ref "U4") (pin "5") (pinfunction "G_5") (pintype "passive"))
      (node (ref "U4") (pin "6") (pinfunction "NC_6") (pintype "passive"))
      (node (ref "U4") (pin "7") (pinfunction "NC_7") (pintype "passive"))
      (node (ref "U4") (pin "8") (pinfunction "G_8") (pintype "passive"))
      (node (ref "U7") (pin "1") (pinfunction "Vdd_1") (pintype "passive"))
      (node (ref "U7") (pin "10") (pinfunction "G_10") (pintype "passive"))
      (node (ref "U7") (pin "11") (pinfunction "NC_11") (pintype "passive"))
      (node (ref "U7") (pin "12") (pinfunction "RF2_12") (pintype "passive"))
      (node (ref "U7") (pin "13") (pinfunction "NC_13") (pintype "passive"))
      (node (ref "U7") (pin "14") (pinfunction "NC_14") (pintype "passive"))
      (node (ref "U7") (pin "17") (pinfunction "NC_17") (pintype "passive"))
      (node (ref "U7") (pin "18") (pinfunction "NC_18") (pintype "passive"))
      (node (ref "U7") (pin "19") (pinfunction "NC_19") (pintype "passive"))
      (node (ref "U7") (pin "2") (pinfunction "Vctl_2") (pintype "passive"))
      (node (ref "U7") (pin "20") (pinfunction "NC_20") (pintype "passive"))
      (node (ref "U7") (pin "21") (pinfunction "G_21") (pintype "passive"))
      (node (ref "U7") (pin "23") (pinfunction "G_23") (pintype "passive"))
      (node (ref "U7") (pin "24") (pinfunction "NC_24") (pintype "passive"))
      (node (ref "U7") (pin "25") (pinfunction "G_25") (pintype "passive"))
      (node (ref "U7") (pin "3") (pinfunction "G_3") (pintype "passive"))
      (node (ref "U7") (pin "5") (pinfunction "G_5") (pintype "passive"))
      (node (ref "U7") (pin "6") (pinfunction "NC_6") (pintype "passive"))
      (node (ref "U7") (pin "7") (pinfunction "NC_7") (pintype "passive"))
      (node (ref "U7") (pin "8") (pinfunction "G_8") (pintype "passive"))
      (node (ref "U8") (pin "1") (pinfunction "Vdd_1") (pintype "passive"))
      (node (ref "U8") (pin "10") (pinfunction "G_10") (pintype "passive"))
      (node (ref "U8") (pin "11") (pinfunction "NC_11") (pintype "passive"))
      (node (ref "U8") (pin "12") (pinfunction "RF2_12") (pintype "passive"))
      (node (ref "U8") (pin "13") (pinfunction "NC_13") (pintype "passive"))
      (node (ref "U8") (pin "14") (pinfunction "NC_14") (pintype "passive"))
      (node (ref "U8") (pin "17") (pinfunction "NC_17") (pintype "passive"))
      (node (ref "U8") (pin "18") (pinfunction "NC_18") (pintype "passive"))
      (node (ref "U8") (pin "19") (pinfunction "NC_19") (pintype "passive"))
      (node (ref "U8") (pin "2") (pinfunction "Vctl_2") (pintype "passive"))
      (node (ref "U8") (pin "20") (pinfunction "NC_20") (pintype "passive"))
      (node (ref "U8") (pin "21") (pinfunction "G_21") (pintype "passive"))
      (node (ref "U8") (pin "23") (pinfunction "G_23") (pintype "passive"))
      (node (ref "U8") (pin "24") (pinfunction "NC_24") (pintype "passive"))
      (node (ref "U8") (pin "25") (pinfunction "G_25") (pintype "passive"))
      (node (ref "U8") (pin "3") (pinfunction "G_3") (pintype "passive"))
      (node (ref "U8") (pin "5") (pinfunction "G_5") (pintype "passive"))
      (node (ref "U8") (pin "6") (pinfunction "NC_6") (pintype "passive"))
      (node (ref "U8") (pin "7") (pinfunction "NC_7") (pintype "passive"))
      (node (ref "U8") (pin "8") (pinfunction "G_8") (pintype "passive"))
      (node (ref "U82") (pin "1") (pinfunction "G_1") (pintype "passive"))
      (node (ref "U82") (pin "12") (pinfunction "G_12") (pintype "passive"))
      (node (ref "U82") (pin "13") (pinfunction "G_13") (pintype "passive"))
      (node (ref "U82") (pin "14") (pinfunction "G_14") (pintype "passive"))
      (node (ref "U82") (pin "16") (pinfunction "G_16") (pintype "passive"))
      (node (ref "U82") (pin "17") (pinfunction "G_17") (pintype "passive"))
      (node (ref "U82") (pin "18") (pinfunction "G_18") (pintype "passive"))
      (node (ref "U82") (pin "19") (pinfunction "G_19") (pintype "passive"))
      (node (ref "U82") (pin "2") (pinfunction "G_2") (pintype "passive"))
      (node (ref "U82") (pin "20") (pinfunction "G_20") (pintype "passive"))
      (node (ref "U82") (pin "21") (pinfunction "G_21") (pintype "passive"))
      (node (ref "U82") (pin "23") (pinfunction "G_23") (pintype "passive"))
      (node (ref "U82") (pin "24") (pinfunction "G_24") (pintype "passive"))
      (node (ref "U82") (pin "25") (pinfunction "G_25") (pintype "passive"))
      (node (ref "U82") (pin "5") (pinfunction "G_5") (pintype "passive"))
      (node (ref "U82") (pin "6") (pinfunction "G_6") (pintype "passive"))
      (node (ref "U82") (pin "7") (pinfunction "G_7") (pintype "passive"))
      (node (ref "U9") (pin "1") (pinfunction "Vdd_1") (pintype "passive"))
      (node (ref "U9") (pin "10") (pinfunction "G_10") (pintype "passive"))
      (node (ref "U9") (pin "11") (pinfunction "NC_11") (pintype "passive"))
      (node (ref "U9") (pin "12") (pinfunction "RF2_12") (pintype "passive"))
      (node (ref "U9") (pin "13") (pinfunction "NC_13") (pintype "passive"))
      (node (ref "U9") (pin "14") (pinfunction "NC_14") (pintype "passive"))
      (node (ref "U9") (pin "17") (pinfunction "NC_17") (pintype "passive"))
      (node (ref "U9") (pin "18") (pinfunction "NC_18") (pintype "passive"))
      (node (ref "U9") (pin "19") (pinfunction "NC_19") (pintype "passive"))
      (node (ref "U9") (pin "2") (pinfunction "Vctl_2") (pintype "passive"))
      (node (ref "U9") (pin "20") (pinfunction "NC_20") (pintype "passive"))
      (node (ref "U9") (pin "21") (pinfunction "G_21") (pintype "passive"))
      (node (ref "U9") (pin "23") (pinfunction "G_23") (pintype "passive"))
      (node (ref "U9") (pin "24") (pinfunction "NC_24") (pintype "passive"))
      (node (ref "U9") (pin "25") (pinfunction "G_25") (pintype "passive"))
      (node (ref "U9") (pin "3") (pinfunction "G_3") (pintype "passive"))
      (node (ref "U9") (pin "5") (pinfunction "G_5") (pintype "passive"))
      (node (ref "U9") (pin "6") (pinfunction "NC_6") (pintype "passive"))
      (node (ref "U9") (pin "7") (pinfunction "NC_7") (pintype "passive"))
      (node (ref "U9") (pin "8") (pinfunction "G_8") (pintype "passive"))
      (node (ref "X5") (pin "1") (pinfunction "Pri+_1") (pintype "passive"))
    )
    (net (code "27") (name "Net-(AT4-IN{slash}OUT-Pad3)") (class "Default")
      (node (ref "AT4") (pin "3") (pinfunction "IN/OUT_3") (pintype "passive"))
      (node (ref "C29") (pin "1") (pintype "passive"))
    )
    (net (code "28") (name "Net-(AT7-IN{slash}OUT-Pad3)") (class "Default")
      (node (ref "AT7") (pin "3") (pinfunction "IN/OUT_3") (pintype "passive"))
      (node (ref "C116") (pin "1") (pintype "passive"))
    )
    (net (code "29") (name "Net-(AT8-IN{slash}OUT-Pad3)") (class "Default")
      (node (ref "AT8") (pin "3") (pinfunction "IN/OUT_3") (pintype "passive"))
      (node (ref "C203") (pin "1") (pintype "passive"))
    )
    (net (code "30") (name "Net-(AT13-IN{slash}OUT-Pad3)") (class "Default")
      (node (ref "AT13") (pin "3") (pinfunction "IN/OUT_3") (pintype "passive"))
      (node (ref "C831") (pin "1") (pintype "passive"))
    )
    (net (code "31") (name "Net-(AT53-IN{slash}OUT-Pad3)") (class "Default")
      (node (ref "AT53") (pin "3") (pinfunction "IN/OUT_3") (pintype "passive"))
      (node (ref "C853") (pin "1") (pintype "passive"))
    )
    (net (code "32") (name "Net-(AT55-IN{slash}OUT-Pad3)") (class "Default")
      (node (ref "AT55") (pin "3") (pinfunction "IN/OUT_3") (pintype "passive"))
      (node (ref "C871") (pin "1") (pintype "passive"))
    )
    (net (code "33") (name "Net-(AT57-IN{slash}OUT-Pad1)") (class "Default")
      (node (ref "AT57") (pin "1") (pinfunction "IN/OUT_1") (pintype "passive"))
      (node (ref "C1228") (pin "2") (pintype "passive"))
    )
    (net (code "34") (name "Net-(AT59-IN{slash}OUT-Pad1)") (class "Default")
      (node (ref "AT59") (pin "1") (pinfunction "IN/OUT_1") (pintype "passive"))
      (node (ref "C958") (pin "1") (pintype "passive"))
    )
    (net (code "35") (name "Net-(AT59-IN{slash}OUT-Pad3)") (class "Default")
      (node (ref "AT59") (pin "3") (pinfunction "IN/OUT_3") (pintype "passive"))
      (node (ref "C957") (pin "2") (pintype "passive"))
    )
    (net (code "36") (name "Net-(AT61-IN{slash}OUT-Pad1)") (class "Default")
      (node (ref "AT61") (pin "1") (pinfunction "IN/OUT_1") (pintype "passive"))
      (node (ref "C1229") (pin "1") (pintype "passive"))
    )
    (net (code "37") (name "Net-(AT62-IN{slash}OUT-Pad3)") (class "Default")
      (node (ref "AT62") (pin "3") (pinfunction "IN/OUT_3") (pintype "passive"))
      (node (ref "C722") (pin "2") (pintype "passive"))
    )
    (net (code "38") (name "Net-(C18-Pad1)") (class "Default")
      (node (ref "C18") (pin "1") (pintype "passive"))
      (node (ref "U7") (pin "4") (pinfunction "NC_4") (pintype "passive"))
    )
    (net (code "39") (name "Net-(C25-Pad1)") (class "Default")
      (node (ref "C25") (pin "1") (pintype "passive"))
      (node (ref "U4") (pin "4") (pinfunction "NC_4") (pintype "passive"))
    )
    (net (code "40") (name "Net-(C111-Pad1)") (class "Default")
      (node (ref "C111") (pin "1") (pintype "passive"))
      (node (ref "U9") (pin "4") (pinfunction "NC_4") (pintype "passive"))
    )
    (net (code "41") (name "Net-(C114-Pad1)") (class "Default")
      (node (ref "C114") (pin "1") (pintype "passive"))
      (node (ref "U8") (pin "4") (pinfunction "NC_4") (pintype "passive"))
    )
    (net (code "42") (name "Net-(C188-Pad1)") (class "Default")
      (node (ref "C188") (pin "1") (pintype "passive"))
      (node (ref "U13") (pin "4") (pinfunction "NC_4") (pintype "passive"))
    )
    (net (code "43") (name "Net-(C201-Pad1)") (class "Default")
      (node (ref "C201") (pin "1") (pintype "passive"))
      (node (ref "U10") (pin "4") (pinfunction "NC_4") (pintype "passive"))
    )
    (net (code "44") (name "Net-(C232-Pad2)") (class "Default")
      (node (ref "C232") (pin "2") (pintype "passive"))
      (node (ref "L76") (pin "1") (pinfunction "1_1") (pintype "passive"))
      (node (ref "U15") (pin "32") (pinfunction "VEE_32") (pintype "passive"))
    )
    (net (code "45") (name "Net-(C352-Pad1)") (class "Default")
      (node (ref "C352") (pin "1") (pintype "passive"))
      (node (ref "L19") (pin "2") (pinfunction "2_2") (pintype "passive"))
      (node (ref "U17") (pin "33") (pinfunction "VCC_33") (pintype "passive"))
    )
    (net (code "46") (name "Net-(C366-Pad1)") (class "Default")
      (node (ref "C366") (pin "1") (pintype "passive"))
      (node (ref "L20") (pin "2") (pinfunction "2_2") (pintype "passive"))
      (node (ref "U17") (pin "32") (pinfunction "VEE_32") (pintype "passive"))
    )
    (net (code "47") (name "Net-(C400-Pad2)") (class "Default")
      (node (ref "C400") (pin "2") (pintype "passive"))
      (node (ref "L77") (pin "1") (pinfunction "1_1") (pintype "passive"))
      (node (ref "U15") (pin "33") (pinfunction "VCC_33") (pintype "passive"))
    )
    (net (code "48") (name "Net-(C402-Pad1)") (class "Default")
      (node (ref "C402") (pin "1") (pintype "passive"))
      (node (ref "FL39") (pin "3") (pinfunction "GND_3") (pintype "passive"))
    )
    (net (code "49") (name "Net-(C402-Pad2)") (class "Default")
      (node (ref "C402") (pin "2") (pintype "passive"))
      (node (ref "C956") (pin "1") (pintype "passive"))
      (node (ref "C959") (pin "2") (pintype "passive"))
    )
    (net (code "50") (name "Net-(C822-Pad1)") (class "Default")
      (node (ref "C822") (pin "1") (pintype "passive"))
      (node (ref "U20") (pin "4") (pinfunction "NC_4") (pintype "passive"))
    )
    (net (code "51") (name "Net-(C829-Pad1)") (class "Default")
      (node (ref "C829") (pin "1") (pintype "passive"))
      (node (ref "U18") (pin "4") (pinfunction "NC_4") (pintype "passive"))
    )
    (net (code "52") (name "Net-(C832-Pad1)") (class "Default")
      (node (ref "C832") (pin "1") (pintype "passive"))
      (node (ref "L156") (pin "1") (pinfunction "1_1") (pintype "passive"))
      (node (ref "R54") (pin "2") (pintype "passive"))
    )
    (net (code "53") (name "Net-(C834-Pad1)") (class "Default")
      (node (ref "C834") (pin "1") (pintype "passive"))
      (node (ref "L158") (pin "1") (pinfunction "1_1") (pintype "passive"))
      (node (ref "R11") (pin "2") (pintype "passive"))
    )
    (net (code "54") (name "Net-(C845-Pad1)") (class "Default")
      (node (ref "C845") (pin "1") (pintype "passive"))
      (node (ref "U23") (pin "4") (pinfunction "NC_4") (pintype "passive"))
    )
    (net (code "55") (name "Net-(C846-Pad1)") (class "Default")
      (node (ref "C846") (pin "1") (pintype "passive"))
      (node (ref "L229") (pin "1") (pinfunction "1_1") (pintype "passive"))
      (node (ref "R14") (pin "2") (pintype "passive"))
    )
    (net (code "56") (name "Net-(C849-Pad1)") (class "Default")
      (node (ref "C849") (pin "1") (pintype "passive"))
      (node (ref "L230") (pin "1") (pinfunction "1_1") (pintype "passive"))
      (node (ref "R57") (pin "2") (pintype "passive"))
    )
    (net (code "57") (name "Net-(C851-Pad1)") (class "Default")
      (node (ref "C851") (pin "1") (pintype "passive"))
      (node (ref "U22") (pin "4") (pinfunction "NC_4") (pintype "passive"))
    )
    (net (code "58") (name "Net-(C866-Pad1)") (class "Default")
      (node (ref "C866") (pin "1") (pintype "passive"))
      (node (ref "U35") (pin "4") (pinfunction "NC_4") (pintype "passive"))
    )
    (net (code "59") (name "Net-(C869-Pad1)") (class "Default")
      (node (ref "C869") (pin "1") (pintype "passive"))
      (node (ref "U25") (pin "4") (pinfunction "NC_4") (pintype "passive"))
    )
    (net (code "60") (name "Net-(C886-Pad1)") (class "Default")
      (node (ref "C886") (pin "1") (pintype "passive"))
      (node (ref "C887") (pin "2") (pintype "passive"))
      (node (ref "C888") (pin "2") (pintype "passive"))
      (node (ref "C889") (pin "2") (pintype "passive"))
      (node (ref "C890") (pin "2") (pintype "passive"))
      (node (ref "L90") (pin "1") (pinfunction "1_1") (pintype "passive"))
      (node (ref "U82") (pin "10") (pinfunction "VCC_10") (pintype "passive"))
      (node (ref "U82") (pin "11") (pinfunction "VCC_11") (pintype "passive"))
      (node (ref "U82") (pin "8") (pinfunction "VCC_8") (pintype "passive"))
      (node (ref "U82") (pin "9") (pinfunction "VCC_9") (pintype "passive"))
    )
    (net (code "61") (name "Net-(C955-Pad1)") (class "Default")
      (node (ref "C955") (pin "1") (pintype "passive"))
      (node (ref "L206") (pin "2") (pinfunction "2_2") (pintype "passive"))
      (node (ref "L248") (pin "1") (pinfunction "1_1") (pintype "passive"))
    )
    (net (code "62") (name "Net-(C956-Pad2)") (class "Default")
      (node (ref "C956") (pin "2") (pintype "passive"))
      (node (ref "U31") (pin "1") (pinfunction "1_1") (pintype "passive"))
    )
    (net (code "63") (name "Net-(C957-Pad1)") (class "Default")
      (node (ref "C957") (pin "1") (pintype "passive"))
      (node (ref "L248") (pin "2") (pinfunction "2_2") (pintype "passive"))
      (node (ref "U31") (pin "3") (pinfunction "3_3") (pintype "passive"))
    )
    (net (code "64") (name "Net-(C958-Pad2)") (class "Default")
      (node (ref "C958") (pin "2") (pintype "passive"))
      (node (ref "U33") (pin "1") (pinfunction "1_1") (pintype "passive"))
    )
    (net (code "65") (name "Net-(C967-Pad1)") (class "Default")
      (node (ref "C967") (pin "1") (pintype "passive"))
      (node (ref "L249") (pin "2") (pinfunction "2_2") (pintype "passive"))
      (node (ref "L250") (pin "1") (pinfunction "1_1") (pintype "passive"))
    )
    (net (code "66") (name "Net-(C968-Pad1)") (class "Default")
      (node (ref "C968") (pin "1") (pintype "passive"))
      (node (ref "L250") (pin "2") (pinfunction "2_2") (pintype "passive"))
      (node (ref "U33") (pin "3") (pinfunction "3_3") (pintype "passive"))
    )
    (net (code "67") (name "Net-(FL11-IN)") (class "Default")
      (node (ref "C115") (pin "1") (pintype "passive"))
      (node (ref "FL11") (pin "1") (pinfunction "IN_1") (pintype "passive"))
      (node (ref "L90") (pin "2") (pinfunction "2_2") (pintype "passive"))
    )
    (net (code "68") (name "Net-(FL11-OUT)") (class "Default")
      (node (ref "C893") (pin "1") (pintype "passive"))
      (node (ref "FL11") (pin "3") (pinfunction "OUT_3") (pintype "passive"))
      (node (ref "FL22") (pin "1") (pinfunction "IN_1") (pintype "passive"))
    )
    (net (code "69") (name "Net-(FL23-IN)") (class "Default")
      (node (ref "C954") (pin "1") (pintype "passive"))
      (node (ref "FL23") (pin "1") (pinfunction "IN_1") (pintype "passive"))
      (node (ref "R671") (pin "1") (pintype "passive"))
    )
    (net (code "70") (name "Net-(FL23-OUT)") (class "Default")
      (node (ref "C730") (pin "2") (pintype "passive"))
      (node (ref "FL23") (pin "3") (pinfunction "OUT_3") (pintype "passive"))
      (node (ref "FL45") (pin "3") (pinfunction "OUT_3") (pintype "passive"))
    )
    (net (code "71") (name "Net-(FL27-IN)") (class "Default")
      (node (ref "AT2") (pin "1") (pinfunction "IN/OUT_1") (pintype "passive"))
      (node (ref "FL27") (pin "1") (pinfunction "IN_1") (pintype "passive"))
      (node (ref "L8") (pin "2") (pinfunction "2_2") (pintype "passive"))
    )
    (net (code "72") (name "Net-(FL27-OUT)") (class "Default")
      (node (ref "C25") (pin "2") (pintype "passive"))
      (node (ref "FL27") (pin "2") (pinfunction "OUT_2") (pintype "passive"))
      (node (ref "L10") (pin "2") (pinfunction "2_2") (pintype "passive"))
    )
    (net (code "73") (name "Net-(FL28-IN)") (class "Default")
      (node (ref "AT4") (pin "1") (pinfunction "IN/OUT_1") (pintype "passive"))
      (node (ref "FL28") (pin "1") (pinfunction "IN_1") (pintype "passive"))
      (node (ref "L9") (pin "2") (pinfunction "2_2") (pintype "passive"))
    )
    (net (code "74") (name "Net-(FL28-OUT)") (class "Default")
      (node (ref "AT2") (pin "3") (pinfunction "IN/OUT_3") (pintype "passive"))
      (node (ref "FL28") (pin "2") (pinfunction "OUT_2") (pintype "passive"))
      (node (ref "L11") (pin "2") (pinfunction "2_2") (pintype "passive"))
    )
    (net (code "75") (name "Net-(FL29-IN)") (class "Default")
      (node (ref "AT5") (pin "1") (pinfunction "IN/OUT_1") (pintype "passive"))
      (node (ref "FL29") (pin "1") (pinfunction "IN_1") (pintype "passive"))
      (node (ref "L18") (pin "2") (pinfunction "2_2") (pintype "passive"))
    )
    (net (code "76") (name "Net-(FL29-OUT)") (class "Default")
      (node (ref "C114") (pin "2") (pintype "passive"))
      (node (ref "FL29") (pin "2") (pinfunction "OUT_2") (pintype "passive"))
      (node (ref "L17") (pin "2") (pinfunction "2_2") (pintype "passive"))
    )
    (net (code "77") (name "Net-(FL33-IN)") (class "Default")
      (node (ref "AT7") (pin "1") (pinfunction "IN/OUT_1") (pintype "passive"))
      (node (ref "FL33") (pin "1") (pinfunction "IN_1") (pintype "passive"))
      (node (ref "L54") (pin "2") (pinfunction "2_2") (pintype "passive"))
    )
    (net (code "78") (name "Net-(FL33-OUT)") (class "Default")
      (node (ref "AT5") (pin "3") (pinfunction "IN/OUT_3") (pintype "passive"))
      (node (ref "FL33") (pin "2") (pinfunction "OUT_2") (pintype "passive"))
      (node (ref "L55") (pin "2") (pinfunction "2_2") (pintype "passive"))
    )
    (net (code "79") (name "Net-(FL34-IN)") (class "Default")
      (node (ref "AT9") (pin "1") (pinfunction "IN/OUT_1") (pintype "passive"))
      (node (ref "FL34") (pin "1") (pinfunction "IN_1") (pintype "passive"))
      (node (ref "L79") (pin "2") (pinfunction "2_2") (pintype "passive"))
    )
    (net (code "80") (name "Net-(FL34-OUT)") (class "Default")
      (node (ref "C201") (pin "2") (pintype "passive"))
      (node (ref "FL34") (pin "2") (pinfunction "OUT_2") (pintype "passive"))
      (node (ref "L78") (pin "2") (pinfunction "2_2") (pintype "passive"))
    )
    (net (code "81") (name "Net-(FL37-IN)") (class "Default")
      (node (ref "AT8") (pin "1") (pinfunction "IN/OUT_1") (pintype "passive"))
      (node (ref "FL37") (pin "1") (pinfunction "IN_1") (pintype "passive"))
      (node (ref "L84") (pin "2") (pinfunction "2_2") (pintype "passive"))
    )
    (net (code "82") (name "Net-(FL37-OUT)") (class "Default")
      (node (ref "AT9") (pin "3") (pinfunction "IN/OUT_3") (pintype "passive"))
      (node (ref "FL37") (pin "2") (pinfunction "OUT_2") (pintype "passive"))
      (node (ref "L85") (pin "2") (pinfunction "2_2") (pintype "passive"))
    )
    (net (code "83") (name "Net-(FL39-IN)") (class "Default")
      (node (ref "C401") (pin "2") (pintype "passive"))
      (node (ref "FL39") (pin "1") (pinfunction "IN_1") (pintype "passive"))
    )
    (net (code "84") (name "Net-(FL43-IN)") (class "Default")
      (node (ref "AT11") (pin "1") (pinfunction "IN/OUT_1") (pintype "passive"))
      (node (ref "FL43") (pin "1") (pinfunction "IN_1") (pintype "passive"))
      (node (ref "L154") (pin "2") (pinfunction "2_2") (pintype "passive"))
    )
    (net (code "85") (name "Net-(FL43-OUT)") (class "Default")
      (node (ref "C829") (pin "2") (pintype "passive"))
      (node (ref "FL43") (pin "2") (pinfunction "OUT_2") (pintype "passive"))
      (node (ref "L153") (pin "2") (pinfunction "2_2") (pintype "passive"))
    )
    (net (code "86") (name "Net-(FL45-IN)") (class "Default")
      (node (ref "C952") (pin "2") (pintype "passive"))
      (node (ref "FL45") (pin "1") (pinfunction "IN_1") (pintype "passive"))
      (node (ref "FL47") (pin "3") (pinfunction "OUT_3") (pintype "passive"))
    )
    (net (code "87") (name "Net-(FL47-IN)") (class "Default")
      (node (ref "C953") (pin "2") (pintype "passive"))
      (node (ref "FL47") (pin "1") (pinfunction "IN_1") (pintype "passive"))
      (node (ref "L206") (pin "1") (pinfunction "1_1") (pintype "passive"))
    )
    (net (code "88") (name "Net-(FL48-IN)") (class "Default")
      (node (ref "C968") (pin "2") (pintype "passive"))
      (node (ref "FL48") (pin "1") (pinfunction "IN_1") (pintype "passive"))
    )
    (net (code "89") (name "Net-(FL49-IN)") (class "Default")
      (node (ref "C966") (pin "1") (pintype "passive"))
      (node (ref "FL49") (pin "1") (pinfunction "IN_1") (pintype "passive"))
      (node (ref "R672") (pin "1") (pintype "passive"))
    )
    (net (code "90") (name "Net-(FL49-OUT)") (class "Default")
      (node (ref "C963") (pin "2") (pintype "passive"))
      (node (ref "FL49") (pin "3") (pinfunction "OUT_3") (pintype "passive"))
      (node (ref "FL50") (pin "3") (pinfunction "OUT_3") (pintype "passive"))
    )
    (net (code "91") (name "Net-(FL50-IN)") (class "Default")
      (node (ref "C964") (pin "2") (pintype "passive"))
      (node (ref "FL50") (pin "1") (pinfunction "IN_1") (pintype "passive"))
      (node (ref "FL51") (pin "3") (pinfunction "OUT_3") (pintype "passive"))
    )
    (net (code "92") (name "Net-(FL51-IN)") (class "Default")
      (node (ref "C965") (pin "2") (pintype "passive"))
      (node (ref "FL51") (pin "1") (pinfunction "IN_1") (pintype "passive"))
      (node (ref "L249") (pin "1") (pinfunction "1_1") (pintype "passive"))
    )
    (net (code "93") (name "Net-(FL151-IN)") (class "Default")
      (node (ref "AT13") (pin "1") (pinfunction "IN/OUT_1") (pintype "passive"))
      (node (ref "FL151") (pin "1") (pinfunction "IN_1") (pintype "passive"))
      (node (ref "L155") (pin "2") (pinfunction "2_2") (pintype "passive"))
    )
    (net (code "94") (name "Net-(FL151-OUT)") (class "Default")
      (node (ref "AT11") (pin "3") (pinfunction "IN/OUT_3") (pintype "passive"))
      (node (ref "FL151") (pin "2") (pinfunction "OUT_2") (pintype "passive"))
      (node (ref "L157") (pin "2") (pinfunction "2_2") (pintype "passive"))
    )
    (net (code "95") (name "Net-(FL152-IN)") (class "Default")
      (node (ref "AT15") (pin "1") (pinfunction "IN/OUT_1") (pintype "passive"))
      (node (ref "FL152") (pin "1") (pinfunction "IN_1") (pintype "passive"))
      (node (ref "L232") (pin "2") (pinfunction "2_2") (pintype "passive"))
    )
    (net (code "96") (name "Net-(FL152-OUT)") (class "Default")
      (node (ref "C851") (pin "2") (pintype "passive"))
      (node (ref "FL152") (pin "2") (pinfunction "OUT_2") (pintype "passive"))
      (node (ref "L231") (pin "2") (pinfunction "2_2") (pintype "passive"))
    )
    (net (code "97") (name "Net-(FL153-IN)") (class "Default")
      (node (ref "AT53") (pin "1") (pinfunction "IN/OUT_1") (pintype "passive"))
      (node (ref "FL153") (pin "1") (pinfunction "IN_1") (pintype "passive"))
      (node (ref "L233") (pin "2") (pinfunction "2_2") (pintype "passive"))
    )
    (net (code "98") (name "Net-(FL153-OUT)") (class "Default")
      (node (ref "AT15") (pin "3") (pinfunction "IN/OUT_3") (pintype "passive"))
      (node (ref "FL153") (pin "2") (pinfunction "OUT_2") (pintype "passive"))
      (node (ref "L234") (pin "2") (pinfunction "2_2") (pintype "passive"))
    )
    (net (code "99") (name "Net-(FL173-IN)") (class "Default")
      (node (ref "AT54") (pin "1") (pinfunction "IN/OUT_1") (pintype "passive"))
      (node (ref "FL173") (pin "1") (pinfunction "IN_1") (pintype "passive"))
      (node (ref "L241") (pin "2") (pinfunction "2_2") (pintype "passive"))
    )
    (net (code "100") (name "Net-(FL173-OUT)") (class "Default")
      (node (ref "C869") (pin "2") (pintype "passive"))
      (node (ref "FL173") (pin "2") (pinfunction "OUT_2") (pintype "passive"))
      (node (ref "L240") (pin "2") (pinfunction "2_2") (pintype "passive"))
    )
    (net (code "101") (name "Net-(FL190-IN)") (class "Default")
      (node (ref "AT55") (pin "1") (pinfunction "IN/OUT_1") (pintype "passive"))
      (node (ref "FL190") (pin "1") (pinfunction "IN_1") (pintype "passive"))
      (node (ref "L242") (pin "2") (pinfunction "2_2") (pintype "passive"))
    )
    (net (code "102") (name "Net-(FL190-OUT)") (class "Default")
      (node (ref "AT54") (pin "3") (pinfunction "IN/OUT_3") (pintype "passive"))
      (node (ref "FL190") (pin "2") (pinfunction "OUT_2") (pintype "passive"))
      (node (ref "L243") (pin "2") (pinfunction "2_2") (pintype "passive"))
    )
    (net (code "103") (name "Net-(FL500-IN)") (class "Default")
      (node (ref "C969") (pin "1") (pintype "passive"))
      (node (ref "FL500") (pin "1") (pinfunction "IN_1") (pintype "passive"))
      (node (ref "FL501") (pin "3") (pinfunction "OUT_3") (pintype "passive"))
    )
    (net (code "104") (name "Net-(FL500-OUT)") (class "Default")
      (node (ref "C1225") (pin "1") (pintype "passive"))
      (node (ref "FL500") (pin "3") (pinfunction "OUT_3") (pintype "passive"))
      (node (ref "FL506") (pin "1") (pinfunction "IN_1") (pintype "passive"))
    )
    (net (code "105") (name "Net-(FL501-IN)") (class "Default")
      (node (ref "C970") (pin "1") (pintype "passive"))
      (node (ref "FL501") (pin "1") (pinfunction "IN_1") (pintype "passive"))
      (node (ref "R782") (pin "2") (pintype "passive"))
    )
    (net (code "106") (name "Net-(FL506-OUT)") (class "Default")
      (node (ref "C1227") (pin "1") (pintype "passive"))
      (node (ref "FL506") (pin "3") (pinfunction "OUT_3") (pintype "passive"))
      (node (ref "L504") (pin "1") (pinfunction "1_1") (pintype "passive"))
    )
    (net (code "107") (name "Net-(J2-CNTR)") (class "Default")
      (node (ref "AT61") (pin "3") (pinfunction "IN/OUT_3") (pintype "passive"))
      (node (ref "J2") (pin "1") (pinfunction "CNTR_1") (pintype "passive"))
    )
    (net (code "108") (name "Net-(J25-CNTR)") (class "Default")
      (node (ref "C959") (pin "1") (pintype "passive"))
      (node (ref "J25") (pin "1") (pinfunction "CNTR_1") (pintype "passive"))
    )
    (net (code "109") (name "Net-(L5-Pad1)") (class "Default")
      (node (ref "L5") (pin "1") (pinfunction "1_1") (pintype "passive"))
      (node (ref "R316") (pin "1") (pintype "passive"))
    )
    (net (code "110") (name "Net-(L12-Pad1)") (class "Default")
      (node (ref "L12") (pin "1") (pinfunction "1_1") (pintype "passive"))
      (node (ref "R10") (pin "2") (pintype "passive"))
    )
    (net (code "111") (name "Net-(L13-Pad1)") (class "Default")
      (node (ref "L13") (pin "1") (pinfunction "1_1") (pintype "passive"))
      (node (ref "R64") (pin "2") (pintype "passive"))
    )
    (net (code "112") (name "Net-(L15-Pad1)") (class "Default")
      (node (ref "L15") (pin "1") (pinfunction "1_1") (pintype "passive"))
      (node (ref "R65") (pin "2") (pintype "passive"))
    )
    (net (code "113") (name "Net-(L16-Pad1)") (class "Default")
      (node (ref "L16") (pin "1") (pinfunction "1_1") (pintype "passive"))
      (node (ref "R66") (pin "2") (pintype "passive"))
    )
    (net (code "114") (name "Net-(L56-Pad1)") (class "Default")
      (node (ref "L56") (pin "1") (pinfunction "1_1") (pintype "passive"))
      (node (ref "R83") (pin "2") (pintype "passive"))
    )
    (net (code "115") (name "Net-(L57-Pad1)") (class "Default")
      (node (ref "L57") (pin "1") (pinfunction "1_1") (pintype "passive"))
      (node (ref "R87") (pin "2") (pintype "passive"))
    )
    (net (code "116") (name "Net-(L59-Pad1)") (class "Default")
      (node (ref "L59") (pin "1") (pinfunction "1_1") (pintype "passive"))
      (node (ref "R88") (pin "2") (pintype "passive"))
    )
    (net (code "117") (name "Net-(L65-Pad1)") (class "Default")
      (node (ref "L65") (pin "1") (pinfunction "1_1") (pintype "passive"))
      (node (ref "R91") (pin "2") (pintype "passive"))
    )
    (net (code "118") (name "Net-(L66-Pad2)") (class "Default")
      (node (ref "L66") (pin "2") (pinfunction "2_2") (pintype "passive"))
      (node (ref "R76") (pin "1") (pintype "passive"))
    )
    (net (code "119") (name "Net-(L67-Pad2)") (class "Default")
      (node (ref "L67") (pin "2") (pinfunction "2_2") (pintype "passive"))
      (node (ref "R77") (pin "1") (pintype "passive"))
    )
    (net (code "120") (name "Net-(L68-Pad2)") (class "Default")
      (node (ref "L68") (pin "2") (pinfunction "2_2") (pintype "passive"))
      (node (ref "R80") (pin "1") (pintype "passive"))
    )
    (net (code "121") (name "Net-(L69-Pad2)") (class "Default")
      (node (ref "L69") (pin "2") (pinfunction "2_2") (pintype "passive"))
      (node (ref "R95") (pin "1") (pintype "passive"))
    )
    (net (code "122") (name "Net-(L71-Pad2)") (class "Default")
      (node (ref "L71") (pin "2") (pinfunction "2_2") (pintype "passive"))
      (node (ref "R96") (pin "1") (pintype "passive"))
    )
    (net (code "123") (name "Net-(L73-Pad2)") (class "Default")
      (node (ref "L73") (pin "2") (pinfunction "2_2") (pintype "passive"))
      (node (ref "R97") (pin "1") (pintype "passive"))
    )
    (net (code "124") (name "Net-(L88-Pad1)") (class "Default")
      (node (ref "L88") (pin "1") (pinfunction "1_1") (pintype "passive"))
      (node (ref "R102") (pin "2") (pintype "passive"))
    )
    (net (code "125") (name "Net-(L89-Pad2)") (class "Default")
      (node (ref "L89") (pin "2") (pinfunction "2_2") (pintype "passive"))
      (node (ref "R2") (pin "2") (pintype "passive"))
    )
    (net (code "126") (name "Net-(L149-Pad1)") (class "Default")
      (node (ref "L149") (pin "1") (pinfunction "1_1") (pintype "passive"))
      (node (ref "R112") (pin "2") (pintype "passive"))
    )
    (net (code "127") (name "Net-(L150-Pad1)") (class "Default")
      (node (ref "L150") (pin "1") (pinfunction "1_1") (pintype "passive"))
      (node (ref "R113") (pin "2") (pintype "passive"))
    )
    (net (code "128") (name "Net-(L151-Pad1)") (class "Default")
      (node (ref "L151") (pin "1") (pinfunction "1_1") (pintype "passive"))
      (node (ref "R114") (pin "2") (pintype "passive"))
    )
    (net (code "129") (name "Net-(L152-Pad2)") (class "Default")
      (node (ref "L152") (pin "2") (pinfunction "2_2") (pintype "passive"))
      (node (ref "R115") (pin "1") (pintype "passive"))
    )
    (net (code "130") (name "Net-(L156-Pad2)") (class "Default")
      (node (ref "L156") (pin "2") (pinfunction "2_2") (pintype "passive"))
      (node (ref "R291") (pin "1") (pintype "passive"))
    )
    (net (code "131") (name "Net-(L158-Pad2)") (class "Default")
      (node (ref "L158") (pin "2") (pinfunction "2_2") (pintype "passive"))
      (node (ref "R292") (pin "1") (pintype "passive"))
    )
    (net (code "132") (name "Net-(L159-Pad1)") (class "Default")
      (node (ref "L159") (pin "1") (pinfunction "1_1") (pintype "passive"))
      (node (ref "R293") (pin "2") (pintype "passive"))
    )
    (net (code "133") (name "Net-(L160-Pad1)") (class "Default")
      (node (ref "L160") (pin "1") (pinfunction "1_1") (pintype "passive"))
      (node (ref "R294") (pin "2") (pintype "passive"))
    )
    (net (code "134") (name "Net-(L161-Pad1)") (class "Default")
      (node (ref "L161") (pin "1") (pinfunction "1_1") (pintype "passive"))
      (node (ref "R295") (pin "2") (pintype "passive"))
    )
    (net (code "135") (name "Net-(L162-Pad1)") (class "Default")
      (node (ref "L162") (pin "1") (pinfunction "1_1") (pintype "passive"))
      (node (ref "R296") (pin "2") (pintype "passive"))
    )
    (net (code "136") (name "Net-(L229-Pad2)") (class "Default")
      (node (ref "L229") (pin "2") (pinfunction "2_2") (pintype "passive"))
      (node (ref "R297") (pin "1") (pintype "passive"))
    )
    (net (code "137") (name "Net-(L230-Pad2)") (class "Default")
      (node (ref "L230") (pin "2") (pinfunction "2_2") (pintype "passive"))
      (node (ref "R300") (pin "1") (pintype "passive"))
    )
    (net (code "138") (name "Net-(L235-Pad2)") (class "Default")
      (node (ref "L235") (pin "2") (pinfunction "2_2") (pintype "passive"))
      (node (ref "R301") (pin "1") (pintype "passive"))
    )
    (net (code "139") (name "Net-(L236-Pad1)") (class "Default")
      (node (ref "L236") (pin "1") (pinfunction "1_1") (pintype "passive"))
      (node (ref "R302") (pin "2") (pintype "passive"))
    )
    (net (code "140") (name "Net-(L237-Pad1)") (class "Default")
      (node (ref "L237") (pin "1") (pinfunction "1_1") (pintype "passive"))
      (node (ref "R303") (pin "2") (pintype "passive"))
    )
    (net (code "141") (name "Net-(L238-Pad1)") (class "Default")
      (node (ref "L238") (pin "1") (pinfunction "1_1") (pintype "passive"))
      (node (ref "R304") (pin "2") (pintype "passive"))
    )
    (net (code "142") (name "Net-(L239-Pad1)") (class "Default")
      (node (ref "L239") (pin "1") (pinfunction "1_1") (pintype "passive"))
      (node (ref "R305") (pin "2") (pintype "passive"))
    )
    (net (code "143") (name "Net-(L244-Pad1)") (class "Default")
      (node (ref "L244") (pin "1") (pinfunction "1_1") (pintype "passive"))
      (node (ref "R308") (pin "2") (pintype "passive"))
    )
    (net (code "144") (name "Net-(L245-Pad1)") (class "Default")
      (node (ref "L245") (pin "1") (pinfunction "1_1") (pintype "passive"))
      (node (ref "R309") (pin "2") (pintype "passive"))
    )
    (net (code "145") (name "Net-(L246-Pad1)") (class "Default")
      (node (ref "L246") (pin "1") (pinfunction "1_1") (pintype "passive"))
      (node (ref "R310") (pin "2") (pintype "passive"))
    )
    (net (code "146") (name "Net-(L247-Pad1)") (class "Default")
      (node (ref "L247") (pin "1") (pinfunction "1_1") (pintype "passive"))
      (node (ref "R311") (pin "2") (pintype "passive"))
    )
    (net (code "147") (name "Net-(R6-Pad1)") (class "Default")
      (node (ref "R6") (pin "1") (pintype "passive"))
      (node (ref "U4") (pin "22") (pinfunction "RF2_22") (pintype "passive"))
    )
    (net (code "148") (name "Net-(R7-Pad1)") (class "Default")
      (node (ref "R7") (pin "1") (pintype "passive"))
      (node (ref "U7") (pin "22") (pinfunction "RF2_22") (pintype "passive"))
    )
    (net (code "149") (name "Net-(R11-Pad1)") (class "Default")
      (node (ref "R11") (pin "1") (pintype "passive"))
      (node (ref "R53") (pin "2") (pintype "passive"))
    )
    (net (code "150") (name "Net-(R14-Pad1)") (class "Default")
      (node (ref "R14") (pin "1") (pintype "passive"))
      (node (ref "R58") (pin "2") (pintype "passive"))
    )
    (net (code "151") (name "Net-(R69-Pad1)") (class "Default")
      (node (ref "R69") (pin "1") (pintype "passive"))
      (node (ref "U8") (pin "22") (pinfunction "RF2_22") (pintype "passive"))
    )
    (net (code "152") (name "Net-(R74-Pad1)") (class "Default")
      (node (ref "R74") (pin "1") (pintype "passive"))
      (node (ref "U9") (pin "22") (pinfunction "RF2_22") (pintype "passive"))
    )
    (net (code "153") (name "Net-(R99-Pad1)") (class "Default")
      (node (ref "R99") (pin "1") (pintype "passive"))
      (node (ref "U10") (pin "22") (pinfunction "RF2_22") (pintype "passive"))
    )
    (net (code "154") (name "Net-(R100-Pad1)") (class "Default")
      (node (ref "R100") (pin "1") (pintype "passive"))
      (node (ref "U13") (pin "22") (pinfunction "RF2_22") (pintype "passive"))
    )
    (net (code "155") (name "Net-(R118-Pad1)") (class "Default")
      (node (ref "R118") (pin "1") (pintype "passive"))
      (node (ref "U18") (pin "22") (pinfunction "RF2_22") (pintype "passive"))
    )
    (net (code "156") (name "Net-(R275-Pad1)") (class "Default")
      (node (ref "R275") (pin "1") (pintype "passive"))
      (node (ref "U20") (pin "22") (pinfunction "RF2_22") (pintype "passive"))
    )
    (net (code "157") (name "Net-(R298-Pad1)") (class "Default")
      (node (ref "R298") (pin "1") (pintype "passive"))
      (node (ref "U22") (pin "22") (pinfunction "RF2_22") (pintype "passive"))
    )
    (net (code "158") (name "Net-(R299-Pad1)") (class "Default")
      (node (ref "R299") (pin "1") (pintype "passive"))
      (node (ref "U23") (pin "22") (pinfunction "RF2_22") (pintype "passive"))
    )
    (net (code "159") (name "Net-(R306-Pad1)") (class "Default")
      (node (ref "R306") (pin "1") (pintype "passive"))
      (node (ref "U25") (pin "22") (pinfunction "RF2_22") (pintype "passive"))
    )
    (net (code "160") (name "Net-(R307-Pad1)") (class "Default")
      (node (ref "R307") (pin "1") (pintype "passive"))
      (node (ref "U35") (pin "22") (pinfunction "RF2_22") (pintype "passive"))
    )
    (net (code "161") (name "Net-(R781-Pad2)") (class "Default")
      (node (ref "R781") (pin "2") (pintype "passive"))
      (node (ref "R782") (pin "1") (pintype "passive"))
    )
    (net (code "162") (name "Net-(U4-A)") (class "Default")
      (node (ref "C103") (pin "1") (pintype "passive"))
      (node (ref "L13") (pin "2") (pinfunction "2_2") (pintype "passive"))
      (node (ref "U4") (pin "16") (pinfunction "A_16") (pintype "passive"))
    )
    (net (code "163") (name "Net-(U4-B)") (class "Default")
      (node (ref "C102") (pin "1") (pintype "passive"))
      (node (ref "L12") (pin "2") (pinfunction "2_2") (pintype "passive"))
      (node (ref "U4") (pin "15") (pinfunction "B_15") (pintype "passive"))
    )
    (net (code "164") (name "Net-(U4-RF1)") (class "Default")
      (node (ref "C20") (pin "2") (pintype "passive"))
      (node (ref "U4") (pin "9") (pinfunction "RF1_9") (pintype "passive"))
    )
    (net (code "165") (name "Net-(U7-A)") (class "Default")
      (node (ref "C105") (pin "1") (pintype "passive"))
      (node (ref "L16") (pin "2") (pinfunction "2_2") (pintype "passive"))
      (node (ref "U7") (pin "16") (pinfunction "A_16") (pintype "passive"))
    )
    (net (code "166") (name "Net-(U7-B)") (class "Default")
      (node (ref "C104") (pin "1") (pintype "passive"))
      (node (ref "L15") (pin "2") (pinfunction "2_2") (pintype "passive"))
      (node (ref "U7") (pin "15") (pinfunction "B_15") (pintype "passive"))
    )
    (net (code "167") (name "Net-(U7-RF1)") (class "Default")
      (node (ref "C29") (pin "2") (pintype "passive"))
      (node (ref "U7") (pin "9") (pinfunction "RF1_9") (pintype "passive"))
    )
    (net (code "168") (name "Net-(U8-A)") (class "Default")
      (node (ref "C177") (pin "1") (pintype "passive"))
      (node (ref "L57") (pin "2") (pinfunction "2_2") (pintype "passive"))
      (node (ref "U8") (pin "16") (pinfunction "A_16") (pintype "passive"))
    )
    (net (code "169") (name "Net-(U8-B)") (class "Default")
      (node (ref "C176") (pin "1") (pintype "passive"))
      (node (ref "L56") (pin "2") (pinfunction "2_2") (pintype "passive"))
      (node (ref "U8") (pin "15") (pinfunction "B_15") (pintype "passive"))
    )
    (net (code "170") (name "Net-(U8-RF1)") (class "Default")
      (node (ref "C113") (pin "2") (pintype "passive"))
      (node (ref "U8") (pin "9") (pinfunction "RF1_9") (pintype "passive"))
    )
    (net (code "171") (name "Net-(U9-A)") (class "Default")
      (node (ref "C179") (pin "1") (pintype "passive"))
      (node (ref "L65") (pin "2") (pinfunction "2_2") (pintype "passive"))
      (node (ref "U9") (pin "16") (pinfunction "A_16") (pintype "passive"))
    )
    (net (code "172") (name "Net-(U9-B)") (class "Default")
      (node (ref "C178") (pin "1") (pintype "passive"))
      (node (ref "L59") (pin "2") (pinfunction "2_2") (pintype "passive"))
      (node (ref "U9") (pin "15") (pinfunction "B_15") (pintype "passive"))
    )
    (net (code "173") (name "Net-(U9-RF1)") (class "Default")
      (node (ref "C116") (pin "2") (pintype "passive"))
      (node (ref "U9") (pin "9") (pinfunction "RF1_9") (pintype "passive"))
    )
    (net (code "174") (name "Net-(U10-A)") (class "Default")
      (node (ref "C353") (pin "1") (pintype "passive"))
      (node (ref "L149") (pin "2") (pinfunction "2_2") (pintype "passive"))
      (node (ref "U10") (pin "16") (pinfunction "A_16") (pintype "passive"))
    )
    (net (code "175") (name "Net-(U10-B)") (class "Default")
      (node (ref "C234") (pin "1") (pintype "passive"))
      (node (ref "L88") (pin "2") (pinfunction "2_2") (pintype "passive"))
      (node (ref "U10") (pin "15") (pinfunction "B_15") (pintype "passive"))
    )
    (net (code "176") (name "Net-(U10-RF1)") (class "Default")
      (node (ref "C200") (pin "2") (pintype "passive"))
      (node (ref "U10") (pin "9") (pinfunction "RF1_9") (pintype "passive"))
    )
    (net (code "177") (name "Net-(U13-A)") (class "Default")
      (node (ref "C355") (pin "1") (pintype "passive"))
      (node (ref "L151") (pin "2") (pinfunction "2_2") (pintype "passive"))
      (node (ref "U13") (pin "16") (pinfunction "A_16") (pintype "passive"))
    )
    (net (code "178") (name "Net-(U13-B)") (class "Default")
      (node (ref "C354") (pin "1") (pintype "passive"))
      (node (ref "L150") (pin "2") (pinfunction "2_2") (pintype "passive"))
      (node (ref "U13") (pin "15") (pinfunction "B_15") (pintype "passive"))
    )
    (net (code "179") (name "Net-(U13-RF1)") (class "Default")
      (node (ref "C203") (pin "2") (pintype "passive"))
      (node (ref "U13") (pin "9") (pinfunction "RF1_9") (pintype "passive"))
    )
    (net (code "180") (name "Net-(U15-C1)") (class "Default")
      (node (ref "C253") (pin "1") (pintype "passive"))
      (node (ref "C827") (pin "2") (pintype "passive"))
      (node (ref "R115") (pin "2") (pintype "passive"))
      (node (ref "U15") (pin "9") (pinfunction "C1_9") (pintype "passive"))
    )
    (net (code "181") (name "Net-(U15-C2)") (class "Default")
      (node (ref "C254") (pin "1") (pintype "passive"))
      (node (ref "C833") (pin "2") (pintype "passive"))
      (node (ref "R291") (pin "2") (pintype "passive"))
      (node (ref "U15") (pin "8") (pinfunction "C2_8") (pintype "passive"))
    )
    (net (code "182") (name "Net-(U15-C3)") (class "Default")
      (node (ref "C255") (pin "1") (pintype "passive"))
      (node (ref "C839") (pin "2") (pintype "passive"))
      (node (ref "R292") (pin "2") (pintype "passive"))
      (node (ref "U15") (pin "7") (pinfunction "C3_7") (pintype "passive"))
    )
    (net (code "183") (name "Net-(U15-C4)") (class "Default")
      (node (ref "C256") (pin "1") (pintype "passive"))
      (node (ref "C847") (pin "2") (pintype "passive"))
      (node (ref "R297") (pin "2") (pintype "passive"))
      (node (ref "U15") (pin "6") (pinfunction "C4_6") (pintype "passive"))
    )
    (net (code "184") (name "Net-(U15-C5)") (class "Default")
      (node (ref "C259") (pin "1") (pintype "passive"))
      (node (ref "C854") (pin "2") (pintype "passive"))
      (node (ref "R300") (pin "2") (pintype "passive"))
      (node (ref "U15") (pin "5") (pinfunction "C5_5") (pintype "passive"))
    )
    (net (code "185") (name "Net-(U15-C6)") (class "Default")
      (node (ref "C351") (pin "1") (pintype "passive"))
      (node (ref "C856") (pin "2") (pintype "passive"))
      (node (ref "R301") (pin "2") (pintype "passive"))
      (node (ref "U15") (pin "4") (pinfunction "C6_4") (pintype "passive"))
    )
    (net (code "186") (name "Net-(U15-RF1)") (class "Default")
      (node (ref "C822") (pin "2") (pintype "passive"))
      (node (ref "U15") (pin "14") (pinfunction "RF1_14") (pintype "passive"))
    )
    (net (code "187") (name "Net-(U15-RF2)") (class "Default")
      (node (ref "C845") (pin "2") (pintype "passive"))
      (node (ref "U15") (pin "16") (pinfunction "RF2_16") (pintype "passive"))
    )
    (net (code "188") (name "Net-(U15-RF3)") (class "Default")
      (node (ref "C866") (pin "2") (pintype "passive"))
      (node (ref "U15") (pin "18") (pinfunction "RF3_18") (pintype "passive"))
    )
    (net (code "189") (name "Net-(U15-RF4)") (class "Default")
      (node (ref "C18") (pin "2") (pintype "passive"))
      (node (ref "U15") (pin "25") (pinfunction "RF4_25") (pintype "passive"))
    )
    (net (code "190") (name "Net-(U15-RF5)") (class "Default")
      (node (ref "C111") (pin "2") (pintype "passive"))
      (node (ref "U15") (pin "27") (pinfunction "RF5_27") (pintype "passive"))
    )
    (net (code "191") (name "Net-(U15-RF6)") (class "Default")
      (node (ref "C188") (pin "2") (pintype "passive"))
      (node (ref "U15") (pin "29") (pinfunction "RF6_29") (pintype "passive"))
    )
    (net (code "192") (name "Net-(U15-RFC)") (class "Default")
      (node (ref "C401") (pin "1") (pintype "passive"))
      (node (ref "U15") (pin "22") (pinfunction "RFC_22") (pintype "passive"))
    )
    (net (code "193") (name "Net-(U17-C1)") (class "Default")
      (node (ref "C151") (pin "1") (pintype "passive"))
      (node (ref "C197") (pin "2") (pintype "passive"))
      (node (ref "R95") (pin "2") (pintype "passive"))
      (node (ref "U17") (pin "9") (pinfunction "C1_9") (pintype "passive"))
    )
    (net (code "194") (name "Net-(U17-C2)") (class "Default")
      (node (ref "C152") (pin "1") (pintype "passive"))
      (node (ref "C198") (pin "2") (pintype "passive"))
      (node (ref "R96") (pin "2") (pintype "passive"))
      (node (ref "U17") (pin "8") (pinfunction "C2_8") (pintype "passive"))
    )
    (net (code "195") (name "Net-(U17-C3)") (class "Default")
      (node (ref "C199") (pin "2") (pintype "passive"))
      (node (ref "C241") (pin "1") (pintype "passive"))
      (node (ref "R97") (pin "2") (pintype "passive"))
      (node (ref "U17") (pin "7") (pinfunction "C3_7") (pintype "passive"))
    )
    (net (code "196") (name "Net-(U17-C4)") (class "Default")
      (node (ref "C148") (pin "1") (pintype "passive"))
      (node (ref "C191") (pin "2") (pintype "passive"))
      (node (ref "R76") (pin "2") (pintype "passive"))
      (node (ref "U17") (pin "6") (pinfunction "C4_6") (pintype "passive"))
    )
    (net (code "197") (name "Net-(U17-C5)") (class "Default")
      (node (ref "C149") (pin "1") (pintype "passive"))
      (node (ref "C192") (pin "2") (pintype "passive"))
      (node (ref "R77") (pin "2") (pintype "passive"))
      (node (ref "U17") (pin "5") (pinfunction "C5_5") (pintype "passive"))
    )
    (net (code "198") (name "Net-(U17-C6)") (class "Default")
      (node (ref "C150") (pin "1") (pintype "passive"))
      (node (ref "C193") (pin "2") (pintype "passive"))
      (node (ref "R80") (pin "2") (pintype "passive"))
      (node (ref "U17") (pin "4") (pinfunction "C6_4") (pintype "passive"))
    )
    (net (code "199") (name "Net-(U17-RF1)") (class "Default")
      (node (ref "C200") (pin "1") (pintype "passive"))
      (node (ref "U17") (pin "14") (pinfunction "RF1_14") (pintype "passive"))
    )
    (net (code "200") (name "Net-(U17-RF2)") (class "Default")
      (node (ref "C113") (pin "1") (pintype "passive"))
      (node (ref "U17") (pin "16") (pinfunction "RF2_16") (pintype "passive"))
    )
    (net (code "201") (name "Net-(U17-RF3)") (class "Default")
      (node (ref "C20") (pin "1") (pintype "passive"))
      (node (ref "U17") (pin "18") (pinfunction "RF3_18") (pintype "passive"))
    )
    (net (code "202") (name "Net-(U17-RF4)") (class "Default")
      (node (ref "C868") (pin "1") (pintype "passive"))
      (node (ref "U17") (pin "25") (pinfunction "RF4_25") (pintype "passive"))
    )
    (net (code "203") (name "Net-(U17-RF5)") (class "Default")
      (node (ref "C850") (pin "1") (pintype "passive"))
      (node (ref "U17") (pin "27") (pinfunction "RF5_27") (pintype "passive"))
    )
    (net (code "204") (name "Net-(U17-RF6)") (class "Default")
      (node (ref "C828") (pin "1") (pintype "passive"))
      (node (ref "U17") (pin "29") (pinfunction "RF6_29") (pintype "passive"))
    )
    (net (code "205") (name "Net-(U17-RFC)") (class "Default")
      (node (ref "C881") (pin "1") (pintype "passive"))
      (node (ref "U17") (pin "22") (pinfunction "RFC_22") (pintype "passive"))
    )
    (net (code "206") (name "Net-(U18-A)") (class "Default")
      (node (ref "C836") (pin "1") (pintype "passive"))
      (node (ref "L160") (pin "2") (pinfunction "2_2") (pintype "passive"))
      (node (ref "U18") (pin "16") (pinfunction "A_16") (pintype "passive"))
    )
    (net (code "207") (name "Net-(U18-B)") (class "Default")
      (node (ref "C835") (pin "1") (pintype "passive"))
      (node (ref "L159") (pin "2") (pinfunction "2_2") (pintype "passive"))
      (node (ref "U18") (pin "15") (pinfunction "B_15") (pintype "passive"))
    )
    (net (code "208") (name "Net-(U18-RF1)") (class "Default")
      (node (ref "C828") (pin "2") (pintype "passive"))
      (node (ref "U18") (pin "9") (pinfunction "RF1_9") (pintype "passive"))
    )
    (net (code "209") (name "Net-(U20-A)") (class "Default")
      (node (ref "C838") (pin "1") (pintype "passive"))
      (node (ref "L162") (pin "2") (pinfunction "2_2") (pintype "passive"))
      (node (ref "U20") (pin "16") (pinfunction "A_16") (pintype "passive"))
    )
    (net (code "210") (name "Net-(U20-B)") (class "Default")
      (node (ref "C837") (pin "1") (pintype "passive"))
      (node (ref "L161") (pin "2") (pinfunction "2_2") (pintype "passive"))
      (node (ref "U20") (pin "15") (pinfunction "B_15") (pintype "passive"))
    )
    (net (code "211") (name "Net-(U20-RF1)") (class "Default")
      (node (ref "C831") (pin "2") (pintype "passive"))
      (node (ref "U20") (pin "9") (pinfunction "RF1_9") (pintype "passive"))
    )
    (net (code "212") (name "Net-(U22-A)") (class "Default")
      (node (ref "C858") (pin "1") (pintype "passive"))
      (node (ref "L237") (pin "2") (pinfunction "2_2") (pintype "passive"))
      (node (ref "U22") (pin "16") (pinfunction "A_16") (pintype "passive"))
    )
    (net (code "213") (name "Net-(U22-B)") (class "Default")
      (node (ref "C857") (pin "1") (pintype "passive"))
      (node (ref "L236") (pin "2") (pinfunction "2_2") (pintype "passive"))
      (node (ref "U22") (pin "15") (pinfunction "B_15") (pintype "passive"))
    )
    (net (code "214") (name "Net-(U22-RF1)") (class "Default")
      (node (ref "C850") (pin "2") (pintype "passive"))
      (node (ref "U22") (pin "9") (pinfunction "RF1_9") (pintype "passive"))
    )
    (net (code "215") (name "Net-(U23-A)") (class "Default")
      (node (ref "C860") (pin "1") (pintype "passive"))
      (node (ref "L239") (pin "2") (pinfunction "2_2") (pintype "passive"))
      (node (ref "U23") (pin "16") (pinfunction "A_16") (pintype "passive"))
    )
    (net (code "216") (name "Net-(U23-B)") (class "Default")
      (node (ref "C859") (pin "1") (pintype "passive"))
      (node (ref "L238") (pin "2") (pinfunction "2_2") (pintype "passive"))
      (node (ref "U23") (pin "15") (pinfunction "B_15") (pintype "passive"))
    )
    (net (code "217") (name "Net-(U23-RF1)") (class "Default")
      (node (ref "C853") (pin "2") (pintype "passive"))
      (node (ref "U23") (pin "9") (pinfunction "RF1_9") (pintype "passive"))
    )
    (net (code "218") (name "Net-(U25-A)") (class "Default")
      (node (ref "C873") (pin "1") (pintype "passive"))
      (node (ref "L245") (pin "2") (pinfunction "2_2") (pintype "passive"))
      (node (ref "U25") (pin "16") (pinfunction "A_16") (pintype "passive"))
    )
    (net (code "219") (name "Net-(U25-B)") (class "Default")
      (node (ref "C872") (pin "1") (pintype "passive"))
      (node (ref "L244") (pin "2") (pinfunction "2_2") (pintype "passive"))
      (node (ref "U25") (pin "15") (pinfunction "B_15") (pintype "passive"))
    )
    (net (code "220") (name "Net-(U25-RF1)") (class "Default")
      (node (ref "C868") (pin "2") (pintype "passive"))
      (node (ref "U25") (pin "9") (pinfunction "RF1_9") (pintype "passive"))
    )
    (net (code "221") (name "Net-(U35-A)") (class "Default")
      (node (ref "C875") (pin "1") (pintype "passive"))
      (node (ref "L247") (pin "2") (pinfunction "2_2") (pintype "passive"))
      (node (ref "U35") (pin "16") (pinfunction "A_16") (pintype "passive"))
    )
    (net (code "222") (name "Net-(U35-B)") (class "Default")
      (node (ref "C874") (pin "1") (pintype "passive"))
      (node (ref "L246") (pin "2") (pinfunction "2_2") (pintype "passive"))
      (node (ref "U35") (pin "15") (pinfunction "B_15") (pintype "passive"))
    )
    (net (code "223") (name "Net-(U35-RF1)") (class "Default")
      (node (ref "C871") (pin "2") (pintype "passive"))
      (node (ref "U35") (pin "9") (pinfunction "RF1_9") (pintype "passive"))
    )
    (net (code "224") (name "Net-(U82-IF+)") (class "Default")
      (node (ref "C880") (pin "2") (pintype "passive"))
      (node (ref "C882") (pin "2") (pintype "passive"))
      (node (ref "C883") (pin "2") (pintype "passive"))
      (node (ref "L5") (pin "2") (pinfunction "2_2") (pintype "passive"))
      (node (ref "U82") (pin "3") (pinfunction "IF+_3") (pintype "passive"))
    )
    (net (code "225") (name "Net-(U82-IF-)") (class "Default")
      (node (ref "C882") (pin "1") (pintype "passive"))
      (node (ref "C883") (pin "1") (pintype "passive"))
      (node (ref "C885") (pin "2") (pintype "passive"))
      (node (ref "L89") (pin "1") (pinfunction "1_1") (pintype "passive"))
      (node (ref "U82") (pin "4") (pinfunction "IF-_4") (pintype "passive"))
    )
    (net (code "226") (name "Net-(U82-LO)") (class "Default")
      (node (ref "C722") (pin "1") (pintype "passive"))
      (node (ref "U82") (pin "22") (pinfunction "LO_22") (pintype "passive"))
    )
    (net (code "227") (name "Net-(U82-RF)") (class "Default")
      (node (ref "C881") (pin "2") (pintype "passive"))
      (node (ref "C884") (pin "2") (pintype "passive"))
      (node (ref "U82") (pin "15") (pinfunction "RF_15") (pintype "passive"))
    )
    (net (code "228") (name "Net-(U169-IN)") (class "Default")
      (node (ref "C1229") (pin "2") (pintype "passive"))
      (node (ref "U169") (pin "1") (pinfunction "IN_1") (pintype "passive"))
    )
    (net (code "229") (name "Net-(U169-OUT)") (class "Default")
      (node (ref "C1228") (pin "1") (pintype "passive"))
      (node (ref "L504") (pin "2") (pinfunction "2_2") (pintype "passive"))
      (node (ref "U169") (pin "3") (pinfunction "OUT_3") (pintype "passive"))
    )
    (net (code "230") (name "Net-(X5-Pri-)") (class "Default")
      (node (ref "AT57") (pin "3") (pinfunction "IN/OUT_3") (pintype "passive"))
      (node (ref "X5") (pin "3") (pinfunction "Pri-_3") (pintype "passive"))
    )
    (net (code "231") (name "Net-(X5-Sec+)") (class "Default")
      (node (ref "C885") (pin "1") (pintype "passive"))
      (node (ref "X5") (pin "5") (pinfunction "Sec+_5") (pintype "passive"))
    )
    (net (code "232") (name "Net-(X5-Sec-)") (class "Default")
      (node (ref "C880") (pin "1") (pintype "passive"))
      (node (ref "X5") (pin "4") (pinfunction "Sec-_4") (pintype "passive"))
    )
    (net (code "233") (name "unconnected-(U15-CP1-Pad36)") (class "Default")
      (node (ref "U15") (pin "36") (pinfunction "CP1_36") (pintype "passive"))
    )
    (net (code "234") (name "unconnected-(U15-CP2-Pad1)") (class "Default")
      (node (ref "U15") (pin "1") (pinfunction "CP2_1") (pintype "passive"))
    )
    (net (code "235") (name "unconnected-(U15-NC-Pad3)") (class "Default")
      (node (ref "U15") (pin "3") (pinfunction "NC_3") (pintype "passive"))
    )
    (net (code "236") (name "unconnected-(U15-NC-Pad10)") (class "Default")
      (node (ref "U15") (pin "10") (pinfunction "NC_10") (pintype "passive"))
    )
    (net (code "237") (name "unconnected-(U15-NC-Pad12)") (class "Default")
      (node (ref "U15") (pin "12") (pinfunction "NC_12") (pintype "passive"))
    )
    (net (code "238") (name "unconnected-(U15-NC-Pad20)") (class "Default")
      (node (ref "U15") (pin "20") (pinfunction "NC_20") (pintype "passive"))
    )
    (net (code "239") (name "unconnected-(U15-NC-Pad31)") (class "Default")
      (node (ref "U15") (pin "31") (pinfunction "NC_31") (pintype "passive"))
    )
    (net (code "240") (name "unconnected-(U15-NC-Pad34)") (class "Default")
      (node (ref "U15") (pin "34") (pinfunction "NC_34") (pintype "passive"))
    )
    (net (code "241") (name "unconnected-(U15-VCC-Pad35)") (class "Default")
      (node (ref "U15") (pin "35") (pinfunction "VCC_35") (pintype "passive"))
    )
    (net (code "242") (name "unconnected-(U15-VEE-Pad2)") (class "Default")
      (node (ref "U15") (pin "2") (pinfunction "VEE_2") (pintype "passive"))
    )
    (net (code "243") (name "unconnected-(U17-CP1-Pad36)") (class "Default")
      (node (ref "U17") (pin "36") (pinfunction "CP1_36") (pintype "passive"))
    )
    (net (code "244") (name "unconnected-(U17-CP2-Pad1)") (class "Default")
      (node (ref "U17") (pin "1") (pinfunction "CP2_1") (pintype "passive"))
    )
    (net (code "245") (name "unconnected-(U17-NC-Pad3)") (class "Default")
      (node (ref "U17") (pin "3") (pinfunction "NC_3") (pintype "passive"))
    )
    (net (code "246") (name "unconnected-(U17-NC-Pad10)") (class "Default")
      (node (ref "U17") (pin "10") (pinfunction "NC_10") (pintype "passive"))
    )
    (net (code "247") (name "unconnected-(U17-NC-Pad12)") (class "Default")
      (node (ref "U17") (pin "12") (pinfunction "NC_12") (pintype "passive"))
    )
    (net (code "248") (name "unconnected-(U17-NC-Pad20)") (class "Default")
      (node (ref "U17") (pin "20") (pinfunction "NC_20") (pintype "passive"))
    )
    (net (code "249") (name "unconnected-(U17-NC-Pad31)") (class "Default")
      (node (ref "U17") (pin "31") (pinfunction "NC_31") (pintype "passive"))
    )
    (net (code "250") (name "unconnected-(U17-NC-Pad34)") (class "Default")
      (node (ref "U17") (pin "34") (pinfunction "NC_34") (pintype "passive"))
    )
    (net (code "251") (name "unconnected-(U17-VCC-Pad35)") (class "Default")
      (node (ref "U17") (pin "35") (pinfunction "VCC_35") (pintype "passive"))
    )
    (net (code "252") (name "unconnected-(U17-VEE-Pad2)") (class "Default")
      (node (ref "U17") (pin "2") (pinfunction "VEE_2") (pintype "passive"))
    )
    (net (code "253") (name "unconnected-(X5-SecCT-Pad2)") (class "Default")
      (node (ref "X5") (pin "2") (pinfunction "SecCT_2") (pintype "passive"))
    )
  )
)
